# BlockBox_v2.net
KiCad netlist of a schematic drawn in EAGLE
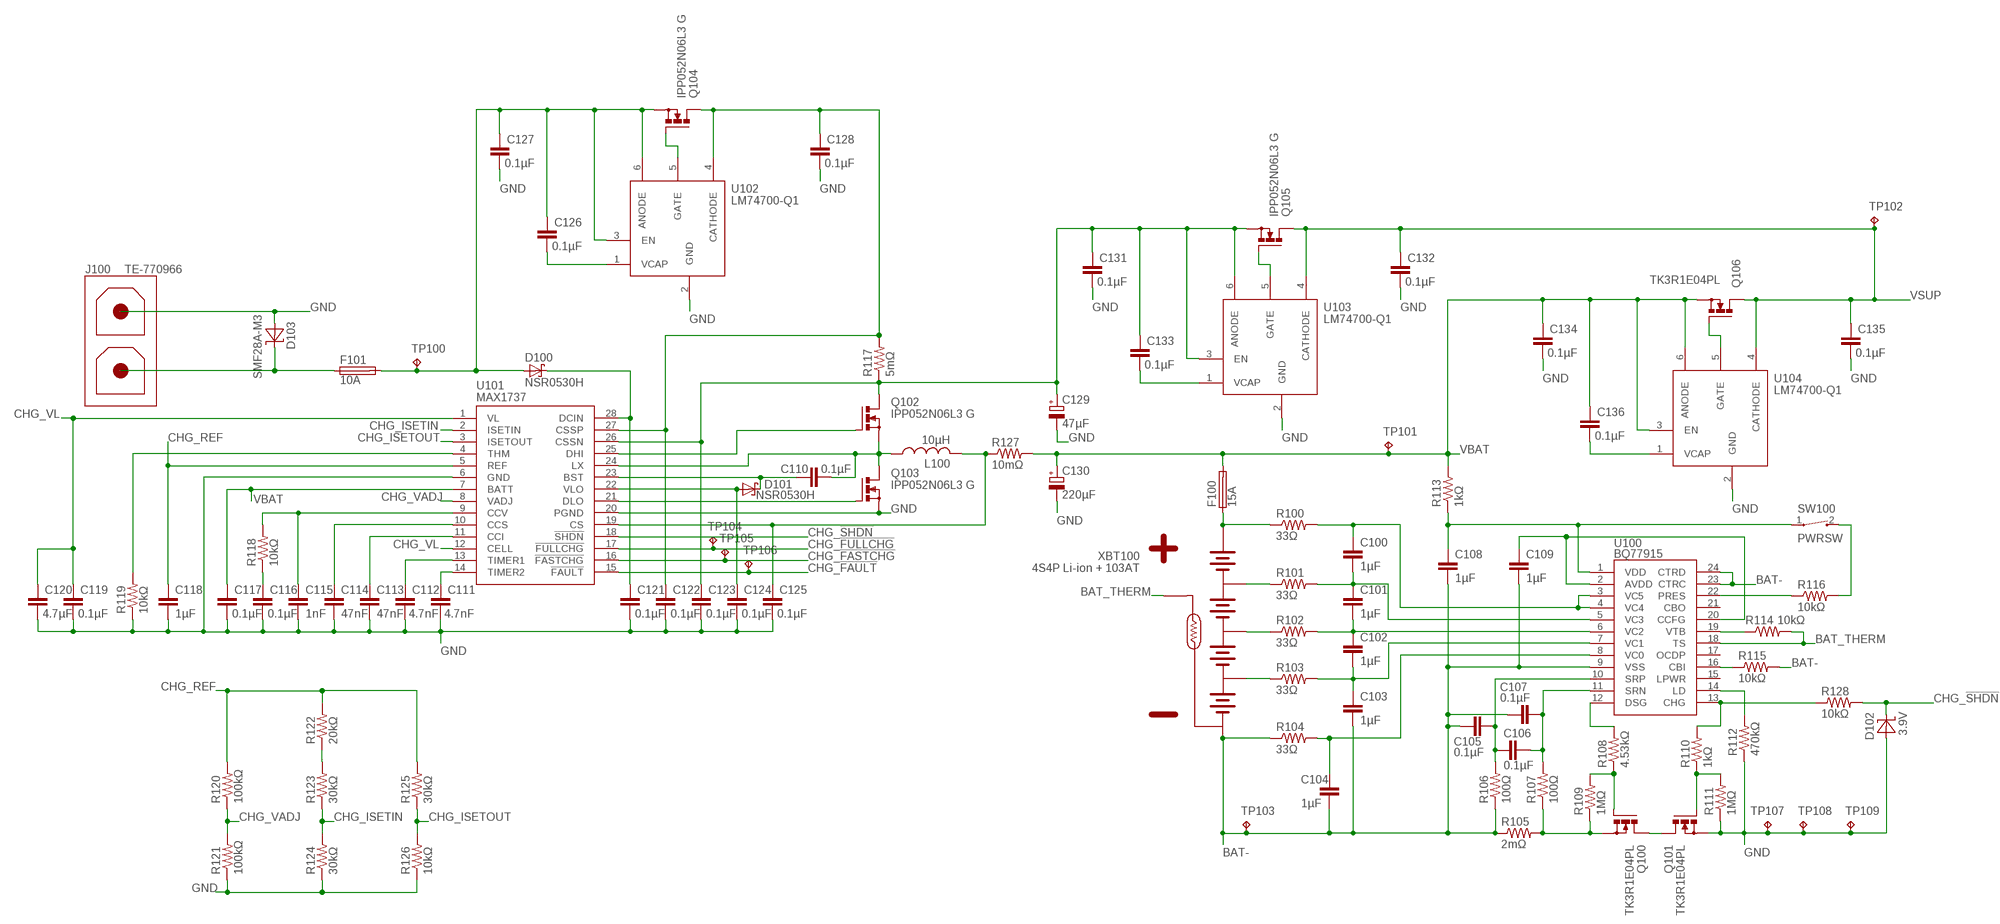
[diagram p0: schematic, sheet 1]
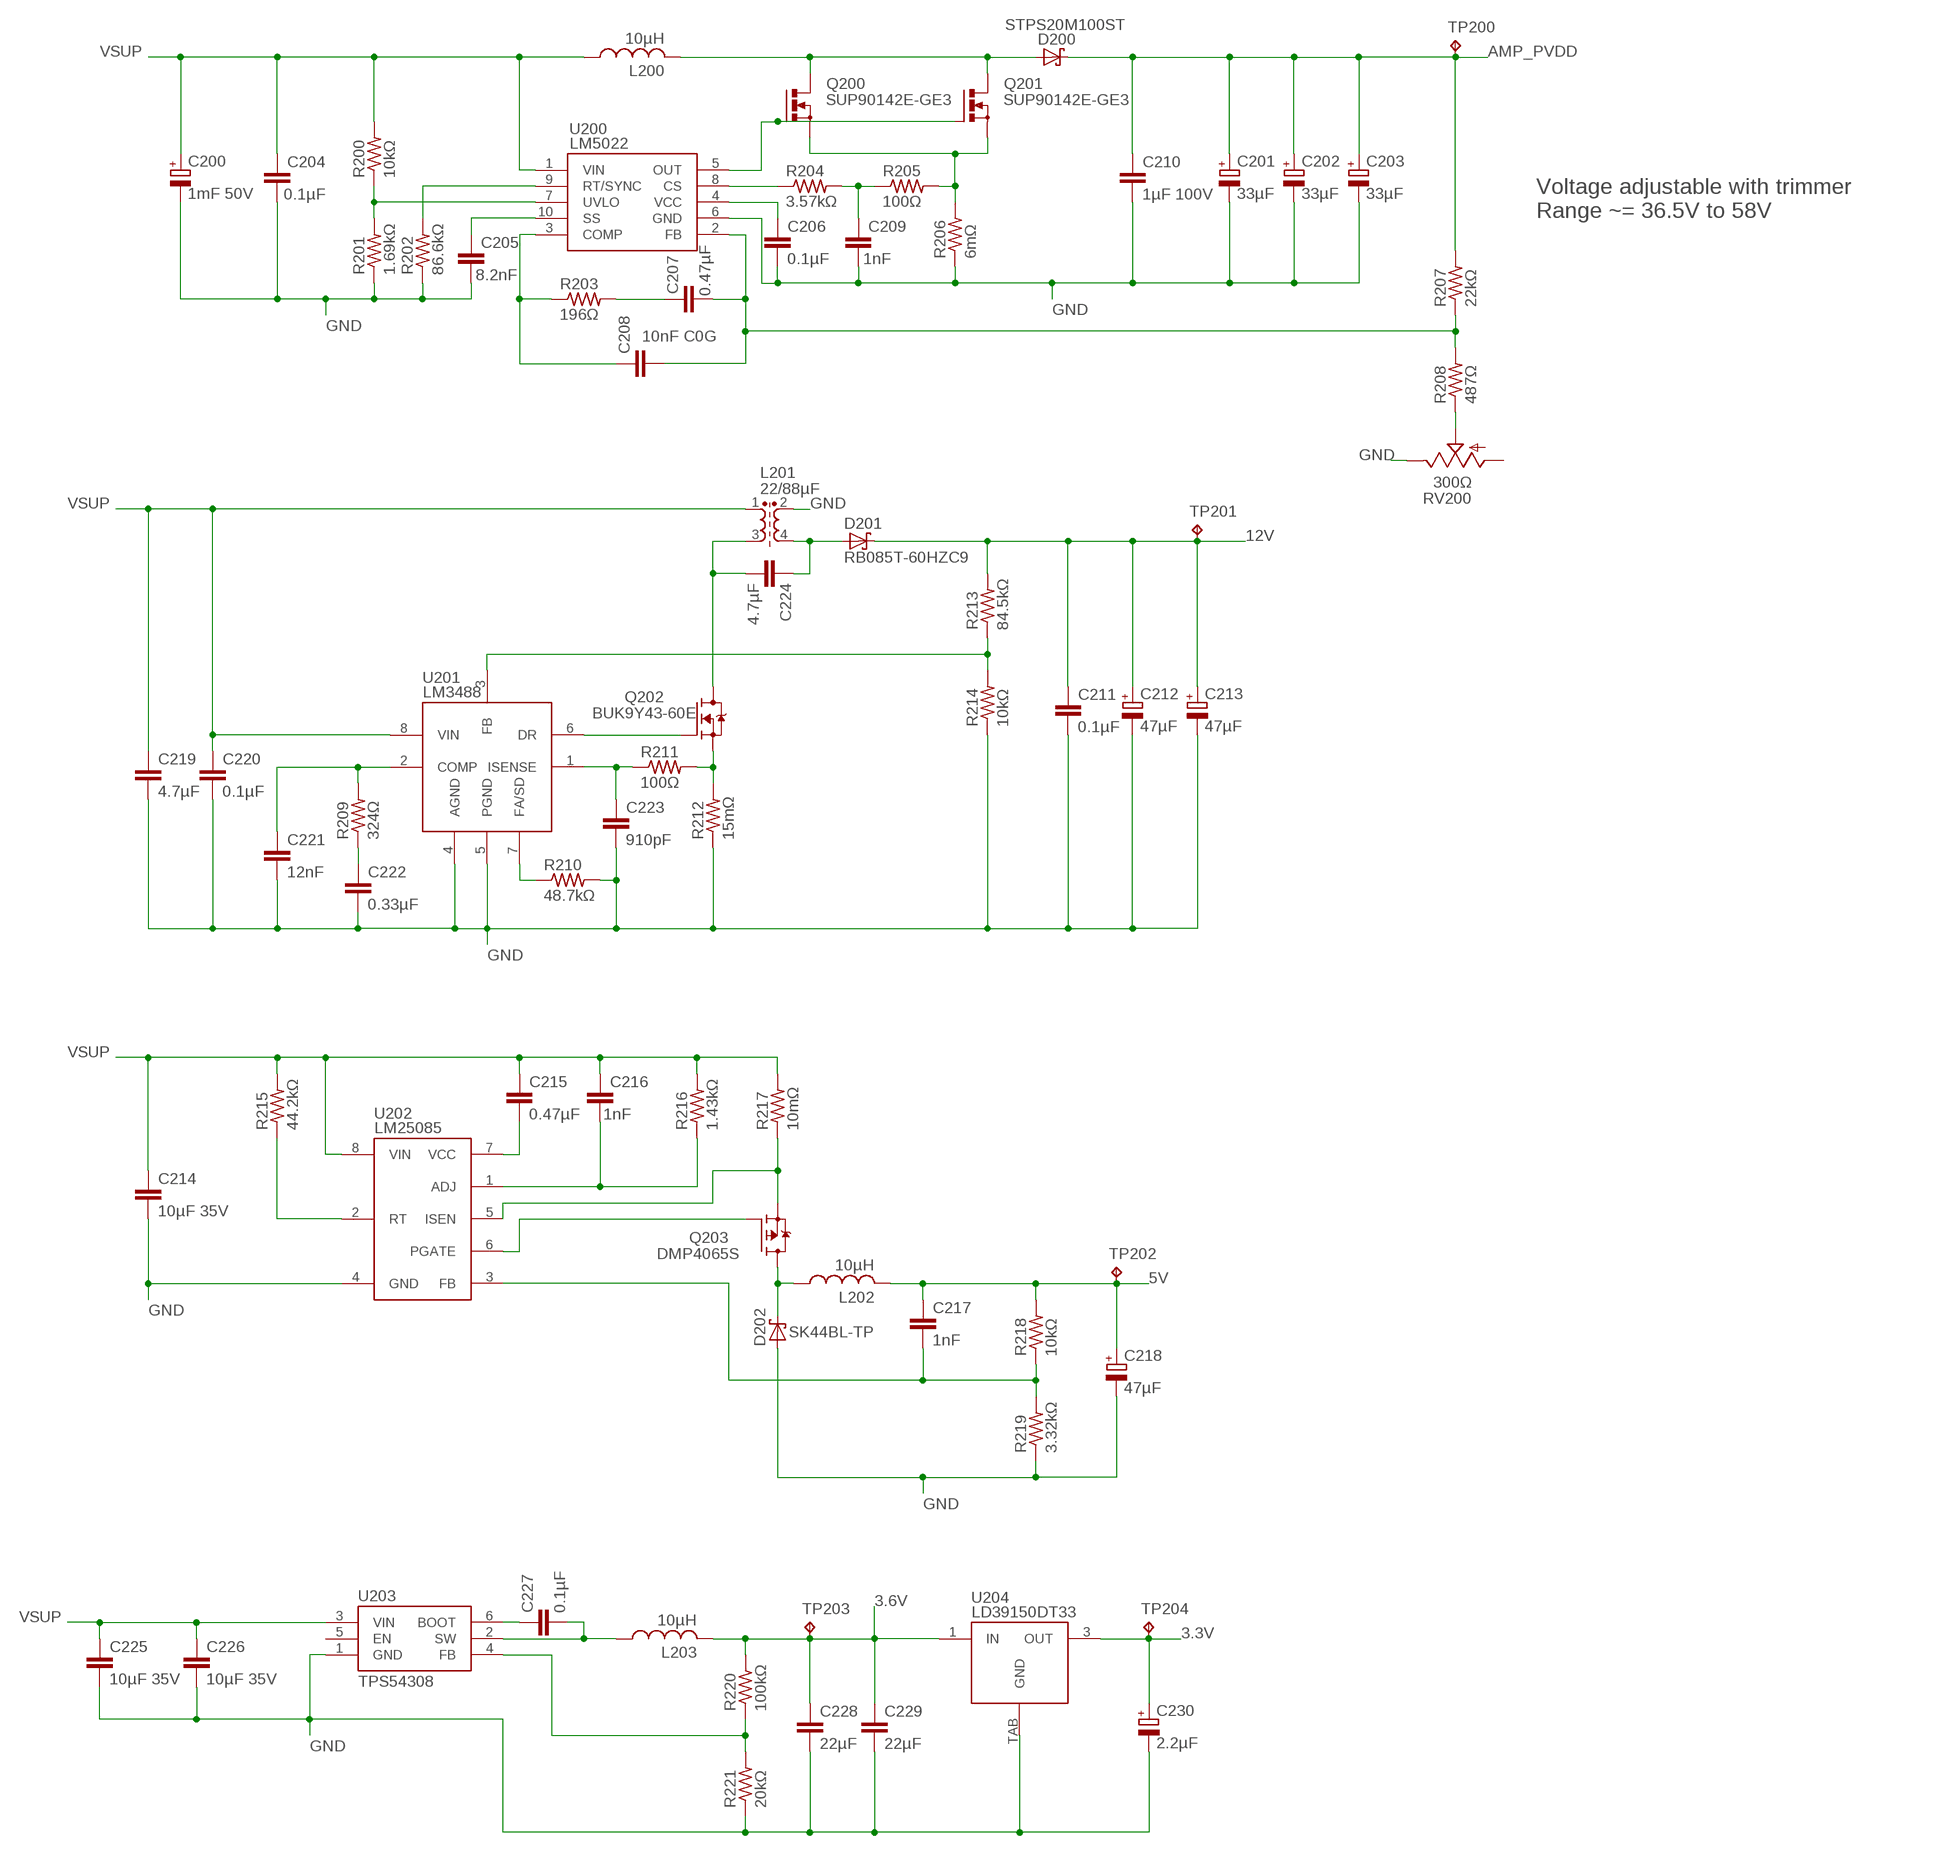
[diagram p1: schematic, sheet 2]
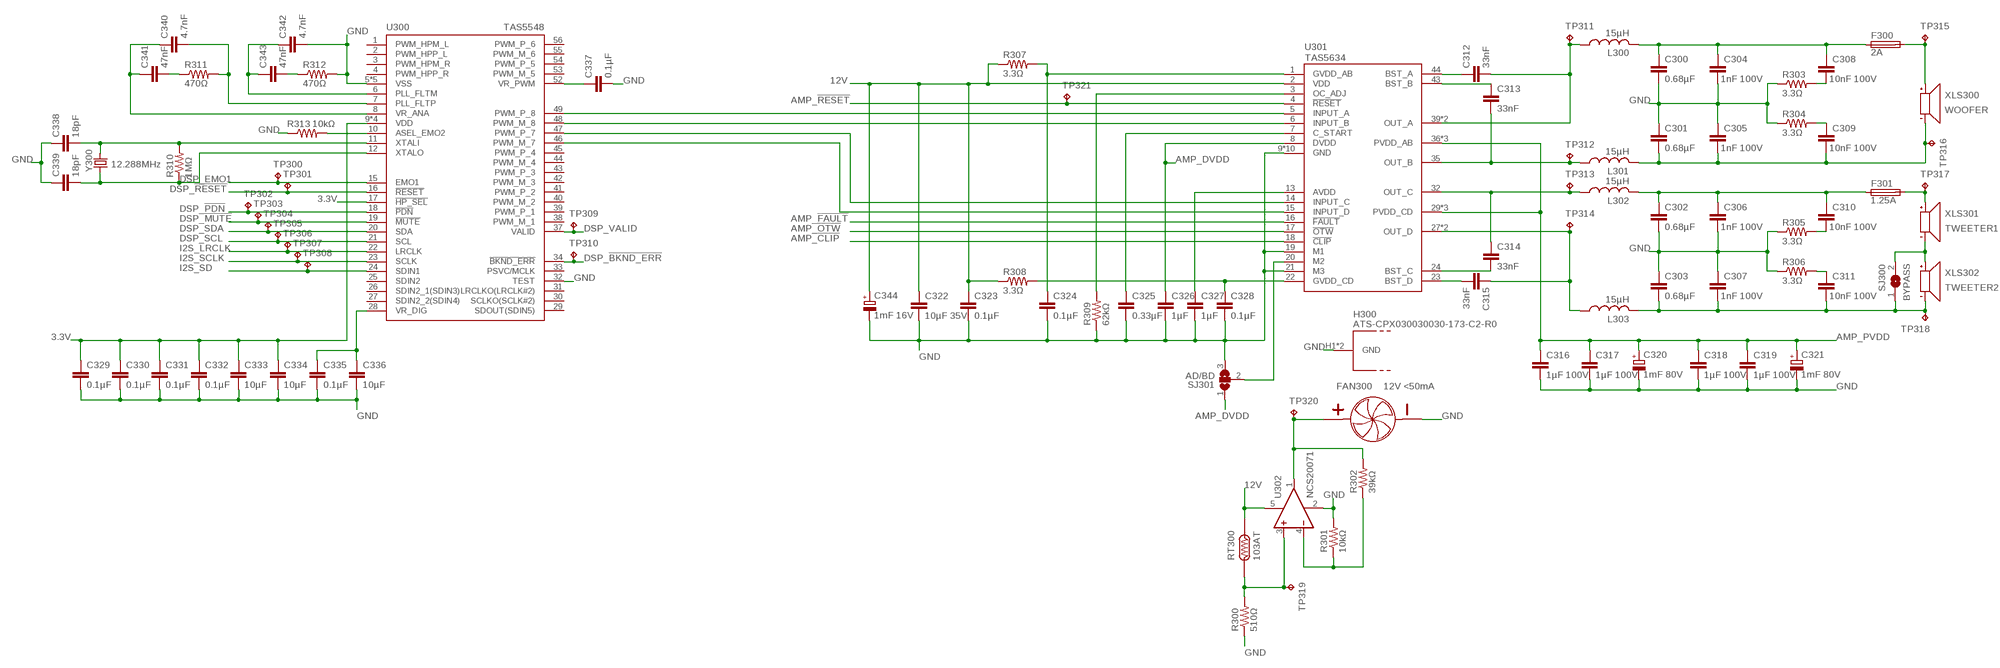
[diagram p2: schematic, sheet 3]
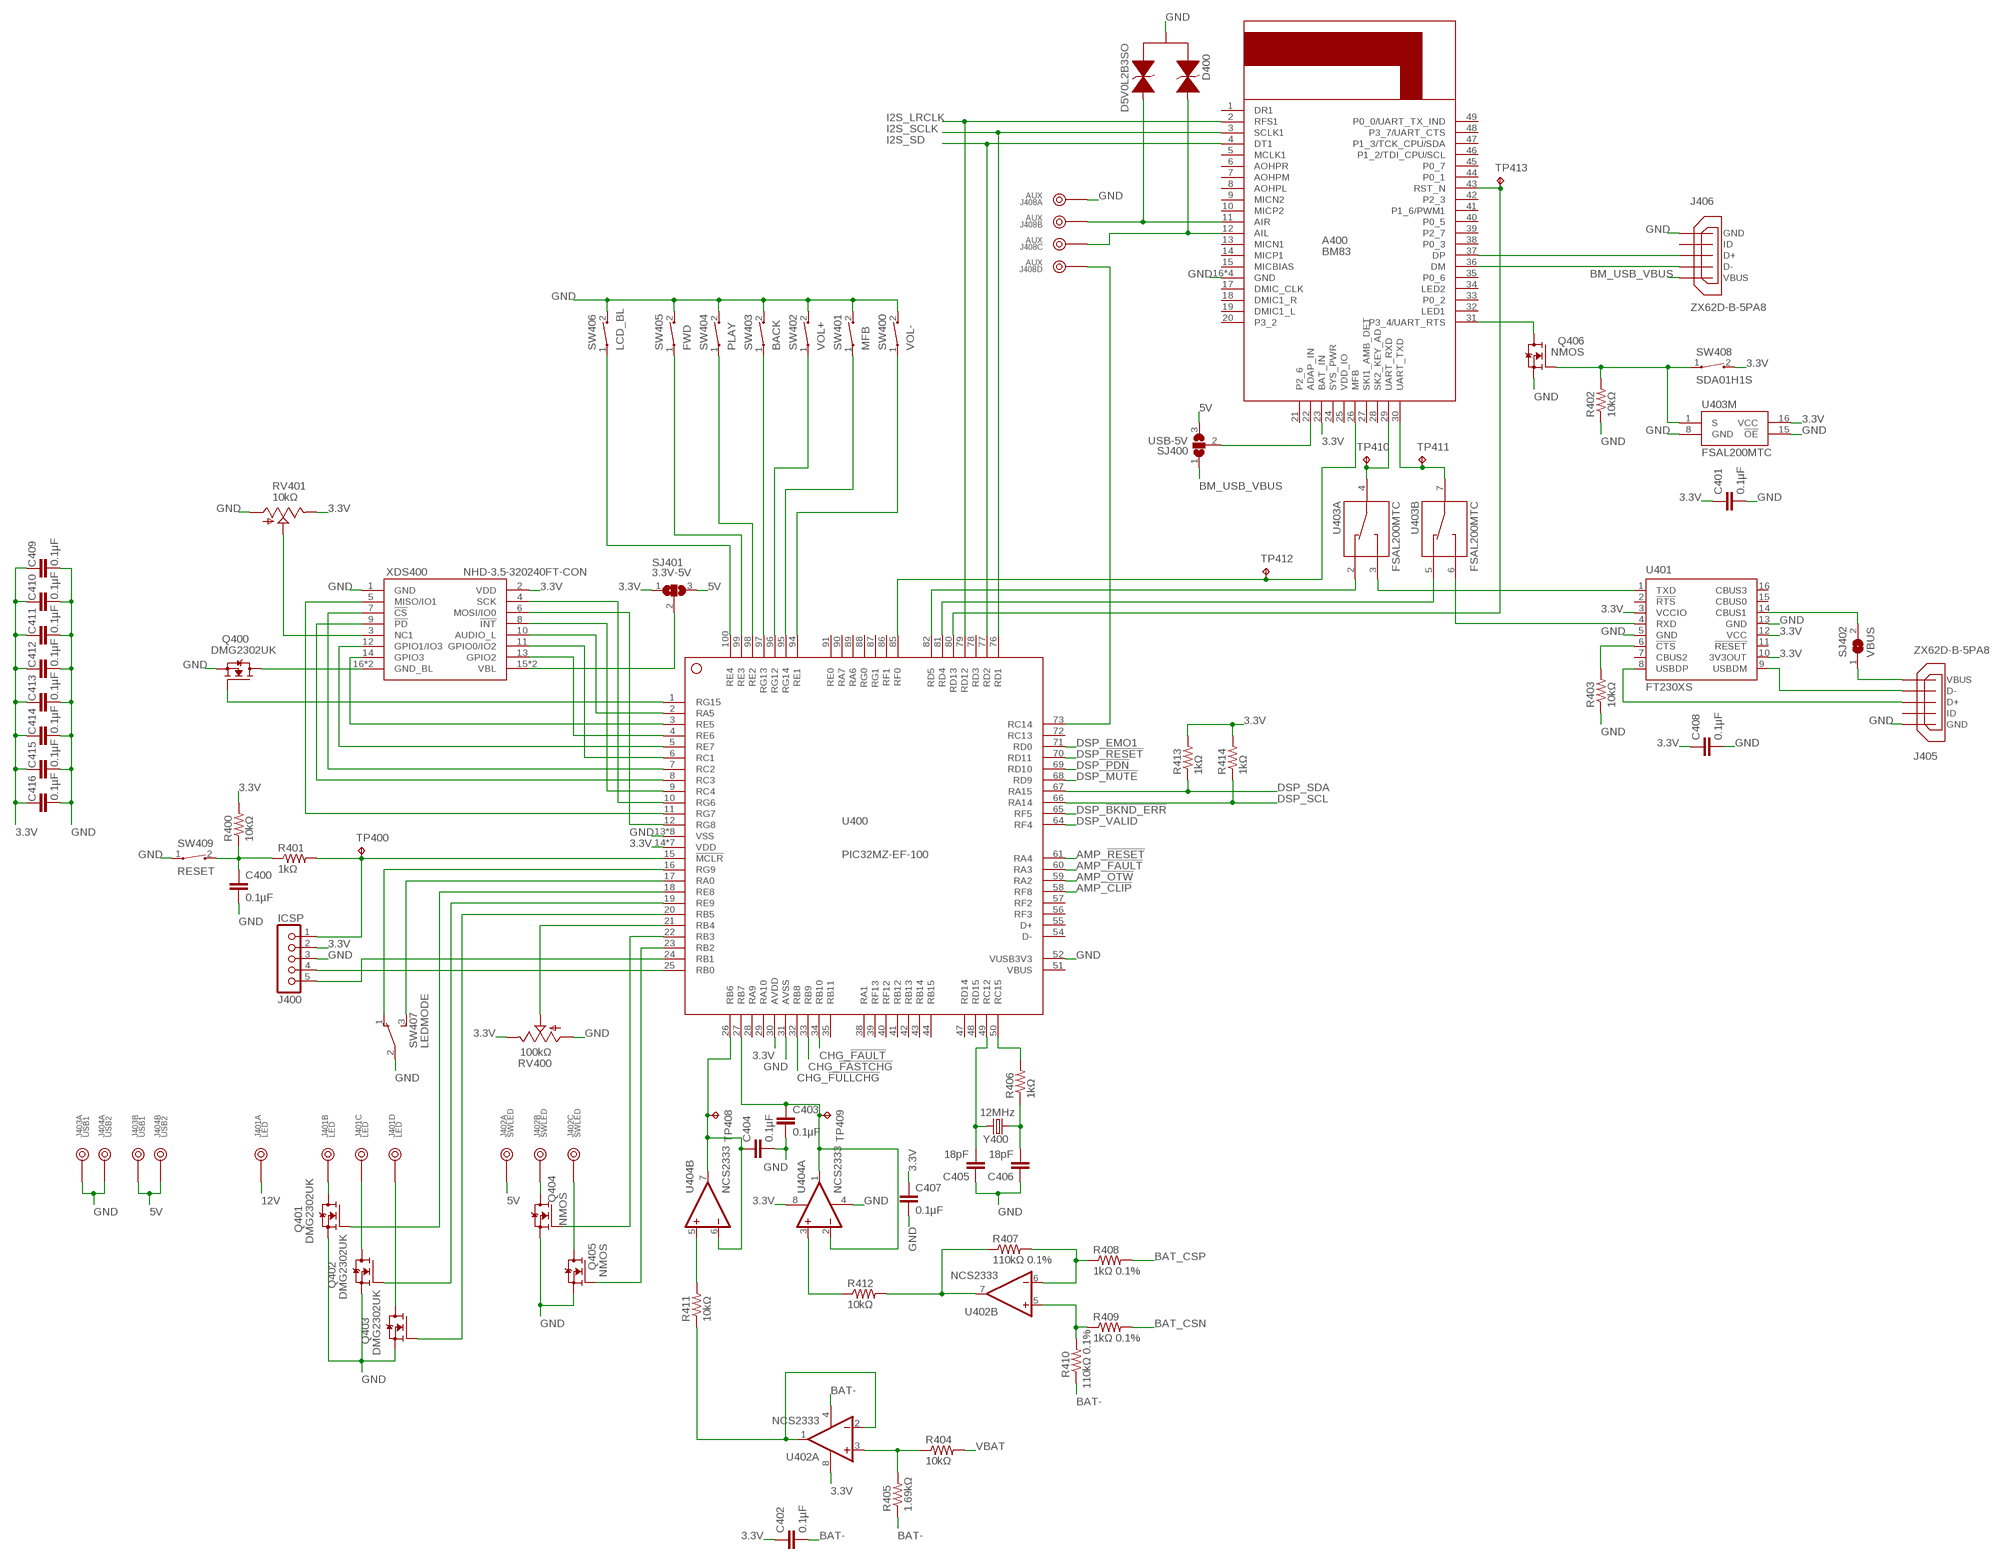
[diagram p3: schematic, sheet 4]

(export (version "E")
  (design (tool "Eeschema 10.0.6"))
  (components
    (comp (ref "C200")
      (value "1mF 50V")
      (footprint "eagle-import:E7,5-16")
      (libsource (lib "eagle-import") (part "CPOL-EUE7.5-16"))
    )
    (comp (ref "C201")
      (value "33µF")
      (footprint "eagle-import:E3,5-8")
      (libsource (lib "eagle-import") (part "CPOL-EUE3.5-8"))
    )
    (comp (ref "C202")
      (value "33µF")
      (footprint "eagle-import:E3,5-8")
      (libsource (lib "eagle-import") (part "CPOL-EUE3.5-8"))
    )
    (comp (ref "C203")
      (value "33µF")
      (footprint "eagle-import:E3,5-8")
      (libsource (lib "eagle-import") (part "CPOL-EUE3.5-8"))
    )
    (comp (ref "C204")
      (value "0.1µF")
      (footprint "eagle-import:C0603")
      (libsource (lib "eagle-import") (part "C-EUC0603"))
    )
    (comp (ref "C205")
      (value "8.2nF")
      (footprint "eagle-import:C0603")
      (libsource (lib "eagle-import") (part "C-EUC0603"))
    )
    (comp (ref "C206")
      (value "0.1µF")
      (footprint "eagle-import:C0603")
      (libsource (lib "eagle-import") (part "C-EUC0603"))
    )
    (comp (ref "C207")
      (value "0.47µF")
      (footprint "eagle-import:C050-035X075")
      (libsource (lib "eagle-import") (part "C-EU050-035X075"))
    )
    (comp (ref "C208")
      (value "10nF C0G")
      (footprint "eagle-import:C0603")
      (libsource (lib "eagle-import") (part "C-EUC0603"))
    )
    (comp (ref "C209")
      (value "1nF")
      (footprint "eagle-import:C0603")
      (libsource (lib "eagle-import") (part "C-EUC0603"))
    )
    (comp (ref "C210")
      (value "1µF 100V")
      (footprint "eagle-import:C1206")
      (libsource (lib "eagle-import") (part "C-EUC1206"))
    )
    (comp (ref "C211")
      (value "0.1µF")
      (footprint "eagle-import:C0603")
      (libsource (lib "eagle-import") (part "C-EUC0603"))
    )
    (comp (ref "C212")
      (value "47µF")
      (footprint "eagle-import:E2,5-6")
      (libsource (lib "eagle-import") (part "CPOL-EUE2.5-6"))
    )
    (comp (ref "C213")
      (value "47µF")
      (footprint "eagle-import:E2,5-6")
      (libsource (lib "eagle-import") (part "CPOL-EUE2.5-6"))
    )
    (comp (ref "C214")
      (value "10µF 35V")
      (footprint "eagle-import:C1206")
      (libsource (lib "eagle-import") (part "C-EUC1206"))
    )
    (comp (ref "C215")
      (value "0.47µF")
      (footprint "eagle-import:C0603")
      (libsource (lib "eagle-import") (part "C-EUC0603"))
    )
    (comp (ref "C216")
      (value "1nF")
      (footprint "eagle-import:C0603")
      (libsource (lib "eagle-import") (part "C-EUC0603"))
    )
    (comp (ref "C217")
      (value "1nF")
      (footprint "eagle-import:C0603")
      (libsource (lib "eagle-import") (part "C-EUC0603"))
    )
    (comp (ref "C218")
      (value "47µF")
      (footprint "eagle-import:E2,5-6")
      (libsource (lib "eagle-import") (part "CPOL-EUE2.5-6"))
    )
    (comp (ref "C219")
      (value "4.7µF")
      (footprint "eagle-import:C0805")
      (libsource (lib "eagle-import") (part "C-EUC0805"))
    )
    (comp (ref "C220")
      (value "0.1µF")
      (footprint "eagle-import:C0603")
      (libsource (lib "eagle-import") (part "C-EUC0603"))
    )
    (comp (ref "C221")
      (value "12nF")
      (footprint "eagle-import:C0603")
      (libsource (lib "eagle-import") (part "C-EUC0603"))
    )
    (comp (ref "C222")
      (value "0.33µF")
      (footprint "eagle-import:C050-035X075")
      (libsource (lib "eagle-import") (part "C-EU050-035X075"))
    )
    (comp (ref "C223")
      (value "910pF")
      (footprint "eagle-import:C0603")
      (libsource (lib "eagle-import") (part "C-EUC0603"))
    )
    (comp (ref "C224")
      (value "4.7µF")
      (footprint "eagle-import:C0805")
      (libsource (lib "eagle-import") (part "C-EUC0805"))
    )
    (comp (ref "C225")
      (value "10µF 35V")
      (footprint "eagle-import:C1206")
      (libsource (lib "eagle-import") (part "C-EUC1206"))
    )
    (comp (ref "C226")
      (value "10µF 35V")
      (footprint "eagle-import:C1206")
      (libsource (lib "eagle-import") (part "C-EUC1206"))
    )
    (comp (ref "C227")
      (value "0.1µF")
      (footprint "eagle-import:C0603")
      (libsource (lib "eagle-import") (part "C-EUC0603"))
    )
    (comp (ref "C228")
      (value "22µF")
      (footprint "eagle-import:C0805")
      (libsource (lib "eagle-import") (part "C-EUC0805"))
    )
    (comp (ref "C229")
      (value "22µF")
      (footprint "eagle-import:C0805")
      (libsource (lib "eagle-import") (part "C-EUC0805"))
    )
    (comp (ref "C230")
      (value "2.2µF")
      (footprint "eagle-import:PANASONIC_B")
      (libsource (lib "eagle-import") (part "CPOL-EUB"))
    )
    (comp (ref "D200")
      (value "STPS20M100ST")
      (footprint "eagle-import:TO220ABS-HS1")
      (libsource (lib "eagle-import") (part "TO220AB-HS1-SCHOTTKY"))
    )
    (comp (ref "D201")
      (value "RB085T-60HZC9")
      (footprint "eagle-import:TO220ABS-HS1")
      (libsource (lib "eagle-import") (part "TO220AB-HS1-SCHOTTKY"))
    )
    (comp (ref "D202")
      (value "SK44BL-TP")
      (footprint "eagle-import:DO-214AA")
      (libsource (lib "eagle-import") (part "DO-214AA-SCHOTTKY"))
    )
    (comp (ref "L200")
      (value "10µH")
      (footprint "eagle-import:PQ2614B")
      (libsource (lib "eagle-import") (part "PQ2614B"))
    )
    (comp (ref "L201")
      (value "22/88µF")
      (footprint "eagle-import:SRF1280A")
      (libsource (lib "eagle-import") (part "SRF1280A"))
    )
    (comp (ref "L202")
      (value "10µH")
      (footprint "eagle-import:SRN1060")
      (libsource (lib "eagle-import") (part "SRN1060"))
    )
    (comp (ref "L203")
      (value "10µH")
      (footprint "eagle-import:RLB0912")
      (libsource (lib "eagle-import") (part "RLB0912"))
    )
    (comp (ref "Q200")
      (value "SUP90142E-GE3")
      (footprint "eagle-import:TO220BV-HS1")
      (libsource (lib "eagle-import") (part "TO220BV-HS1-N-MOSFET"))
    )
    (comp (ref "Q201")
      (value "SUP90142E-GE3")
      (footprint "eagle-import:TO220BV-HS1")
      (libsource (lib "eagle-import") (part "TO220BV-HS1-N-MOSFET"))
    )
    (comp (ref "Q202")
      (value "BUK9Y43-60E")
      (footprint "eagle-import:SOT669")
      (libsource (lib "eagle-import") (part "SOT669-N-MOSFET"))
    )
    (comp (ref "Q203")
      (value "DMP4065S")
      (footprint "eagle-import:SOT23")
      (libsource (lib "eagle-import") (part "SOT23-P-MOSFET"))
    )
    (comp (ref "R200")
      (value "10kΩ")
      (footprint "eagle-import:R0603")
      (libsource (lib "eagle-import") (part "R-US_R0603"))
    )
    (comp (ref "R201")
      (value "1.69kΩ")
      (footprint "eagle-import:R0603")
      (libsource (lib "eagle-import") (part "R-US_R0603"))
    )
    (comp (ref "R202")
      (value "86.6kΩ")
      (footprint "eagle-import:R0603")
      (libsource (lib "eagle-import") (part "R-US_R0603"))
    )
    (comp (ref "R203")
      (value "196Ω")
      (footprint "eagle-import:R0603")
      (libsource (lib "eagle-import") (part "R-US_R0603"))
    )
    (comp (ref "R204")
      (value "3.57kΩ")
      (footprint "eagle-import:R0603")
      (libsource (lib "eagle-import") (part "R-US_R0603"))
    )
    (comp (ref "R205")
      (value "100Ω")
      (footprint "eagle-import:R0603")
      (libsource (lib "eagle-import") (part "R-US_R0603"))
    )
    (comp (ref "R206")
      (value "6mΩ")
      (footprint "eagle-import:R2512")
      (libsource (lib "eagle-import") (part "R-US_R2512"))
    )
    (comp (ref "R207")
      (value "22kΩ")
      (footprint "eagle-import:R0603")
      (libsource (lib "eagle-import") (part "R-US_R0603"))
    )
    (comp (ref "R208")
      (value "487Ω")
      (footprint "eagle-import:R0603")
      (libsource (lib "eagle-import") (part "R-US_R0603"))
    )
    (comp (ref "R209")
      (value "324Ω")
      (footprint "eagle-import:R0603")
      (libsource (lib "eagle-import") (part "R-US_R0603"))
    )
    (comp (ref "R210")
      (value "48.7kΩ")
      (footprint "eagle-import:R0603")
      (libsource (lib "eagle-import") (part "R-US_R0603"))
    )
    (comp (ref "R211")
      (value "100Ω")
      (footprint "eagle-import:R0603")
      (libsource (lib "eagle-import") (part "R-US_R0603"))
    )
    (comp (ref "R212")
      (value "15mΩ")
      (footprint "eagle-import:R0612")
      (libsource (lib "eagle-import") (part "R-US_R0612"))
    )
    (comp (ref "R213")
      (value "84.5kΩ")
      (footprint "eagle-import:R0603")
      (libsource (lib "eagle-import") (part "R-US_R0603"))
    )
    (comp (ref "R214")
      (value "10kΩ")
      (footprint "eagle-import:R0603")
      (libsource (lib "eagle-import") (part "R-US_R0603"))
    )
    (comp (ref "R215")
      (value "44.2kΩ")
      (footprint "eagle-import:R0603")
      (libsource (lib "eagle-import") (part "R-US_R0603"))
    )
    (comp (ref "R216")
      (value "1.43kΩ")
      (footprint "eagle-import:R0603")
      (libsource (lib "eagle-import") (part "R-US_R0603"))
    )
    (comp (ref "R217")
      (value "10mΩ")
      (footprint "eagle-import:R1206")
      (libsource (lib "eagle-import") (part "R-US_R1206"))
    )
    (comp (ref "R218")
      (value "10kΩ")
      (footprint "eagle-import:R0603")
      (libsource (lib "eagle-import") (part "R-US_R0603"))
    )
    (comp (ref "R219")
      (value "3.32kΩ")
      (footprint "eagle-import:R0603")
      (libsource (lib "eagle-import") (part "R-US_R0603"))
    )
    (comp (ref "R220")
      (value "100kΩ")
      (footprint "eagle-import:R0603")
      (libsource (lib "eagle-import") (part "R-US_R0603"))
    )
    (comp (ref "R221")
      (value "20kΩ")
      (footprint "eagle-import:R0603")
      (libsource (lib "eagle-import") (part "R-US_R0603"))
    )
    (comp (ref "RV200")
      (value "300Ω")
      (footprint "eagle-import:TC33X-2")
      (libsource (lib "eagle-import") (part "TC33X-2"))
    )
    (comp (ref "TP200")
      (value "TPTP15R")
      (footprint "eagle-import:TP15R")
      (fields (field (name "TP_SIGNAL_NAME") "PVDD"))
      (libsource (lib "eagle-import") (part "TPTP15R"))
    )
    (comp (ref "TP201")
      (value "TPTP15R")
      (footprint "eagle-import:TP15R")
      (fields (field (name "TP_SIGNAL_NAME") "12V"))
      (libsource (lib "eagle-import") (part "TPTP15R"))
    )
    (comp (ref "TP202")
      (value "TPTP15R")
      (footprint "eagle-import:TP15R")
      (fields (field (name "TP_SIGNAL_NAME") "5V"))
      (libsource (lib "eagle-import") (part "TPTP15R"))
    )
    (comp (ref "TP203")
      (value "TPTP15R")
      (footprint "eagle-import:TP15R")
      (fields (field (name "TP_SIGNAL_NAME") "3.6V"))
      (libsource (lib "eagle-import") (part "TPTP15R"))
    )
    (comp (ref "TP204")
      (value "TPTP15R")
      (footprint "eagle-import:TP15R")
      (fields (field (name "TP_SIGNAL_NAME") "3.3V"))
      (libsource (lib "eagle-import") (part "TPTP15R"))
    )
    (comp (ref "U200")
      (value "LM5022")
      (footprint "eagle-import:VSSOP10")
      (libsource (lib "eagle-import") (part "LM5022"))
    )
    (comp (ref "U201")
      (value "LM3488")
      (footprint "eagle-import:VSSOP8")
      (libsource (lib "eagle-import") (part "LM3488"))
    )
    (comp (ref "U202")
      (value "LM25085")
      (footprint "eagle-import:VSSOP8")
      (libsource (lib "eagle-import") (part "LM25085"))
    )
    (comp (ref "U203")
      (value "TPS54308")
      (footprint "eagle-import:SOT23-6L")
      (libsource (lib "eagle-import") (part "TPS54308"))
    )
    (comp (ref "U204")
      (value "LD39150DT33")
      (footprint "eagle-import:DPAK")
      (libsource (lib "eagle-import") (part "DPAK-LDO"))
    )
    (comp (ref "C300")
      (value "0.68µF")
      (footprint "eagle-import:C150-064X183")
      (libsource (lib "eagle-import") (part "C-EU150-064X183"))
    )
    (comp (ref "C301")
      (value "0.68µF")
      (footprint "eagle-import:C150-064X183")
      (libsource (lib "eagle-import") (part "C-EU150-064X183"))
    )
    (comp (ref "C302")
      (value "0.68µF")
      (footprint "eagle-import:C150-064X183")
      (libsource (lib "eagle-import") (part "C-EU150-064X183"))
    )
    (comp (ref "C303")
      (value "0.68µF")
      (footprint "eagle-import:C150-064X183")
      (libsource (lib "eagle-import") (part "C-EU150-064X183"))
    )
    (comp (ref "C304")
      (value "1nF 100V")
      (footprint "eagle-import:C0603")
      (libsource (lib "eagle-import") (part "C-EUC0603"))
    )
    (comp (ref "C305")
      (value "1nF 100V")
      (footprint "eagle-import:C0603")
      (libsource (lib "eagle-import") (part "C-EUC0603"))
    )
    (comp (ref "C306")
      (value "1nF 100V")
      (footprint "eagle-import:C0603")
      (libsource (lib "eagle-import") (part "C-EUC0603"))
    )
    (comp (ref "C307")
      (value "1nF 100V")
      (footprint "eagle-import:C0603")
      (libsource (lib "eagle-import") (part "C-EUC0603"))
    )
    (comp (ref "C308")
      (value "10nF 100V")
      (footprint "eagle-import:C0603")
      (libsource (lib "eagle-import") (part "C-EUC0603"))
    )
    (comp (ref "C309")
      (value "10nF 100V")
      (footprint "eagle-import:C0603")
      (libsource (lib "eagle-import") (part "C-EUC0603"))
    )
    (comp (ref "C310")
      (value "10nF 100V")
      (footprint "eagle-import:C0603")
      (libsource (lib "eagle-import") (part "C-EUC0603"))
    )
    (comp (ref "C311")
      (value "10nF 100V")
      (footprint "eagle-import:C0603")
      (libsource (lib "eagle-import") (part "C-EUC0603"))
    )
    (comp (ref "C312")
      (value "33nF")
      (footprint "eagle-import:C0805")
      (libsource (lib "eagle-import") (part "C-EUC0805"))
    )
    (comp (ref "C313")
      (value "33nF")
      (footprint "eagle-import:C0805")
      (libsource (lib "eagle-import") (part "C-EUC0805"))
    )
    (comp (ref "C314")
      (value "33nF")
      (footprint "eagle-import:C0805")
      (libsource (lib "eagle-import") (part "C-EUC0805"))
    )
    (comp (ref "C315")
      (value "33nF")
      (footprint "eagle-import:C0805")
      (libsource (lib "eagle-import") (part "C-EUC0805"))
    )
    (comp (ref "C316")
      (value "1µF 100V")
      (footprint "eagle-import:C1206")
      (libsource (lib "eagle-import") (part "C-EUC1206"))
    )
    (comp (ref "C317")
      (value "1µF 100V")
      (footprint "eagle-import:C1206")
      (libsource (lib "eagle-import") (part "C-EUC1206"))
    )
    (comp (ref "C318")
      (value "1µF 100V")
      (footprint "eagle-import:C1206")
      (libsource (lib "eagle-import") (part "C-EUC1206"))
    )
    (comp (ref "C319")
      (value "1µF 100V")
      (footprint "eagle-import:C1206")
      (libsource (lib "eagle-import") (part "C-EUC1206"))
    )
    (comp (ref "C320")
      (value "1mF 80V")
      (footprint "eagle-import:E7,5-16")
      (libsource (lib "eagle-import") (part "CPOL-EUE7.5-16"))
    )
    (comp (ref "C321")
      (value "1mF 80V")
      (footprint "eagle-import:E7,5-16")
      (libsource (lib "eagle-import") (part "CPOL-EUE7.5-16"))
    )
    (comp (ref "C322")
      (value "10µF 35V")
      (footprint "eagle-import:C1206")
      (libsource (lib "eagle-import") (part "C-EUC1206"))
    )
    (comp (ref "C323")
      (value "0.1µF")
      (footprint "eagle-import:C0603")
      (libsource (lib "eagle-import") (part "C-EUC0603"))
    )
    (comp (ref "C324")
      (value "0.1µF")
      (footprint "eagle-import:C0603")
      (libsource (lib "eagle-import") (part "C-EUC0603"))
    )
    (comp (ref "C325")
      (value "0.33µF")
      (footprint "eagle-import:C0603")
      (libsource (lib "eagle-import") (part "C-EUC0603"))
    )
    (comp (ref "C326")
      (value "1µF")
      (footprint "eagle-import:C0603")
      (libsource (lib "eagle-import") (part "C-EUC0603"))
    )
    (comp (ref "C327")
      (value "1µF")
      (footprint "eagle-import:C0603")
      (libsource (lib "eagle-import") (part "C-EUC0603"))
    )
    (comp (ref "C328")
      (value "0.1µF")
      (footprint "eagle-import:C0603")
      (libsource (lib "eagle-import") (part "C-EUC0603"))
    )
    (comp (ref "C329")
      (value "0.1µF")
      (footprint "eagle-import:C0603")
      (libsource (lib "eagle-import") (part "C-EUC0603"))
    )
    (comp (ref "C330")
      (value "0.1µF")
      (footprint "eagle-import:C0603")
      (libsource (lib "eagle-import") (part "C-EUC0603"))
    )
    (comp (ref "C331")
      (value "0.1µF")
      (footprint "eagle-import:C0603")
      (libsource (lib "eagle-import") (part "C-EUC0603"))
    )
    (comp (ref "C332")
      (value "0.1µF")
      (footprint "eagle-import:C0603")
      (libsource (lib "eagle-import") (part "C-EUC0603"))
    )
    (comp (ref "C333")
      (value "10µF")
      (footprint "eagle-import:C0805")
      (libsource (lib "eagle-import") (part "C-EUC0805"))
    )
    (comp (ref "C334")
      (value "10µF")
      (footprint "eagle-import:C0805")
      (libsource (lib "eagle-import") (part "C-EUC0805"))
    )
    (comp (ref "C335")
      (value "0.1µF")
      (footprint "eagle-import:C0603")
      (libsource (lib "eagle-import") (part "C-EUC0603"))
    )
    (comp (ref "C336")
      (value "10µF")
      (footprint "eagle-import:C0805")
      (libsource (lib "eagle-import") (part "C-EUC0805"))
    )
    (comp (ref "C337")
      (value "0.1µF")
      (footprint "eagle-import:C0603")
      (libsource (lib "eagle-import") (part "C-EUC0603"))
    )
    (comp (ref "C338")
      (value "18pF")
      (footprint "eagle-import:C0603")
      (libsource (lib "eagle-import") (part "C-EUC0603"))
    )
    (comp (ref "C339")
      (value "18pF")
      (footprint "eagle-import:C0603")
      (libsource (lib "eagle-import") (part "C-EUC0603"))
    )
    (comp (ref "C340")
      (value "4.7nF")
      (footprint "eagle-import:C0603")
      (libsource (lib "eagle-import") (part "C-EUC0603"))
    )
    (comp (ref "C341")
      (value "47nF")
      (footprint "eagle-import:C0603")
      (libsource (lib "eagle-import") (part "C-EUC0603"))
    )
    (comp (ref "C342")
      (value "4.7nF")
      (footprint "eagle-import:C0603")
      (libsource (lib "eagle-import") (part "C-EUC0603"))
    )
    (comp (ref "C343")
      (value "47nF")
      (footprint "eagle-import:C0603")
      (libsource (lib "eagle-import") (part "C-EUC0603"))
    )
    (comp (ref "C344")
      (value "1mF 16V")
      (footprint "eagle-import:E5-10,5")
      (libsource (lib "eagle-import") (part "CPOL-EUE5-10.5"))
    )
    (comp (ref "F300")
      (value "2A")
      (footprint "eagle-import:MRF_FUSE")
      (libsource (lib "eagle-import") (part "MRF_FUSE"))
    )
    (comp (ref "F301")
      (value "1.25A")
      (footprint "eagle-import:MRF_FUSE")
      (libsource (lib "eagle-import") (part "MRF_FUSE"))
    )
    (comp (ref "FAN300")
      (value "12V <50mA")
      (footprint "eagle-import:WIRE-2P-SIMPLE")
      (libsource (lib "eagle-import") (part "WIRED-FAN"))
    )
    (comp (ref "H300")
      (value "ATS-CPX030030030-173-C2-R0")
      (footprint "eagle-import:ATS-CPX030030030-173-C2-R0")
      (libsource (lib "eagle-import") (part "ATS-CPX030030030-173-C2-R0"))
    )
    (comp (ref "L300")
      (value "15µH")
      (footprint "eagle-import:1D14A")
      (libsource (lib "eagle-import") (part "1D14A"))
    )
    (comp (ref "L301")
      (value "15µH")
      (footprint "eagle-import:1D14A")
      (libsource (lib "eagle-import") (part "1D14A"))
    )
    (comp (ref "L302")
      (value "15µH")
      (footprint "eagle-import:1D14A")
      (libsource (lib "eagle-import") (part "1D14A"))
    )
    (comp (ref "L303")
      (value "15µH")
      (footprint "eagle-import:1D14A")
      (libsource (lib "eagle-import") (part "1D14A"))
    )
    (comp (ref "R300")
      (value "510Ω")
      (footprint "eagle-import:R0603")
      (libsource (lib "eagle-import") (part "R-US_R0603"))
    )
    (comp (ref "R301")
      (value "10kΩ")
      (footprint "eagle-import:R0603")
      (libsource (lib "eagle-import") (part "R-US_R0603"))
    )
    (comp (ref "R302")
      (value "39kΩ")
      (footprint "eagle-import:R0603")
      (libsource (lib "eagle-import") (part "R-US_R0603"))
    )
    (comp (ref "R303")
      (value "3.3Ω")
      (footprint "eagle-import:R0805")
      (libsource (lib "eagle-import") (part "R-US_R0805"))
    )
    (comp (ref "R304")
      (value "3.3Ω")
      (footprint "eagle-import:R0805")
      (libsource (lib "eagle-import") (part "R-US_R0805"))
    )
    (comp (ref "R305")
      (value "3.3Ω")
      (footprint "eagle-import:R0805")
      (libsource (lib "eagle-import") (part "R-US_R0805"))
    )
    (comp (ref "R306")
      (value "3.3Ω")
      (footprint "eagle-import:R0805")
      (libsource (lib "eagle-import") (part "R-US_R0805"))
    )
    (comp (ref "R307")
      (value "3.3Ω")
      (footprint "eagle-import:R0805")
      (libsource (lib "eagle-import") (part "R-US_R0805"))
    )
    (comp (ref "R308")
      (value "3.3Ω")
      (footprint "eagle-import:R0805")
      (libsource (lib "eagle-import") (part "R-US_R0805"))
    )
    (comp (ref "R309")
      (value "62kΩ")
      (footprint "eagle-import:R0603")
      (libsource (lib "eagle-import") (part "R-US_R0603"))
    )
    (comp (ref "R310")
      (value "1MΩ")
      (footprint "eagle-import:R0603")
      (libsource (lib "eagle-import") (part "R-US_R0603"))
    )
    (comp (ref "R311")
      (value "470Ω")
      (footprint "eagle-import:R0603")
      (libsource (lib "eagle-import") (part "R-US_R0603"))
    )
    (comp (ref "R312")
      (value "470Ω")
      (footprint "eagle-import:R0603")
      (libsource (lib "eagle-import") (part "R-US_R0603"))
    )
    (comp (ref "R313")
      (value "10kΩ")
      (footprint "eagle-import:R0603")
      (libsource (lib "eagle-import") (part "R-US_R0603"))
    )
    (comp (ref "RT300")
      (value "103AT")
      (footprint "eagle-import:WIRE-2P-SIMPLE")
      (libsource (lib "eagle-import") (part "WIRED-THERMISTOR"))
    )
    (comp (ref "SJ300")
      (value "BYPASS")
      (footprint "eagle-import:SJ")
      (libsource (lib "eagle-import") (part "SJ"))
    )
    (comp (ref "SJ301")
      (value "AD/BD")
      (footprint "eagle-import:SJ_2")
      (libsource (lib "eagle-import") (part "SJ2W"))
    )
    (comp (ref "TP300")
      (value "TPTP15R")
      (footprint "eagle-import:TP15R")
      (fields (field (name "TP_SIGNAL_NAME") "EMO1"))
      (libsource (lib "eagle-import") (part "TPTP15R"))
    )
    (comp (ref "TP301")
      (value "TPTP15R")
      (footprint "eagle-import:TP15R")
      (fields (field (name "TP_SIGNAL_NAME") "DSP_!RESET"))
      (libsource (lib "eagle-import") (part "TPTP15R"))
    )
    (comp (ref "TP302")
      (value "TPTP15R")
      (footprint "eagle-import:TP15R")
      (fields (field (name "TP_SIGNAL_NAME") "DSP_!PDN"))
      (libsource (lib "eagle-import") (part "TPTP15R"))
    )
    (comp (ref "TP303")
      (value "TPTP15R")
      (footprint "eagle-import:TP15R")
      (fields (field (name "TP_SIGNAL_NAME") "!MUTE"))
      (libsource (lib "eagle-import") (part "TPTP15R"))
    )
    (comp (ref "TP304")
      (value "TPTP15R")
      (footprint "eagle-import:TP15R")
      (fields (field (name "TP_SIGNAL_NAME") "SDA"))
      (libsource (lib "eagle-import") (part "TPTP15R"))
    )
    (comp (ref "TP305")
      (value "TPTP15R")
      (footprint "eagle-import:TP15R")
      (fields (field (name "TP_SIGNAL_NAME") "SCL"))
      (libsource (lib "eagle-import") (part "TPTP15R"))
    )
    (comp (ref "TP306")
      (value "TPTP15R")
      (footprint "eagle-import:TP15R")
      (fields (field (name "TP_SIGNAL_NAME") "LRCLK"))
      (libsource (lib "eagle-import") (part "TPTP15R"))
    )
    (comp (ref "TP307")
      (value "TPTP15R")
      (footprint "eagle-import:TP15R")
      (fields (field (name "TP_SIGNAL_NAME") "SCLK"))
      (libsource (lib "eagle-import") (part "TPTP15R"))
    )
    (comp (ref "TP308")
      (value "TPTP15R")
      (footprint "eagle-import:TP15R")
      (fields (field (name "TP_SIGNAL_NAME") "SD"))
      (libsource (lib "eagle-import") (part "TPTP15R"))
    )
    (comp (ref "TP309")
      (value "TPTP15R")
      (footprint "eagle-import:TP15R")
      (fields (field (name "TP_SIGNAL_NAME") "VALID"))
      (libsource (lib "eagle-import") (part "TPTP15R"))
    )
    (comp (ref "TP310")
      (value "TPTP15R")
      (footprint "eagle-import:TP15R")
      (fields (field (name "TP_SIGNAL_NAME") "!BKND_ERR"))
      (libsource (lib "eagle-import") (part "TPTP15R"))
    )
    (comp (ref "TP311")
      (value "TPTP15R")
      (footprint "eagle-import:TP15R")
      (fields (field (name "TP_SIGNAL_NAME") "OUT_A"))
      (libsource (lib "eagle-import") (part "TPTP15R"))
    )
    (comp (ref "TP312")
      (value "TPTP15R")
      (footprint "eagle-import:TP15R")
      (fields (field (name "TP_SIGNAL_NAME") "OUT_B"))
      (libsource (lib "eagle-import") (part "TPTP15R"))
    )
    (comp (ref "TP313")
      (value "TPTP15R")
      (footprint "eagle-import:TP15R")
      (fields (field (name "TP_SIGNAL_NAME") "OUT_C"))
      (libsource (lib "eagle-import") (part "TPTP15R"))
    )
    (comp (ref "TP314")
      (value "TPTP15R")
      (footprint "eagle-import:TP15R")
      (fields (field (name "TP_SIGNAL_NAME") "OUT_D"))
      (libsource (lib "eagle-import") (part "TPTP15R"))
    )
    (comp (ref "TP315")
      (value "TPTP15R")
      (footprint "eagle-import:TP15R")
      (fields (field (name "TP_SIGNAL_NAME") "SPK_A"))
      (libsource (lib "eagle-import") (part "TPTP15R"))
    )
    (comp (ref "TP316")
      (value "TPTP15R")
      (footprint "eagle-import:TP15R")
      (fields (field (name "TP_SIGNAL_NAME") "SPK_B"))
      (libsource (lib "eagle-import") (part "TPTP15R"))
    )
    (comp (ref "TP317")
      (value "TPTP15R")
      (footprint "eagle-import:TP15R")
      (fields (field (name "TP_SIGNAL_NAME") "SPK_C"))
      (libsource (lib "eagle-import") (part "TPTP15R"))
    )
    (comp (ref "TP318")
      (value "TPTP15R")
      (footprint "eagle-import:TP15R")
      (fields (field (name "TP_SIGNAL_NAME") "SPK_D"))
      (libsource (lib "eagle-import") (part "TPTP15R"))
    )
    (comp (ref "TP319")
      (value "TPTP15R")
      (footprint "eagle-import:TP15R")
      (fields (field (name "TP_SIGNAL_NAME") "THERM"))
      (libsource (lib "eagle-import") (part "TPTP15R"))
    )
    (comp (ref "TP320")
      (value "TPTP15R")
      (footprint "eagle-import:TP15R")
      (fields (field (name "TP_SIGNAL_NAME") "FAN"))
      (libsource (lib "eagle-import") (part "TPTP15R"))
    )
    (comp (ref "TP321")
      (value "TPTP15R")
      (footprint "eagle-import:TP15R")
      (fields (field (name "TP_SIGNAL_NAME") "AMP_!RESET"))
      (libsource (lib "eagle-import") (part "TPTP15R"))
    )
    (comp (ref "U300")
      (value "TAS5548")
      (footprint "eagle-import:HTSSOP56DCA")
      (libsource (lib "eagle-import") (part "TAS5548"))
    )
    (comp (ref "U301")
      (value "TAS5634")
      (footprint "eagle-import:TSSOP44")
      (libsource (lib "eagle-import") (part "TAS5634"))
    )
    (comp (ref "U302")
      (value "NCS20071")
      (footprint "eagle-import:TSOP-5")
      (libsource (lib "eagle-import") (part "NCS20071"))
    )
    (comp (ref "XLS300")
      (value "WOOFER")
      (footprint "eagle-import:TE-770966")
      (libsource (lib "eagle-import") (part "SPEAKER-CONN"))
    )
    (comp (ref "XLS301")
      (value "TWEETER1")
      (footprint "eagle-import:TE-770966")
      (libsource (lib "eagle-import") (part "SPEAKER-CONN"))
    )
    (comp (ref "XLS302")
      (value "TWEETER2")
      (footprint "eagle-import:TE-770966")
      (libsource (lib "eagle-import") (part "SPEAKER-CONN"))
    )
    (comp (ref "Y300")
      (value "12.288MHz")
      (footprint "eagle-import:HC49US")
      (libsource (lib "eagle-import") (part "HC49US-CRYSTAL"))
    )
    (comp (ref "C100")
      (value "1µF")
      (footprint "eagle-import:C0603")
      (libsource (lib "eagle-import") (part "C-EUC0603"))
    )
    (comp (ref "C101")
      (value "1µF")
      (footprint "eagle-import:C0603")
      (libsource (lib "eagle-import") (part "C-EUC0603"))
    )
    (comp (ref "C102")
      (value "1µF")
      (footprint "eagle-import:C0603")
      (libsource (lib "eagle-import") (part "C-EUC0603"))
    )
    (comp (ref "C103")
      (value "1µF")
      (footprint "eagle-import:C0603")
      (libsource (lib "eagle-import") (part "C-EUC0603"))
    )
    (comp (ref "C104")
      (value "1µF")
      (footprint "eagle-import:C0603")
      (libsource (lib "eagle-import") (part "C-EUC0603"))
    )
    (comp (ref "C105")
      (value "0.1µF")
      (footprint "eagle-import:C0603")
      (libsource (lib "eagle-import") (part "C-EUC0603"))
    )
    (comp (ref "C106")
      (value "0.1µF")
      (footprint "eagle-import:C0603")
      (libsource (lib "eagle-import") (part "C-EUC0603"))
    )
    (comp (ref "C107")
      (value "0.1µF")
      (footprint "eagle-import:C0603")
      (libsource (lib "eagle-import") (part "C-EUC0603"))
    )
    (comp (ref "C108")
      (value "1µF")
      (footprint "eagle-import:C0603")
      (libsource (lib "eagle-import") (part "C-EUC0603"))
    )
    (comp (ref "C109")
      (value "1µF")
      (footprint "eagle-import:C0603")
      (libsource (lib "eagle-import") (part "C-EUC0603"))
    )
    (comp (ref "C110")
      (value "0.1µF")
      (footprint "eagle-import:C0603")
      (libsource (lib "eagle-import") (part "C-EUC0603"))
    )
    (comp (ref "C111")
      (value "4.7nF")
      (footprint "eagle-import:C0603")
      (libsource (lib "eagle-import") (part "C-EUC0603"))
    )
    (comp (ref "C112")
      (value "4.7nF")
      (footprint "eagle-import:C0603")
      (libsource (lib "eagle-import") (part "C-EUC0603"))
    )
    (comp (ref "C113")
      (value "47nF")
      (footprint "eagle-import:C0603")
      (libsource (lib "eagle-import") (part "C-EUC0603"))
    )
    (comp (ref "C114")
      (value "47nF")
      (footprint "eagle-import:C0603")
      (libsource (lib "eagle-import") (part "C-EUC0603"))
    )
    (comp (ref "C115")
      (value "1nF")
      (footprint "eagle-import:C0603")
      (libsource (lib "eagle-import") (part "C-EUC0603"))
    )
    (comp (ref "C116")
      (value "0.1µF")
      (footprint "eagle-import:C0603")
      (libsource (lib "eagle-import") (part "C-EUC0603"))
    )
    (comp (ref "C117")
      (value "0.1µF")
      (footprint "eagle-import:C0603")
      (libsource (lib "eagle-import") (part "C-EUC0603"))
    )
    (comp (ref "C118")
      (value "1µF")
      (footprint "eagle-import:C0603")
      (libsource (lib "eagle-import") (part "C-EUC0603"))
    )
    (comp (ref "C119")
      (value "0.1µF")
      (footprint "eagle-import:C0603")
      (libsource (lib "eagle-import") (part "C-EUC0603"))
    )
    (comp (ref "C120")
      (value "4.7µF")
      (footprint "eagle-import:C0805")
      (libsource (lib "eagle-import") (part "C-EUC0805"))
    )
    (comp (ref "C121")
      (value "0.1µF")
      (footprint "eagle-import:C0603")
      (libsource (lib "eagle-import") (part "C-EUC0603"))
    )
    (comp (ref "C122")
      (value "0.1µF")
      (footprint "eagle-import:C0603")
      (libsource (lib "eagle-import") (part "C-EUC0603"))
    )
    (comp (ref "C123")
      (value "0.1µF")
      (footprint "eagle-import:C0603")
      (libsource (lib "eagle-import") (part "C-EUC0603"))
    )
    (comp (ref "C124")
      (value "0.1µF")
      (footprint "eagle-import:C0603")
      (libsource (lib "eagle-import") (part "C-EUC0603"))
    )
    (comp (ref "C125")
      (value "0.1µF")
      (footprint "eagle-import:C0603")
      (libsource (lib "eagle-import") (part "C-EUC0603"))
    )
    (comp (ref "C126")
      (value "0.1µF")
      (footprint "eagle-import:C0603")
      (libsource (lib "eagle-import") (part "C-EUC0603"))
    )
    (comp (ref "C127")
      (value "0.1µF")
      (footprint "eagle-import:C0603")
      (libsource (lib "eagle-import") (part "C-EUC0603"))
    )
    (comp (ref "C128")
      (value "0.1µF")
      (footprint "eagle-import:C0603")
      (libsource (lib "eagle-import") (part "C-EUC0603"))
    )
    (comp (ref "C129")
      (value "47µF")
      (footprint "eagle-import:E2,5-6")
      (libsource (lib "eagle-import") (part "CPOL-EUE2.5-6"))
    )
    (comp (ref "C130")
      (value "220µF")
      (footprint "eagle-import:E3,5-8")
      (libsource (lib "eagle-import") (part "CPOL-EUE3.5-8"))
    )
    (comp (ref "C131")
      (value "0.1µF")
      (footprint "eagle-import:C0603")
      (libsource (lib "eagle-import") (part "C-EUC0603"))
    )
    (comp (ref "C132")
      (value "0.1µF")
      (footprint "eagle-import:C0603")
      (libsource (lib "eagle-import") (part "C-EUC0603"))
    )
    (comp (ref "C133")
      (value "0.1µF")
      (footprint "eagle-import:C0603")
      (libsource (lib "eagle-import") (part "C-EUC0603"))
    )
    (comp (ref "C134")
      (value "0.1µF")
      (footprint "eagle-import:C0603")
      (libsource (lib "eagle-import") (part "C-EUC0603"))
    )
    (comp (ref "C135")
      (value "0.1µF")
      (footprint "eagle-import:C0603")
      (libsource (lib "eagle-import") (part "C-EUC0603"))
    )
    (comp (ref "C136")
      (value "0.1µF")
      (footprint "eagle-import:C0603")
      (libsource (lib "eagle-import") (part "C-EUC0603"))
    )
    (comp (ref "D100")
      (value "NSR0530H")
      (footprint "eagle-import:SOD323")
      (libsource (lib "eagle-import") (part "SOD323-SCHOTTKY"))
    )
    (comp (ref "D101")
      (value "NSR0530H")
      (footprint "eagle-import:SOD323")
      (libsource (lib "eagle-import") (part "SOD323-SCHOTTKY"))
    )
    (comp (ref "D102")
      (value "3.9V")
      (footprint "eagle-import:SOD323")
      (libsource (lib "eagle-import") (part "SOD323-ZENER"))
    )
    (comp (ref "D103")
      (value "SMF28A-M3")
      (footprint "eagle-import:DO-219AB")
      (libsource (lib "eagle-import") (part "DO-219AB-ZENER"))
    )
    (comp (ref "F100")
      (value "15A")
      (footprint "eagle-import:F2410")
      (libsource (lib "eagle-import") (part "2410-FUSE"))
    )
    (comp (ref "F101")
      (value "10A")
      (footprint "eagle-import:F2410")
      (libsource (lib "eagle-import") (part "2410-FUSE"))
    )
    (comp (ref "J100")
      (value "TE-770966")
      (footprint "eagle-import:TE-770966")
      (libsource (lib "eagle-import") (part "TE-770966"))
    )
    (comp (ref "L100")
      (value "10µH")
      (footprint "eagle-import:PM5022")
      (libsource (lib "eagle-import") (part "PM5022"))
    )
    (comp (ref "Q100")
      (value "TK3R1E04PL")
      (footprint "eagle-import:TO220BV-HS1")
      (libsource (lib "eagle-import") (part "TO220BV-HS1-N-MOSFET"))
    )
    (comp (ref "Q101")
      (value "TK3R1E04PL")
      (footprint "eagle-import:TO220BV-HS1")
      (libsource (lib "eagle-import") (part "TO220BV-HS1-N-MOSFET"))
    )
    (comp (ref "Q102")
      (value "IPP052N06L3 G")
      (footprint "eagle-import:TO220BV-HS1")
      (libsource (lib "eagle-import") (part "TO220BV-HS1-N-MOSFET"))
    )
    (comp (ref "Q103")
      (value "IPP052N06L3 G")
      (footprint "eagle-import:TO220BV-HS1")
      (libsource (lib "eagle-import") (part "TO220BV-HS1-N-MOSFET"))
    )
    (comp (ref "Q104")
      (value "IPP052N06L3 G")
      (footprint "eagle-import:TO220BV-HS1")
      (libsource (lib "eagle-import") (part "TO220BV-HS1-N-MOSFET"))
    )
    (comp (ref "Q105")
      (value "IPP052N06L3 G")
      (footprint "eagle-import:TO220BV-HS1")
      (libsource (lib "eagle-import") (part "TO220BV-HS1-N-MOSFET"))
    )
    (comp (ref "Q106")
      (value "TK3R1E04PL")
      (footprint "eagle-import:TO220BV-HS1")
      (libsource (lib "eagle-import") (part "TO220BV-HS1-N-MOSFET"))
    )
    (comp (ref "R100")
      (value "33Ω")
      (footprint "eagle-import:R0603")
      (libsource (lib "eagle-import") (part "R-US_R0603"))
    )
    (comp (ref "R101")
      (value "33Ω")
      (footprint "eagle-import:R0603")
      (libsource (lib "eagle-import") (part "R-US_R0603"))
    )
    (comp (ref "R102")
      (value "33Ω")
      (footprint "eagle-import:R0603")
      (libsource (lib "eagle-import") (part "R-US_R0603"))
    )
    (comp (ref "R103")
      (value "33Ω")
      (footprint "eagle-import:R0603")
      (libsource (lib "eagle-import") (part "R-US_R0603"))
    )
    (comp (ref "R104")
      (value "33Ω")
      (footprint "eagle-import:R0603")
      (libsource (lib "eagle-import") (part "R-US_R0603"))
    )
    (comp (ref "R105")
      (value "2mΩ")
      (footprint "eagle-import:R2512")
      (libsource (lib "eagle-import") (part "R-US_R2512"))
    )
    (comp (ref "R106")
      (value "100Ω")
      (footprint "eagle-import:R0603")
      (libsource (lib "eagle-import") (part "R-US_R0603"))
    )
    (comp (ref "R107")
      (value "100Ω")
      (footprint "eagle-import:R0603")
      (libsource (lib "eagle-import") (part "R-US_R0603"))
    )
    (comp (ref "R108")
      (value "4.53kΩ")
      (footprint "eagle-import:R0603")
      (libsource (lib "eagle-import") (part "R-US_R0603"))
    )
    (comp (ref "R109")
      (value "1MΩ")
      (footprint "eagle-import:R0603")
      (libsource (lib "eagle-import") (part "R-US_R0603"))
    )
    (comp (ref "R110")
      (value "1kΩ")
      (footprint "eagle-import:R0603")
      (libsource (lib "eagle-import") (part "R-US_R0603"))
    )
    (comp (ref "R111")
      (value "1MΩ")
      (footprint "eagle-import:R0603")
      (libsource (lib "eagle-import") (part "R-US_R0603"))
    )
    (comp (ref "R112")
      (value "470kΩ")
      (footprint "eagle-import:R0603")
      (libsource (lib "eagle-import") (part "R-US_R0603"))
    )
    (comp (ref "R113")
      (value "1kΩ")
      (footprint "eagle-import:R0603")
      (libsource (lib "eagle-import") (part "R-US_R0603"))
    )
    (comp (ref "R114")
      (value "10kΩ")
      (footprint "eagle-import:R0603")
      (libsource (lib "eagle-import") (part "R-US_R0603"))
    )
    (comp (ref "R115")
      (value "10kΩ")
      (footprint "eagle-import:R0603")
      (libsource (lib "eagle-import") (part "R-US_R0603"))
    )
    (comp (ref "R116")
      (value "10kΩ")
      (footprint "eagle-import:R0603")
      (libsource (lib "eagle-import") (part "R-US_R0603"))
    )
    (comp (ref "R117")
      (value "5mΩ")
      (footprint "eagle-import:R1206")
      (libsource (lib "eagle-import") (part "R-US_R1206"))
    )
    (comp (ref "R118")
      (value "10kΩ")
      (footprint "eagle-import:R0603")
      (libsource (lib "eagle-import") (part "R-US_R0603"))
    )
    (comp (ref "R119")
      (value "10kΩ")
      (footprint "eagle-import:R0603")
      (libsource (lib "eagle-import") (part "R-US_R0603"))
    )
    (comp (ref "R120")
      (value "100kΩ")
      (footprint "eagle-import:R0603")
      (libsource (lib "eagle-import") (part "R-US_R0603"))
    )
    (comp (ref "R121")
      (value "100kΩ")
      (footprint "eagle-import:R0603")
      (libsource (lib "eagle-import") (part "R-US_R0603"))
    )
    (comp (ref "R122")
      (value "20kΩ")
      (footprint "eagle-import:R0603")
      (libsource (lib "eagle-import") (part "R-US_R0603"))
    )
    (comp (ref "R123")
      (value "30kΩ")
      (footprint "eagle-import:R0603")
      (libsource (lib "eagle-import") (part "R-US_R0603"))
    )
    (comp (ref "R124")
      (value "30kΩ")
      (footprint "eagle-import:R0603")
      (libsource (lib "eagle-import") (part "R-US_R0603"))
    )
    (comp (ref "R125")
      (value "30kΩ")
      (footprint "eagle-import:R0603")
      (libsource (lib "eagle-import") (part "R-US_R0603"))
    )
    (comp (ref "R126")
      (value "10kΩ")
      (footprint "eagle-import:R0603")
      (libsource (lib "eagle-import") (part "R-US_R0603"))
    )
    (comp (ref "R127")
      (value "10mΩ")
      (footprint "eagle-import:R1206")
      (libsource (lib "eagle-import") (part "R-US_R1206"))
    )
    (comp (ref "R128")
      (value "10kΩ")
      (footprint "eagle-import:R0603")
      (libsource (lib "eagle-import") (part "R-US_R0603"))
    )
    (comp (ref "SW100")
      (value "PWRSW")
      (footprint "eagle-import:WIRE-2P-SIMPLE")
      (libsource (lib "eagle-import") (part "WIRED-SWITCH-NO"))
    )
    (comp (ref "TP100")
      (value "TPTP15R")
      (footprint "eagle-import:TP15R")
      (fields (field (name "TP_SIGNAL_NAME") "VIN"))
      (libsource (lib "eagle-import") (part "TPTP15R"))
    )
    (comp (ref "TP101")
      (value "TPTP15R")
      (footprint "eagle-import:TP15R")
      (fields (field (name "TP_SIGNAL_NAME") "VBAT"))
      (libsource (lib "eagle-import") (part "TPTP15R"))
    )
    (comp (ref "TP102")
      (value "TPTP15R")
      (footprint "eagle-import:TP15R")
      (fields (field (name "TP_SIGNAL_NAME") "VSUP"))
      (libsource (lib "eagle-import") (part "TPTP15R"))
    )
    (comp (ref "TP103")
      (value "TPTP15R")
      (footprint "eagle-import:TP15R")
      (fields (field (name "TP_SIGNAL_NAME") "BAT-"))
      (libsource (lib "eagle-import") (part "TPTP15R"))
    )
    (comp (ref "TP104")
      (value "TPTP15R")
      (footprint "eagle-import:TP15R")
      (fields (field (name "TP_SIGNAL_NAME") "!FULLCHG"))
      (libsource (lib "eagle-import") (part "TPTP15R"))
    )
    (comp (ref "TP105")
      (value "TPTP15R")
      (footprint "eagle-import:TP15R")
      (fields (field (name "TP_SIGNAL_NAME") "!FASTCHG"))
      (libsource (lib "eagle-import") (part "TPTP15R"))
    )
    (comp (ref "TP106")
      (value "TPTP15R")
      (footprint "eagle-import:TP15R")
      (fields (field (name "TP_SIGNAL_NAME") "CHG_!FAULT"))
      (libsource (lib "eagle-import") (part "TPTP15R"))
    )
    (comp (ref "TP107")
      (value "TPTP15R")
      (footprint "eagle-import:TP15R")
      (fields (field (name "TP_SIGNAL_NAME") "BAT-"))
      (libsource (lib "eagle-import") (part "TPTP15R"))
    )
    (comp (ref "TP108")
      (value "TPTP15R")
      (footprint "eagle-import:TP15R")
      (fields (field (name "TP_SIGNAL_NAME") "BAT-"))
      (libsource (lib "eagle-import") (part "TPTP15R"))
    )
    (comp (ref "TP109")
      (value "TPTP15R")
      (footprint "eagle-import:TP15R")
      (fields (field (name "TP_SIGNAL_NAME") "BAT-"))
      (libsource (lib "eagle-import") (part "TPTP15R"))
    )
    (comp (ref "U100")
      (value "BQ77915")
      (footprint "eagle-import:TSSOP24")
      (libsource (lib "eagle-import") (part "BQ77915"))
    )
    (comp (ref "U101")
      (value "MAX1737")
      (footprint "eagle-import:QSOP28")
      (libsource (lib "eagle-import") (part "MAX1737"))
    )
    (comp (ref "U102")
      (value "LM74700-Q1")
      (footprint "eagle-import:SOT23-6L")
      (libsource (lib "eagle-import") (part "LM74700-Q1"))
    )
    (comp (ref "U103")
      (value "LM74700-Q1")
      (footprint "eagle-import:SOT23-6L")
      (libsource (lib "eagle-import") (part "LM74700-Q1"))
    )
    (comp (ref "U104")
      (value "LM74700-Q1")
      (footprint "eagle-import:SOT23-6L")
      (libsource (lib "eagle-import") (part "LM74700-Q1"))
    )
    (comp (ref "XBT100")
      (value "4S4P Li-ion + 103AT")
      (footprint "eagle-import:TE-770970")
      (libsource (lib "eagle-import") (part "LI-ION-PACK-CONN"))
    )
    (comp (ref "A400")
      (value "BM83")
      (footprint "eagle-import:BM83")
      (libsource (lib "eagle-import") (part "BM83"))
    )
    (comp (ref "C400")
      (value "0.1µF")
      (footprint "eagle-import:C0603")
      (libsource (lib "eagle-import") (part "C-EUC0603"))
    )
    (comp (ref "C401")
      (value "0.1µF")
      (footprint "eagle-import:C0603")
      (libsource (lib "eagle-import") (part "C-EUC0603"))
    )
    (comp (ref "C402")
      (value "0.1µF")
      (footprint "eagle-import:C0603")
      (libsource (lib "eagle-import") (part "C-EUC0603"))
    )
    (comp (ref "C403")
      (value "0.1µF")
      (footprint "eagle-import:C0603")
      (libsource (lib "eagle-import") (part "C-EUC0603"))
    )
    (comp (ref "C404")
      (value "0.1µF")
      (footprint "eagle-import:C0603")
      (libsource (lib "eagle-import") (part "C-EUC0603"))
    )
    (comp (ref "C405")
      (value "18pF")
      (footprint "eagle-import:C0603")
      (libsource (lib "eagle-import") (part "C-EUC0603"))
    )
    (comp (ref "C406")
      (value "18pF")
      (footprint "eagle-import:C0603")
      (libsource (lib "eagle-import") (part "C-EUC0603"))
    )
    (comp (ref "C407")
      (value "0.1µF")
      (footprint "eagle-import:C0603")
      (libsource (lib "eagle-import") (part "C-EUC0603"))
    )
    (comp (ref "C408")
      (value "0.1µF")
      (footprint "eagle-import:C0603")
      (libsource (lib "eagle-import") (part "C-EUC0603"))
    )
    (comp (ref "C409")
      (value "0.1µF")
      (footprint "eagle-import:C0603")
      (libsource (lib "eagle-import") (part "C-EUC0603"))
    )
    (comp (ref "C410")
      (value "0.1µF")
      (footprint "eagle-import:C0603")
      (libsource (lib "eagle-import") (part "C-EUC0603"))
    )
    (comp (ref "C411")
      (value "0.1µF")
      (footprint "eagle-import:C0603")
      (libsource (lib "eagle-import") (part "C-EUC0603"))
    )
    (comp (ref "C412")
      (value "0.1µF")
      (footprint "eagle-import:C0603")
      (libsource (lib "eagle-import") (part "C-EUC0603"))
    )
    (comp (ref "C413")
      (value "0.1µF")
      (footprint "eagle-import:C0603")
      (libsource (lib "eagle-import") (part "C-EUC0603"))
    )
    (comp (ref "C414")
      (value "0.1µF")
      (footprint "eagle-import:C0603")
      (libsource (lib "eagle-import") (part "C-EUC0603"))
    )
    (comp (ref "C415")
      (value "0.1µF")
      (footprint "eagle-import:C0603")
      (libsource (lib "eagle-import") (part "C-EUC0603"))
    )
    (comp (ref "C416")
      (value "0.1µF")
      (footprint "eagle-import:C0603")
      (libsource (lib "eagle-import") (part "C-EUC0603"))
    )
    (comp (ref "D400")
      (value "D5V0L2B3SO")
      (footprint "eagle-import:SOT23")
      (libsource (lib "eagle-import") (part "SOT23-TVS"))
    )
    (comp (ref "J400")
      (value "ICSP")
      (footprint "eagle-import:5P-1.27-POGO")
      (libsource (lib "eagle-import") (part "5P-1.27-POGO"))
    )
    (comp (ref "J401")
      (value "LED")
      (footprint "eagle-import:4PIN")
      (libsource (lib "eagle-import") (part "GEN-4PIN"))
    )
    (comp (ref "J402")
      (value "SWLED")
      (footprint "eagle-import:3PIN")
      (libsource (lib "eagle-import") (part "GEN-3PIN"))
    )
    (comp (ref "J403")
      (value "USB1")
      (footprint "eagle-import:2PIN")
      (libsource (lib "eagle-import") (part "GEN-2PIN"))
    )
    (comp (ref "J404")
      (value "USB2")
      (footprint "eagle-import:2PIN")
      (libsource (lib "eagle-import") (part "GEN-2PIN"))
    )
    (comp (ref "J405")
      (value "ZX62D-B-5PA8")
      (footprint "eagle-import:ZX62D-B-5PA8")
      (libsource (lib "eagle-import") (part "ZX62D-B-5PA8"))
    )
    (comp (ref "J406")
      (value "ZX62D-B-5PA8")
      (footprint "eagle-import:ZX62D-B-5PA8")
      (libsource (lib "eagle-import") (part "ZX62D-B-5PA8"))
    )
    (comp (ref "J408")
      (value "AUX")
      (footprint "eagle-import:4PIN")
      (libsource (lib "eagle-import") (part "GEN-4PIN"))
    )
    (comp (ref "Q400")
      (value "DMG2302UK")
      (footprint "eagle-import:SOT23")
      (libsource (lib "eagle-import") (part "SOT23-N-MOSFET"))
    )
    (comp (ref "Q401")
      (value "DMG2302UK")
      (footprint "eagle-import:SOT23")
      (libsource (lib "eagle-import") (part "SOT23-N-MOSFET"))
    )
    (comp (ref "Q402")
      (value "DMG2302UK")
      (footprint "eagle-import:SOT23")
      (libsource (lib "eagle-import") (part "SOT23-N-MOSFET"))
    )
    (comp (ref "Q403")
      (value "DMG2302UK")
      (footprint "eagle-import:SOT23")
      (libsource (lib "eagle-import") (part "SOT23-N-MOSFET"))
    )
    (comp (ref "Q404")
      (value "NMOS")
      (footprint "eagle-import:SOT23")
      (libsource (lib "eagle-import") (part "SOT23-N-MOSFET"))
    )
    (comp (ref "Q405")
      (value "NMOS")
      (footprint "eagle-import:SOT23")
      (libsource (lib "eagle-import") (part "SOT23-N-MOSFET"))
    )
    (comp (ref "Q406")
      (value "NMOS")
      (footprint "eagle-import:SOT23")
      (libsource (lib "eagle-import") (part "SOT23-N-MOSFET"))
    )
    (comp (ref "R400")
      (value "10kΩ")
      (footprint "eagle-import:R0603")
      (libsource (lib "eagle-import") (part "R-US_R0603"))
    )
    (comp (ref "R401")
      (value "1kΩ")
      (footprint "eagle-import:R0603")
      (libsource (lib "eagle-import") (part "R-US_R0603"))
    )
    (comp (ref "R402")
      (value "10kΩ")
      (footprint "eagle-import:R0603")
      (libsource (lib "eagle-import") (part "R-US_R0603"))
    )
    (comp (ref "R403")
      (value "10kΩ")
      (footprint "eagle-import:R0603")
      (libsource (lib "eagle-import") (part "R-US_R0603"))
    )
    (comp (ref "R404")
      (value "10kΩ")
      (footprint "eagle-import:R0603")
      (libsource (lib "eagle-import") (part "R-US_R0603"))
    )
    (comp (ref "R405")
      (value "1.69kΩ")
      (footprint "eagle-import:R0603")
      (libsource (lib "eagle-import") (part "R-US_R0603"))
    )
    (comp (ref "R406")
      (value "1kΩ")
      (footprint "eagle-import:R0603")
      (libsource (lib "eagle-import") (part "R-US_R0603"))
    )
    (comp (ref "R407")
      (value "110kΩ 0.1%")
      (footprint "eagle-import:R0603")
      (libsource (lib "eagle-import") (part "R-US_R0603"))
    )
    (comp (ref "R408")
      (value "1kΩ 0.1%")
      (footprint "eagle-import:R0603")
      (libsource (lib "eagle-import") (part "R-US_R0603"))
    )
    (comp (ref "R409")
      (value "1kΩ 0.1%")
      (footprint "eagle-import:R0603")
      (libsource (lib "eagle-import") (part "R-US_R0603"))
    )
    (comp (ref "R410")
      (value "110kΩ 0.1%")
      (footprint "eagle-import:R0603")
      (libsource (lib "eagle-import") (part "R-US_R0603"))
    )
    (comp (ref "R411")
      (value "10kΩ")
      (footprint "eagle-import:R0603")
      (libsource (lib "eagle-import") (part "R-US_R0603"))
    )
    (comp (ref "R412")
      (value "10kΩ")
      (footprint "eagle-import:R0603")
      (libsource (lib "eagle-import") (part "R-US_R0603"))
    )
    (comp (ref "R413")
      (value "1kΩ")
      (footprint "eagle-import:R0603")
      (libsource (lib "eagle-import") (part "R-US_R0603"))
    )
    (comp (ref "R414")
      (value "1kΩ")
      (footprint "eagle-import:R0603")
      (libsource (lib "eagle-import") (part "R-US_R0603"))
    )
    (comp (ref "RV400")
      (value "100kΩ")
      (footprint "eagle-import:WIRE-3P-SIMPLE")
      (libsource (lib "eagle-import") (part "WIRED-POTENTIOMETER"))
    )
    (comp (ref "RV401")
      (value "10kΩ")
      (footprint "eagle-import:TC33X-2")
      (libsource (lib "eagle-import") (part "TC33X-2"))
    )
    (comp (ref "SJ400")
      (value "USB-5V")
      (footprint "eagle-import:SJ_2")
      (libsource (lib "eagle-import") (part "SJ2W"))
    )
    (comp (ref "SJ401")
      (value "3.3V-5V")
      (footprint "eagle-import:SJ_2")
      (libsource (lib "eagle-import") (part "SJ2W"))
    )
    (comp (ref "SJ402")
      (value "VBUS")
      (footprint "eagle-import:SJ")
      (libsource (lib "eagle-import") (part "SJ"))
    )
    (comp (ref "SW400")
      (value "VOL-")
      (footprint "eagle-import:WIRE-2P-SIMPLE")
      (libsource (lib "eagle-import") (part "WIRED-SWITCH-NO"))
    )
    (comp (ref "SW401")
      (value "MFB")
      (footprint "eagle-import:WIRE-2P-SIMPLE")
      (libsource (lib "eagle-import") (part "WIRED-SWITCH-NO"))
    )
    (comp (ref "SW402")
      (value "VOL+")
      (footprint "eagle-import:WIRE-2P-SIMPLE")
      (libsource (lib "eagle-import") (part "WIRED-SWITCH-NO"))
    )
    (comp (ref "SW403")
      (value "BACK")
      (footprint "eagle-import:WIRE-2P-SIMPLE")
      (libsource (lib "eagle-import") (part "WIRED-SWITCH-NO"))
    )
    (comp (ref "SW404")
      (value "PLAY")
      (footprint "eagle-import:WIRE-2P-SIMPLE")
      (libsource (lib "eagle-import") (part "WIRED-SWITCH-NO"))
    )
    (comp (ref "SW405")
      (value "FWD")
      (footprint "eagle-import:WIRE-2P-SIMPLE")
      (libsource (lib "eagle-import") (part "WIRED-SWITCH-NO"))
    )
    (comp (ref "SW406")
      (value "LCD_BL")
      (footprint "eagle-import:WIRE-2P-SIMPLE")
      (libsource (lib "eagle-import") (part "WIRED-SWITCH-NO"))
    )
    (comp (ref "SW407")
      (value "LEDMODE")
      (footprint "eagle-import:WIRE-3P-SIMPLE")
      (libsource (lib "eagle-import") (part "WIRED-SWITCH-U"))
    )
    (comp (ref "SW408")
      (value "SDA01H1S")
      (footprint "eagle-import:SDA01H1S")
      (libsource (lib "eagle-import") (part "SDA01H1S"))
    )
    (comp (ref "SW409")
      (value "RESET")
      (footprint "eagle-import:WIRE-2P-SIMPLE")
      (libsource (lib "eagle-import") (part "WIRED-SWITCH-NO"))
    )
    (comp (ref "TP400")
      (value "TPTP15R")
      (footprint "eagle-import:TP15R")
      (fields (field (name "TP_SIGNAL_NAME") "!MCLR"))
      (libsource (lib "eagle-import") (part "TPTP15R"))
    )
    (comp (ref "TP408")
      (value "TPTP15R")
      (footprint "eagle-import:TP15R")
      (fields (field (name "TP_SIGNAL_NAME") "BATT_SENSE"))
      (libsource (lib "eagle-import") (part "TPTP15R"))
    )
    (comp (ref "TP409")
      (value "TPTP15R")
      (footprint "eagle-import:TP15R")
      (fields (field (name "TP_SIGNAL_NAME") "CURR_SENSE"))
      (libsource (lib "eagle-import") (part "TPTP15R"))
    )
    (comp (ref "TP410")
      (value "TPTP15R")
      (footprint "eagle-import:TP15R")
      (fields (field (name "TP_SIGNAL_NAME") "BM_RX"))
      (libsource (lib "eagle-import") (part "TPTP15R"))
    )
    (comp (ref "TP411")
      (value "TPTP15R")
      (footprint "eagle-import:TP15R")
      (fields (field (name "TP_SIGNAL_NAME") "BM_TX"))
      (libsource (lib "eagle-import") (part "TPTP15R"))
    )
    (comp (ref "TP412")
      (value "TPTP15R")
      (footprint "eagle-import:TP15R")
      (fields (field (name "TP_SIGNAL_NAME") "MFB"))
      (libsource (lib "eagle-import") (part "TPTP15R"))
    )
    (comp (ref "TP413")
      (value "TPTP15R")
      (footprint "eagle-import:TP15R")
      (fields (field (name "TP_SIGNAL_NAME") "BM_!RST"))
      (libsource (lib "eagle-import") (part "TPTP15R"))
    )
    (comp (ref "U400")
      (value "PIC32MZ-EF-100")
      (footprint "eagle-import:TQFP100-14X14X1MM")
      (libsource (lib "eagle-import") (part "PIC32MZ-EF-100-I/PF"))
    )
    (comp (ref "U401")
      (value "FT230XS")
      (footprint "eagle-import:SSOP16")
      (libsource (lib "eagle-import") (part "FT230XS"))
    )
    (comp (ref "U402")
      (value "NCS2333")
      (footprint "eagle-import:MSOP8")
      (libsource (lib "eagle-import") (part "NCS2333"))
    )
    (comp (ref "U403")
      (value "FSAL200MTC")
      (footprint "eagle-import:TSSOP16L")
      (libsource (lib "eagle-import") (part "FSAL200MTC"))
    )
    (comp (ref "U404")
      (value "NCS2333")
      (footprint "eagle-import:MSOP8")
      (libsource (lib "eagle-import") (part "NCS2333"))
    )
    (comp (ref "XDS400")
      (value "NHD-3.5-320240FT-CON")
      (footprint "eagle-import:2X9PIN")
      (libsource (lib "eagle-import") (part "NHD-3.5-320240FT-CON"))
    )
    (comp (ref "Y400")
      (value "12MHz")
      (footprint "eagle-import:HC49US")
      (libsource (lib "eagle-import") (part "HC49US-CRYSTAL"))
    )
  )
  (nets
    (net (code "1") (name "3.3V") (class "Default")
      (node (ref "A400") (pin "23") (pinfunction "BAT_IN_23") (pintype "bidirectional"))
      (node (ref "C230") (pin "+") (pinfunction "+_+") (pintype "passive"))
      (node (ref "C329") (pin "1") (pinfunction "1_1") (pintype "passive"))
      (node (ref "C330") (pin "1") (pinfunction "1_1") (pintype "passive"))
      (node (ref "C331") (pin "1") (pinfunction "1_1") (pintype "passive"))
      (node (ref "C332") (pin "1") (pinfunction "1_1") (pintype "passive"))
      (node (ref "C333") (pin "1") (pinfunction "1_1") (pintype "passive"))
      (node (ref "C334") (pin "1") (pinfunction "1_1") (pintype "passive"))
      (node (ref "C401") (pin "1") (pinfunction "1_1") (pintype "passive"))
      (node (ref "C402") (pin "1") (pinfunction "1_1") (pintype "passive"))
      (node (ref "C407") (pin "1") (pinfunction "1_1") (pintype "passive"))
      (node (ref "C408") (pin "1") (pinfunction "1_1") (pintype "passive"))
      (node (ref "C409") (pin "1") (pinfunction "1_1") (pintype "passive"))
      (node (ref "C410") (pin "1") (pinfunction "1_1") (pintype "passive"))
      (node (ref "C411") (pin "1") (pinfunction "1_1") (pintype "passive"))
      (node (ref "C412") (pin "1") (pinfunction "1_1") (pintype "passive"))
      (node (ref "C413") (pin "1") (pinfunction "1_1") (pintype "passive"))
      (node (ref "C414") (pin "1") (pinfunction "1_1") (pintype "passive"))
      (node (ref "C415") (pin "1") (pinfunction "1_1") (pintype "passive"))
      (node (ref "C416") (pin "1") (pinfunction "1_1") (pintype "passive"))
      (node (ref "J400") (pin "2") (pinfunction "2_2") (pintype "passive"))
      (node (ref "R400") (pin "2") (pinfunction "2_2") (pintype "passive"))
      (node (ref "R413") (pin "2") (pinfunction "2_2") (pintype "passive"))
      (node (ref "R414") (pin "2") (pinfunction "2_2") (pintype "passive"))
      (node (ref "RV400") (pin "3") (pinfunction "E_3") (pintype "passive"))
      (node (ref "RV401") (pin "3") (pinfunction "E_3") (pintype "passive"))
      (node (ref "SJ401") (pin "1") (pinfunction "1_1") (pintype "passive"))
      (node (ref "SW408") (pin "2") (pinfunction "2_2") (pintype "passive"))
      (node (ref "TP204") (pin "TP") (pinfunction "TP_TP") (pintype "input"))
      (node (ref "U204") (pin "3") (pinfunction "OUT_3") (pintype "bidirectional"))
      (node (ref "U300") (pin "14") (pinfunction "VDD_14") (pintype "bidirectional"))
      (node (ref "U300") (pin "17") (pinfunction "~{HP_SEL}_17") (pintype "bidirectional"))
      (node (ref "U300") (pin "35") (pinfunction "VDD_35") (pintype "bidirectional"))
      (node (ref "U300") (pin "50") (pinfunction "VDD_50") (pintype "bidirectional"))
      (node (ref "U300") (pin "9") (pinfunction "VDD_9") (pintype "bidirectional"))
      (node (ref "U400") (pin "14") (pinfunction "VDD_14") (pintype "bidirectional"))
      (node (ref "U400") (pin "30") (pinfunction "AVDD_30") (pintype "bidirectional"))
      (node (ref "U400") (pin "37") (pinfunction "VDD_37") (pintype "bidirectional"))
      (node (ref "U400") (pin "46") (pinfunction "VDD_46") (pintype "bidirectional"))
      (node (ref "U400") (pin "62") (pinfunction "VDD_62") (pintype "bidirectional"))
      (node (ref "U400") (pin "74") (pinfunction "VDD_74") (pintype "bidirectional"))
      (node (ref "U400") (pin "83") (pinfunction "VDD_83") (pintype "bidirectional"))
      (node (ref "U400") (pin "93") (pinfunction "VDD_93") (pintype "bidirectional"))
      (node (ref "U401") (pin "10") (pinfunction "3V3OUT_10") (pintype "output"))
      (node (ref "U401") (pin "12") (pinfunction "VCC_12") (pintype "power_in"))
      (node (ref "U401") (pin "3") (pinfunction "VCCIO_3") (pintype "power_in"))
      (node (ref "U402") (pin "8") (pinfunction "V+_8") (pintype "power_in"))
      (node (ref "U403") (pin "16") (pinfunction "VCC_16") (pintype "bidirectional"))
      (node (ref "U404") (pin "8") (pinfunction "V+_8") (pintype "power_in"))
      (node (ref "XDS400") (pin "2") (pinfunction "VDD_2") (pintype "power_in"))
    )
    (net (code "2") (name "3.6V") (class "Default")
      (node (ref "C228") (pin "1") (pinfunction "1_1") (pintype "passive"))
      (node (ref "C229") (pin "1") (pinfunction "1_1") (pintype "passive"))
      (node (ref "L203") (pin "2") (pinfunction "2_2") (pintype "passive"))
      (node (ref "R220") (pin "2") (pinfunction "2_2") (pintype "passive"))
      (node (ref "TP203") (pin "TP") (pinfunction "TP_TP") (pintype "input"))
      (node (ref "U204") (pin "1") (pinfunction "IN_1") (pintype "bidirectional"))
    )
    (net (code "3") (name "5V") (class "Default")
      (node (ref "C217") (pin "1") (pinfunction "1_1") (pintype "passive"))
      (node (ref "C218") (pin "+") (pinfunction "+_+") (pintype "passive"))
      (node (ref "J402") (pin "1") (pinfunction "P$1_1") (pintype "bidirectional"))
      (node (ref "J403") (pin "2") (pinfunction "P$1_2") (pintype "bidirectional"))
      (node (ref "J404") (pin "2") (pinfunction "P$1_2") (pintype "bidirectional"))
      (node (ref "L202") (pin "2") (pinfunction "2_2") (pintype "passive"))
      (node (ref "R218") (pin "2") (pinfunction "2_2") (pintype "passive"))
      (node (ref "SJ400") (pin "3") (pinfunction "3_3") (pintype "passive"))
      (node (ref "SJ401") (pin "3") (pinfunction "3_3") (pintype "passive"))
      (node (ref "TP202") (pin "TP") (pinfunction "TP_TP") (pintype "input"))
    )
    (net (code "4") (name "12V") (class "Default")
      (node (ref "C211") (pin "1") (pinfunction "1_1") (pintype "passive"))
      (node (ref "C212") (pin "+") (pinfunction "+_+") (pintype "passive"))
      (node (ref "C213") (pin "+") (pinfunction "+_+") (pintype "passive"))
      (node (ref "C322") (pin "1") (pinfunction "1_1") (pintype "passive"))
      (node (ref "C323") (pin "1") (pinfunction "1_1") (pintype "passive"))
      (node (ref "C344") (pin "+") (pinfunction "+_+") (pintype "passive"))
      (node (ref "D201") (pin "C") (pinfunction "C_C") (pintype "passive"))
      (node (ref "J401") (pin "1") (pinfunction "P$1_1") (pintype "bidirectional"))
      (node (ref "R213") (pin "2") (pinfunction "2_2") (pintype "passive"))
      (node (ref "R307") (pin "1") (pinfunction "1_1") (pintype "passive"))
      (node (ref "R308") (pin "1") (pinfunction "1_1") (pintype "passive"))
      (node (ref "RT300") (pin "1") (pinfunction "1_1") (pintype "bidirectional"))
      (node (ref "TP201") (pin "TP") (pinfunction "TP_TP") (pintype "input"))
      (node (ref "U301") (pin "2") (pinfunction "VDD_2") (pintype "bidirectional"))
      (node (ref "U302") (pin "5") (pinfunction "V+_5") (pintype "power_in"))
    )
    (net (code "5") (name "AMP_DVDD") (class "Default")
      (node (ref "C326") (pin "1") (pinfunction "1_1") (pintype "passive"))
      (node (ref "SJ301") (pin "1") (pinfunction "1_1") (pintype "passive"))
      (node (ref "U301") (pin "8") (pinfunction "DVDD_8") (pintype "bidirectional"))
    )
    (net (code "6") (name "AMP_PVDD") (class "Default")
      (node (ref "C201") (pin "+") (pinfunction "+_+") (pintype "passive"))
      (node (ref "C202") (pin "+") (pinfunction "+_+") (pintype "passive"))
      (node (ref "C203") (pin "+") (pinfunction "+_+") (pintype "passive"))
      (node (ref "C210") (pin "1") (pinfunction "1_1") (pintype "passive"))
      (node (ref "C316") (pin "1") (pinfunction "1_1") (pintype "passive"))
      (node (ref "C317") (pin "1") (pinfunction "1_1") (pintype "passive"))
      (node (ref "C318") (pin "1") (pinfunction "1_1") (pintype "passive"))
      (node (ref "C319") (pin "1") (pinfunction "1_1") (pintype "passive"))
      (node (ref "C320") (pin "+") (pinfunction "+_+") (pintype "passive"))
      (node (ref "C321") (pin "+") (pinfunction "+_+") (pintype "passive"))
      (node (ref "D200") (pin "C") (pinfunction "C_C") (pintype "passive"))
      (node (ref "R207") (pin "2") (pinfunction "2_2") (pintype "passive"))
      (node (ref "TP200") (pin "TP") (pinfunction "TP_TP") (pintype "input"))
      (node (ref "U301") (pin "29") (pinfunction "PVDD_CD_29") (pintype "bidirectional"))
      (node (ref "U301") (pin "30") (pinfunction "PVDD_CD_30") (pintype "bidirectional"))
      (node (ref "U301") (pin "31") (pinfunction "PVDD_CD_31") (pintype "bidirectional"))
      (node (ref "U301") (pin "36") (pinfunction "PVDD_AB_36") (pintype "bidirectional"))
      (node (ref "U301") (pin "37") (pinfunction "PVDD_AB_37") (pintype "bidirectional"))
      (node (ref "U301") (pin "38") (pinfunction "PVDD_AB_38") (pintype "bidirectional"))
    )
    (net (code "7") (name "AMP_~{CLIP}") (class "Default")
      (node (ref "U301") (pin "18") (pinfunction "~{CLIP}_18") (pintype "bidirectional"))
      (node (ref "U400") (pin "58") (pinfunction "RF8_58") (pintype "bidirectional"))
    )
    (net (code "8") (name "AMP_~{FAULT}") (class "Default")
      (node (ref "U301") (pin "16") (pinfunction "~{FAULT}_16") (pintype "bidirectional"))
      (node (ref "U400") (pin "60") (pinfunction "RA3_60") (pintype "bidirectional"))
    )
    (net (code "9") (name "AMP_~{OTW}") (class "Default")
      (node (ref "U301") (pin "17") (pinfunction "~{OTW}_17") (pintype "bidirectional"))
      (node (ref "U400") (pin "59") (pinfunction "RA2_59") (pintype "bidirectional"))
    )
    (net (code "10") (name "AMP_~{RESET}") (class "Default")
      (node (ref "TP321") (pin "TP") (pinfunction "TP_TP") (pintype "input"))
      (node (ref "U301") (pin "4") (pinfunction "~{RESET}_4") (pintype "bidirectional"))
      (node (ref "U400") (pin "61") (pinfunction "RA4_61") (pintype "bidirectional"))
    )
    (net (code "11") (name "BAT-") (class "Default")
      (node (ref "C103") (pin "2") (pinfunction "2_2") (pintype "passive"))
      (node (ref "C104") (pin "2") (pinfunction "2_2") (pintype "passive"))
      (node (ref "C105") (pin "1") (pinfunction "1_1") (pintype "passive"))
      (node (ref "C107") (pin "1") (pinfunction "1_1") (pintype "passive"))
      (node (ref "C108") (pin "2") (pinfunction "2_2") (pintype "passive"))
      (node (ref "C109") (pin "2") (pinfunction "2_2") (pintype "passive"))
      (node (ref "C402") (pin "2") (pinfunction "2_2") (pintype "passive"))
      (node (ref "R104") (pin "1") (pinfunction "1_1") (pintype "passive"))
      (node (ref "R105") (pin "1") (pinfunction "1_1") (pintype "passive"))
      (node (ref "R106") (pin "1") (pinfunction "1_1") (pintype "passive"))
      (node (ref "R115") (pin "2") (pinfunction "2_2") (pintype "passive"))
      (node (ref "R405") (pin "1") (pinfunction "1_1") (pintype "passive"))
      (node (ref "R410") (pin "1") (pinfunction "1_1") (pintype "passive"))
      (node (ref "TP103") (pin "TP") (pinfunction "TP_TP") (pintype "input"))
      (node (ref "U100") (pin "23") (pinfunction "CTRC_23") (pintype "bidirectional"))
      (node (ref "U100") (pin "24") (pinfunction "CTRD_24") (pintype "bidirectional"))
      (node (ref "U100") (pin "9") (pinfunction "VSS_9") (pintype "bidirectional"))
      (node (ref "U402") (pin "4") (pinfunction "V-_4") (pintype "power_in"))
      (node (ref "XBT100") (pin "5") (pinfunction "-_5") (pintype "bidirectional"))
      (node (ref "XBT100") (pin "6") (pinfunction "-_6") (pintype "bidirectional"))
    )
    (net (code "12") (name "BAT_CSN") (class "Default")
      (node (ref "C106") (pin "2") (pinfunction "2_2") (pintype "passive"))
      (node (ref "C107") (pin "2") (pinfunction "2_2") (pintype "passive"))
      (node (ref "R107") (pin "2") (pinfunction "2_2") (pintype "passive"))
      (node (ref "R409") (pin "2") (pinfunction "2_2") (pintype "passive"))
      (node (ref "U100") (pin "11") (pinfunction "SRN_11") (pintype "bidirectional"))
    )
    (net (code "13") (name "BAT_CSP") (class "Default")
      (node (ref "C105") (pin "2") (pinfunction "2_2") (pintype "passive"))
      (node (ref "C106") (pin "1") (pinfunction "1_1") (pintype "passive"))
      (node (ref "R106") (pin "2") (pinfunction "2_2") (pintype "passive"))
      (node (ref "R408") (pin "2") (pinfunction "2_2") (pintype "passive"))
      (node (ref "U100") (pin "10") (pinfunction "SRP_10") (pintype "bidirectional"))
    )
    (net (code "14") (name "BAT_THERM") (class "Default")
      (node (ref "R114") (pin "2") (pinfunction "2_2") (pintype "passive"))
      (node (ref "U100") (pin "18") (pinfunction "TS_18") (pintype "bidirectional"))
      (node (ref "XBT100") (pin "8") (pinfunction "THERM1_8") (pintype "bidirectional"))
    )
    (net (code "15") (name "BM_USB_VBUS") (class "Default")
      (node (ref "J406") (pin "1") (pinfunction "VBUS_1") (pintype "passive"))
      (node (ref "SJ400") (pin "1") (pinfunction "1_1") (pintype "passive"))
    )
    (net (code "16") (name "CHG_ISETIN") (class "Default")
      (node (ref "R123") (pin "1") (pinfunction "1_1") (pintype "passive"))
      (node (ref "R124") (pin "2") (pinfunction "2_2") (pintype "passive"))
      (node (ref "U101") (pin "2") (pinfunction "ISETIN_2") (pintype "bidirectional"))
    )
    (net (code "17") (name "CHG_ISETOUT") (class "Default")
      (node (ref "R125") (pin "1") (pinfunction "1_1") (pintype "passive"))
      (node (ref "R126") (pin "2") (pinfunction "2_2") (pintype "passive"))
      (node (ref "U101") (pin "3") (pinfunction "ISETOUT_3") (pintype "bidirectional"))
    )
    (net (code "18") (name "CHG_REF") (class "Default")
      (node (ref "C118") (pin "1") (pinfunction "1_1") (pintype "passive"))
      (node (ref "R120") (pin "2") (pinfunction "2_2") (pintype "passive"))
      (node (ref "R122") (pin "2") (pinfunction "2_2") (pintype "passive"))
      (node (ref "R125") (pin "2") (pinfunction "2_2") (pintype "passive"))
      (node (ref "U101") (pin "5") (pinfunction "REF_5") (pintype "bidirectional"))
    )
    (net (code "19") (name "CHG_VADJ") (class "Default")
      (node (ref "R120") (pin "1") (pinfunction "1_1") (pintype "passive"))
      (node (ref "R121") (pin "2") (pinfunction "2_2") (pintype "passive"))
      (node (ref "U101") (pin "8") (pinfunction "VADJ_8") (pintype "bidirectional"))
    )
    (net (code "20") (name "CHG_VL") (class "Default")
      (node (ref "C119") (pin "1") (pinfunction "1_1") (pintype "passive"))
      (node (ref "C120") (pin "1") (pinfunction "1_1") (pintype "passive"))
      (node (ref "U101") (pin "1") (pinfunction "VL_1") (pintype "bidirectional"))
      (node (ref "U101") (pin "12") (pinfunction "CELL_12") (pintype "bidirectional"))
    )
    (net (code "21") (name "CHG_~{FASTCHG}") (class "Default")
      (node (ref "TP105") (pin "TP") (pinfunction "TP_TP") (pintype "input"))
      (node (ref "U101") (pin "16") (pinfunction "~{FASTCHG}_16") (pintype "bidirectional"))
      (node (ref "U400") (pin "33") (pinfunction "RB9_33") (pintype "bidirectional"))
    )
    (net (code "22") (name "CHG_~{FAULT}") (class "Default")
      (node (ref "TP106") (pin "TP") (pinfunction "TP_TP") (pintype "input"))
      (node (ref "U101") (pin "15") (pinfunction "~{FAULT}_15") (pintype "bidirectional"))
      (node (ref "U400") (pin "34") (pinfunction "RB10_34") (pintype "bidirectional"))
    )
    (net (code "23") (name "CHG_~{FULLCHG}") (class "Default")
      (node (ref "TP104") (pin "TP") (pinfunction "TP_TP") (pintype "input"))
      (node (ref "U101") (pin "17") (pinfunction "~{FULLCHG}_17") (pintype "bidirectional"))
      (node (ref "U400") (pin "32") (pinfunction "RB8_32") (pintype "bidirectional"))
    )
    (net (code "24") (name "CHG_~{SHDN}") (class "Default")
      (node (ref "D102") (pin "1") (pinfunction "C_1") (pintype "passive"))
      (node (ref "R128") (pin "2") (pinfunction "2_2") (pintype "passive"))
      (node (ref "U101") (pin "18") (pinfunction "~{SHDN}_18") (pintype "bidirectional"))
    )
    (net (code "25") (name "DSP_EMO1") (class "Default")
      (node (ref "TP300") (pin "TP") (pinfunction "TP_TP") (pintype "input"))
      (node (ref "U300") (pin "15") (pinfunction "EMO1_15") (pintype "bidirectional"))
      (node (ref "U400") (pin "71") (pinfunction "RD0_71") (pintype "bidirectional"))
    )
    (net (code "26") (name "DSP_SCL") (class "Default")
      (node (ref "R414") (pin "1") (pinfunction "1_1") (pintype "passive"))
      (node (ref "TP305") (pin "TP") (pinfunction "TP_TP") (pintype "input"))
      (node (ref "U300") (pin "21") (pinfunction "SCL_21") (pintype "bidirectional"))
      (node (ref "U400") (pin "66") (pinfunction "RA14_66") (pintype "bidirectional"))
    )
    (net (code "27") (name "DSP_SDA") (class "Default")
      (node (ref "R413") (pin "1") (pinfunction "1_1") (pintype "passive"))
      (node (ref "TP304") (pin "TP") (pinfunction "TP_TP") (pintype "input"))
      (node (ref "U300") (pin "20") (pinfunction "SDA_20") (pintype "bidirectional"))
      (node (ref "U400") (pin "67") (pinfunction "RA15_67") (pintype "bidirectional"))
    )
    (net (code "28") (name "DSP_VALID") (class "Default")
      (node (ref "TP309") (pin "TP") (pinfunction "TP_TP") (pintype "input"))
      (node (ref "U300") (pin "37") (pinfunction "VALID_37") (pintype "bidirectional"))
      (node (ref "U400") (pin "64") (pinfunction "RF4_64") (pintype "bidirectional"))
    )
    (net (code "29") (name "DSP_~{BKND_ERR}") (class "Default")
      (node (ref "TP310") (pin "TP") (pinfunction "TP_TP") (pintype "input"))
      (node (ref "U300") (pin "34") (pinfunction "~{BKND_ERR}_34") (pintype "bidirectional"))
      (node (ref "U400") (pin "65") (pinfunction "RF5_65") (pintype "bidirectional"))
    )
    (net (code "30") (name "DSP_~{MUTE}") (class "Default")
      (node (ref "TP303") (pin "TP") (pinfunction "TP_TP") (pintype "input"))
      (node (ref "U300") (pin "19") (pinfunction "~{MUTE}_19") (pintype "bidirectional"))
      (node (ref "U400") (pin "68") (pinfunction "RD9_68") (pintype "bidirectional"))
    )
    (net (code "31") (name "DSP_~{PDN}") (class "Default")
      (node (ref "TP302") (pin "TP") (pinfunction "TP_TP") (pintype "input"))
      (node (ref "U300") (pin "18") (pinfunction "~{PDN}_18") (pintype "bidirectional"))
      (node (ref "U400") (pin "69") (pinfunction "RD10_69") (pintype "bidirectional"))
    )
    (net (code "32") (name "DSP_~{RESET}") (class "Default")
      (node (ref "TP301") (pin "TP") (pinfunction "TP_TP") (pintype "input"))
      (node (ref "U300") (pin "16") (pinfunction "~{RESET}_16") (pintype "bidirectional"))
      (node (ref "U400") (pin "70") (pinfunction "RD11_70") (pintype "bidirectional"))
    )
    (net (code "33") (name "GND") (class "Default")
      (node (ref "A400") (pin "16") (pinfunction "GND_16") (pintype "bidirectional"))
      (node (ref "A400") (pin "50") (pinfunction "GND_50") (pintype "bidirectional"))
      (node (ref "A400") (pin "G1") (pinfunction "GND_G1") (pintype "bidirectional"))
      (node (ref "A400") (pin "G2") (pinfunction "GND_G2") (pintype "bidirectional"))
      (node (ref "C111") (pin "2") (pinfunction "2_2") (pintype "passive"))
      (node (ref "C112") (pin "2") (pinfunction "2_2") (pintype "passive"))
      (node (ref "C113") (pin "2") (pinfunction "2_2") (pintype "passive"))
      (node (ref "C114") (pin "2") (pinfunction "2_2") (pintype "passive"))
      (node (ref "C115") (pin "2") (pinfunction "2_2") (pintype "passive"))
      (node (ref "C116") (pin "2") (pinfunction "2_2") (pintype "passive"))
      (node (ref "C117") (pin "2") (pinfunction "2_2") (pintype "passive"))
      (node (ref "C118") (pin "2") (pinfunction "2_2") (pintype "passive"))
      (node (ref "C119") (pin "2") (pinfunction "2_2") (pintype "passive"))
      (node (ref "C120") (pin "2") (pinfunction "2_2") (pintype "passive"))
      (node (ref "C121") (pin "2") (pinfunction "2_2") (pintype "passive"))
      (node (ref "C122") (pin "2") (pinfunction "2_2") (pintype "passive"))
      (node (ref "C123") (pin "2") (pinfunction "2_2") (pintype "passive"))
      (node (ref "C124") (pin "2") (pinfunction "2_2") (pintype "passive"))
      (node (ref "C125") (pin "2") (pinfunction "2_2") (pintype "passive"))
      (node (ref "C127") (pin "2") (pinfunction "2_2") (pintype "passive"))
      (node (ref "C128") (pin "2") (pinfunction "2_2") (pintype "passive"))
      (node (ref "C129") (pin "-") (pinfunction "-_-") (pintype "passive"))
      (node (ref "C130") (pin "-") (pinfunction "-_-") (pintype "passive"))
      (node (ref "C131") (pin "2") (pinfunction "2_2") (pintype "passive"))
      (node (ref "C132") (pin "2") (pinfunction "2_2") (pintype "passive"))
      (node (ref "C134") (pin "2") (pinfunction "2_2") (pintype "passive"))
      (node (ref "C135") (pin "2") (pinfunction "2_2") (pintype "passive"))
      (node (ref "C200") (pin "-") (pinfunction "-_-") (pintype "passive"))
      (node (ref "C201") (pin "-") (pinfunction "-_-") (pintype "passive"))
      (node (ref "C202") (pin "-") (pinfunction "-_-") (pintype "passive"))
      (node (ref "C203") (pin "-") (pinfunction "-_-") (pintype "passive"))
      (node (ref "C204") (pin "2") (pinfunction "2_2") (pintype "passive"))
      (node (ref "C205") (pin "2") (pinfunction "2_2") (pintype "passive"))
      (node (ref "C206") (pin "2") (pinfunction "2_2") (pintype "passive"))
      (node (ref "C209") (pin "2") (pinfunction "2_2") (pintype "passive"))
      (node (ref "C210") (pin "2") (pinfunction "2_2") (pintype "passive"))
      (node (ref "C211") (pin "2") (pinfunction "2_2") (pintype "passive"))
      (node (ref "C212") (pin "-") (pinfunction "-_-") (pintype "passive"))
      (node (ref "C213") (pin "-") (pinfunction "-_-") (pintype "passive"))
      (node (ref "C214") (pin "2") (pinfunction "2_2") (pintype "passive"))
      (node (ref "C218") (pin "-") (pinfunction "-_-") (pintype "passive"))
      (node (ref "C219") (pin "2") (pinfunction "2_2") (pintype "passive"))
      (node (ref "C220") (pin "2") (pinfunction "2_2") (pintype "passive"))
      (node (ref "C221") (pin "2") (pinfunction "2_2") (pintype "passive"))
      (node (ref "C222") (pin "2") (pinfunction "2_2") (pintype "passive"))
      (node (ref "C223") (pin "2") (pinfunction "2_2") (pintype "passive"))
      (node (ref "C225") (pin "2") (pinfunction "2_2") (pintype "passive"))
      (node (ref "C226") (pin "2") (pinfunction "2_2") (pintype "passive"))
      (node (ref "C228") (pin "2") (pinfunction "2_2") (pintype "passive"))
      (node (ref "C229") (pin "2") (pinfunction "2_2") (pintype "passive"))
      (node (ref "C230") (pin "-") (pinfunction "-_-") (pintype "passive"))
      (node (ref "C300") (pin "2") (pinfunction "2_2") (pintype "passive"))
      (node (ref "C301") (pin "2") (pinfunction "2_2") (pintype "passive"))
      (node (ref "C302") (pin "2") (pinfunction "2_2") (pintype "passive"))
      (node (ref "C303") (pin "2") (pinfunction "2_2") (pintype "passive"))
      (node (ref "C304") (pin "2") (pinfunction "2_2") (pintype "passive"))
      (node (ref "C305") (pin "1") (pinfunction "1_1") (pintype "passive"))
      (node (ref "C306") (pin "2") (pinfunction "2_2") (pintype "passive"))
      (node (ref "C307") (pin "1") (pinfunction "1_1") (pintype "passive"))
      (node (ref "C316") (pin "2") (pinfunction "2_2") (pintype "passive"))
      (node (ref "C317") (pin "2") (pinfunction "2_2") (pintype "passive"))
      (node (ref "C318") (pin "2") (pinfunction "2_2") (pintype "passive"))
      (node (ref "C319") (pin "2") (pinfunction "2_2") (pintype "passive"))
      (node (ref "C320") (pin "-") (pinfunction "-_-") (pintype "passive"))
      (node (ref "C321") (pin "-") (pinfunction "-_-") (pintype "passive"))
      (node (ref "C322") (pin "2") (pinfunction "2_2") (pintype "passive"))
      (node (ref "C323") (pin "2") (pinfunction "2_2") (pintype "passive"))
      (node (ref "C324") (pin "2") (pinfunction "2_2") (pintype "passive"))
      (node (ref "C325") (pin "2") (pinfunction "2_2") (pintype "passive"))
      (node (ref "C326") (pin "2") (pinfunction "2_2") (pintype "passive"))
      (node (ref "C327") (pin "2") (pinfunction "2_2") (pintype "passive"))
      (node (ref "C328") (pin "2") (pinfunction "2_2") (pintype "passive"))
      (node (ref "C329") (pin "2") (pinfunction "2_2") (pintype "passive"))
      (node (ref "C330") (pin "2") (pinfunction "2_2") (pintype "passive"))
      (node (ref "C331") (pin "2") (pinfunction "2_2") (pintype "passive"))
      (node (ref "C332") (pin "2") (pinfunction "2_2") (pintype "passive"))
      (node (ref "C333") (pin "2") (pinfunction "2_2") (pintype "passive"))
      (node (ref "C334") (pin "2") (pinfunction "2_2") (pintype "passive"))
      (node (ref "C335") (pin "2") (pinfunction "2_2") (pintype "passive"))
      (node (ref "C336") (pin "2") (pinfunction "2_2") (pintype "passive"))
      (node (ref "C337") (pin "2") (pinfunction "2_2") (pintype "passive"))
      (node (ref "C338") (pin "1") (pinfunction "1_1") (pintype "passive"))
      (node (ref "C339") (pin "1") (pinfunction "1_1") (pintype "passive"))
      (node (ref "C342") (pin "2") (pinfunction "2_2") (pintype "passive"))
      (node (ref "C344") (pin "-") (pinfunction "-_-") (pintype "passive"))
      (node (ref "C400") (pin "2") (pinfunction "2_2") (pintype "passive"))
      (node (ref "C401") (pin "2") (pinfunction "2_2") (pintype "passive"))
      (node (ref "C403") (pin "2") (pinfunction "2_2") (pintype "passive"))
      (node (ref "C404") (pin "2") (pinfunction "2_2") (pintype "passive"))
      (node (ref "C405") (pin "1") (pinfunction "1_1") (pintype "passive"))
      (node (ref "C406") (pin "1") (pinfunction "1_1") (pintype "passive"))
      (node (ref "C407") (pin "2") (pinfunction "2_2") (pintype "passive"))
      (node (ref "C408") (pin "2") (pinfunction "2_2") (pintype "passive"))
      (node (ref "C409") (pin "2") (pinfunction "2_2") (pintype "passive"))
      (node (ref "C410") (pin "2") (pinfunction "2_2") (pintype "passive"))
      (node (ref "C411") (pin "2") (pinfunction "2_2") (pintype "passive"))
      (node (ref "C412") (pin "2") (pinfunction "2_2") (pintype "passive"))
      (node (ref "C413") (pin "2") (pinfunction "2_2") (pintype "passive"))
      (node (ref "C414") (pin "2") (pinfunction "2_2") (pintype "passive"))
      (node (ref "C415") (pin "2") (pinfunction "2_2") (pintype "passive"))
      (node (ref "C416") (pin "2") (pinfunction "2_2") (pintype "passive"))
      (node (ref "D102") (pin "2") (pinfunction "A_2") (pintype "passive"))
      (node (ref "D103") (pin "A") (pinfunction "A_A") (pintype "passive"))
      (node (ref "D202") (pin "A") (pinfunction "A_A") (pintype "passive"))
      (node (ref "D400") (pin "3") (pinfunction "C_3") (pintype "passive"))
      (node (ref "FAN300") (pin "2") (pinfunction "-_2") (pintype "bidirectional"))
      (node (ref "H300") (pin "H1") (pinfunction "GND_H1") (pintype "bidirectional"))
      (node (ref "H300") (pin "H2") (pinfunction "GND_H2") (pintype "bidirectional"))
      (node (ref "J100") (pin "2") (pinfunction "2_2") (pintype "passive"))
      (node (ref "J400") (pin "3") (pinfunction "3_3") (pintype "passive"))
      (node (ref "J403") (pin "1") (pinfunction "P$1_1") (pintype "bidirectional"))
      (node (ref "J404") (pin "1") (pinfunction "P$1_1") (pintype "bidirectional"))
      (node (ref "J405") (pin "5") (pinfunction "GND_5") (pintype "passive"))
      (node (ref "J405") (pin "S1") (pinfunction "GND_S1") (pintype "passive"))
      (node (ref "J405") (pin "S2") (pinfunction "GND_S2") (pintype "passive"))
      (node (ref "J405") (pin "S3") (pinfunction "GND_S3") (pintype "passive"))
      (node (ref "J405") (pin "S4") (pinfunction "GND_S4") (pintype "passive"))
      (node (ref "J406") (pin "5") (pinfunction "GND_5") (pintype "passive"))
      (node (ref "J406") (pin "S1") (pinfunction "GND_S1") (pintype "passive"))
      (node (ref "J406") (pin "S2") (pinfunction "GND_S2") (pintype "passive"))
      (node (ref "J406") (pin "S3") (pinfunction "GND_S3") (pintype "passive"))
      (node (ref "J406") (pin "S4") (pinfunction "GND_S4") (pintype "passive"))
      (node (ref "J408") (pin "1") (pinfunction "P$1_1") (pintype "bidirectional"))
      (node (ref "L201") (pin "2") (pinfunction "S1_2") (pintype "passive"))
      (node (ref "Q101") (pin "S") (pinfunction "S_S") (pintype "passive"))
      (node (ref "Q103") (pin "S") (pinfunction "S_S") (pintype "passive"))
      (node (ref "Q400") (pin "2") (pinfunction "S_2") (pintype "passive"))
      (node (ref "Q401") (pin "2") (pinfunction "S_2") (pintype "passive"))
      (node (ref "Q402") (pin "2") (pinfunction "S_2") (pintype "passive"))
      (node (ref "Q403") (pin "2") (pinfunction "S_2") (pintype "passive"))
      (node (ref "Q404") (pin "2") (pinfunction "S_2") (pintype "passive"))
      (node (ref "Q405") (pin "2") (pinfunction "S_2") (pintype "passive"))
      (node (ref "Q406") (pin "2") (pinfunction "S_2") (pintype "passive"))
      (node (ref "R111") (pin "1") (pinfunction "1_1") (pintype "passive"))
      (node (ref "R112") (pin "1") (pinfunction "1_1") (pintype "passive"))
      (node (ref "R119") (pin "1") (pinfunction "1_1") (pintype "passive"))
      (node (ref "R121") (pin "1") (pinfunction "1_1") (pintype "passive"))
      (node (ref "R124") (pin "1") (pinfunction "1_1") (pintype "passive"))
      (node (ref "R126") (pin "1") (pinfunction "1_1") (pintype "passive"))
      (node (ref "R201") (pin "1") (pinfunction "1_1") (pintype "passive"))
      (node (ref "R202") (pin "1") (pinfunction "1_1") (pintype "passive"))
      (node (ref "R206") (pin "1") (pinfunction "1_1") (pintype "passive"))
      (node (ref "R210") (pin "2") (pinfunction "2_2") (pintype "passive"))
      (node (ref "R212") (pin "1") (pinfunction "1_1") (pintype "passive"))
      (node (ref "R214") (pin "1") (pinfunction "1_1") (pintype "passive"))
      (node (ref "R219") (pin "1") (pinfunction "1_1") (pintype "passive"))
      (node (ref "R221") (pin "1") (pinfunction "1_1") (pintype "passive"))
      (node (ref "R300") (pin "1") (pinfunction "1_1") (pintype "passive"))
      (node (ref "R301") (pin "2") (pinfunction "2_2") (pintype "passive"))
      (node (ref "R303") (pin "1") (pinfunction "1_1") (pintype "passive"))
      (node (ref "R304") (pin "1") (pinfunction "1_1") (pintype "passive"))
      (node (ref "R305") (pin "1") (pinfunction "1_1") (pintype "passive"))
      (node (ref "R306") (pin "1") (pinfunction "1_1") (pintype "passive"))
      (node (ref "R309") (pin "1") (pinfunction "1_1") (pintype "passive"))
      (node (ref "R312") (pin "2") (pinfunction "2_2") (pintype "passive"))
      (node (ref "R313") (pin "1") (pinfunction "1_1") (pintype "passive"))
      (node (ref "R402") (pin "1") (pinfunction "1_1") (pintype "passive"))
      (node (ref "R403") (pin "1") (pinfunction "1_1") (pintype "passive"))
      (node (ref "RV200") (pin "3") (pinfunction "E_3") (pintype "passive"))
      (node (ref "RV400") (pin "1") (pinfunction "A_1") (pintype "passive"))
      (node (ref "RV401") (pin "1") (pinfunction "A_1") (pintype "passive"))
      (node (ref "SJ301") (pin "3") (pinfunction "3_3") (pintype "passive"))
      (node (ref "SW400") (pin "2") (pinfunction "2_2") (pintype "passive"))
      (node (ref "SW401") (pin "2") (pinfunction "2_2") (pintype "passive"))
      (node (ref "SW402") (pin "2") (pinfunction "2_2") (pintype "passive"))
      (node (ref "SW403") (pin "2") (pinfunction "2_2") (pintype "passive"))
      (node (ref "SW404") (pin "2") (pinfunction "2_2") (pintype "passive"))
      (node (ref "SW405") (pin "2") (pinfunction "2_2") (pintype "passive"))
      (node (ref "SW406") (pin "2") (pinfunction "2_2") (pintype "passive"))
      (node (ref "SW407") (pin "2") (pinfunction "P_2") (pintype "passive"))
      (node (ref "SW409") (pin "1") (pinfunction "1_1") (pintype "passive"))
      (node (ref "TP107") (pin "TP") (pinfunction "TP_TP") (pintype "input"))
      (node (ref "TP108") (pin "TP") (pinfunction "TP_TP") (pintype "input"))
      (node (ref "TP109") (pin "TP") (pinfunction "TP_TP") (pintype "input"))
      (node (ref "U101") (pin "20") (pinfunction "PGND_20") (pintype "bidirectional"))
      (node (ref "U101") (pin "6") (pinfunction "GND_6") (pintype "bidirectional"))
      (node (ref "U102") (pin "2") (pinfunction "GND_2") (pintype "bidirectional"))
      (node (ref "U103") (pin "2") (pinfunction "GND_2") (pintype "bidirectional"))
      (node (ref "U104") (pin "2") (pinfunction "GND_2") (pintype "bidirectional"))
      (node (ref "U200") (pin "6") (pinfunction "GND_6") (pintype "bidirectional"))
      (node (ref "U201") (pin "4") (pinfunction "AGND_4") (pintype "bidirectional"))
      (node (ref "U201") (pin "5") (pinfunction "PGND_5") (pintype "bidirectional"))
      (node (ref "U202") (pin "4") (pinfunction "GND_4") (pintype "bidirectional"))
      (node (ref "U203") (pin "1") (pinfunction "GND_1") (pintype "bidirectional"))
      (node (ref "U204") (pin "TAB") (pinfunction "GND_TAB") (pintype "bidirectional"))
      (node (ref "U300") (pin "13") (pinfunction "VSS_13") (pintype "bidirectional"))
      (node (ref "U300") (pin "32") (pinfunction "TEST_32") (pintype "bidirectional"))
      (node (ref "U300") (pin "36") (pinfunction "VSS_36") (pintype "bidirectional"))
      (node (ref "U300") (pin "5") (pinfunction "VSS_5") (pintype "bidirectional"))
      (node (ref "U300") (pin "51") (pinfunction "VSS_51") (pintype "bidirectional"))
      (node (ref "U300") (pin "EXP") (pinfunction "VSS_EXP") (pintype "bidirectional"))
      (node (ref "U301") (pin "10") (pinfunction "GND_10") (pintype "bidirectional"))
      (node (ref "U301") (pin "11") (pinfunction "GND_11") (pintype "bidirectional"))
      (node (ref "U301") (pin "12") (pinfunction "GND_12") (pintype "bidirectional"))
      (node (ref "U301") (pin "19") (pinfunction "M1_19") (pintype "bidirectional"))
      (node (ref "U301") (pin "21") (pinfunction "M3_21") (pintype "bidirectional"))
      (node (ref "U301") (pin "25") (pinfunction "GND_25") (pintype "bidirectional"))
      (node (ref "U301") (pin "26") (pinfunction "GND_26") (pintype "bidirectional"))
      (node (ref "U301") (pin "33") (pinfunction "GND_33") (pintype "bidirectional"))
      (node (ref "U301") (pin "34") (pinfunction "GND_34") (pintype "bidirectional"))
      (node (ref "U301") (pin "41") (pinfunction "GND_41") (pintype "bidirectional"))
      (node (ref "U301") (pin "42") (pinfunction "GND_42") (pintype "bidirectional"))
      (node (ref "U301") (pin "9") (pinfunction "GND_9") (pintype "bidirectional"))
      (node (ref "U302") (pin "2") (pinfunction "V-_2") (pintype "power_in"))
      (node (ref "U400") (pin "13") (pinfunction "VSS_13") (pintype "bidirectional"))
      (node (ref "U400") (pin "31") (pinfunction "AVSS_31") (pintype "bidirectional"))
      (node (ref "U400") (pin "36") (pinfunction "VSS_36") (pintype "bidirectional"))
      (node (ref "U400") (pin "45") (pinfunction "VSS_45") (pintype "bidirectional"))
      (node (ref "U400") (pin "52") (pinfunction "VUSB3V3_52") (pintype "bidirectional"))
      (node (ref "U400") (pin "53") (pinfunction "VSS_53") (pintype "bidirectional"))
      (node (ref "U400") (pin "63") (pinfunction "VSS_63") (pintype "bidirectional"))
      (node (ref "U400") (pin "75") (pinfunction "VSS_75") (pintype "bidirectional"))
      (node (ref "U400") (pin "84") (pinfunction "VSS_84") (pintype "bidirectional"))
      (node (ref "U400") (pin "92") (pinfunction "VSS_92") (pintype "bidirectional"))
      (node (ref "U401") (pin "13") (pinfunction "GND_13") (pintype "power_in"))
      (node (ref "U401") (pin "5") (pinfunction "GND_5") (pintype "power_in"))
      (node (ref "U403") (pin "15") (pinfunction "~{OE}_15") (pintype "bidirectional"))
      (node (ref "U403") (pin "8") (pinfunction "GND_8") (pintype "bidirectional"))
      (node (ref "U404") (pin "4") (pinfunction "V-_4") (pintype "power_in"))
      (node (ref "XDS400") (pin "1") (pinfunction "GND_1") (pintype "power_in"))
    )
    (net (code "34") (name "I2S_LRCLK") (class "Default")
      (node (ref "A400") (pin "2") (pinfunction "RFS1_2") (pintype "bidirectional"))
      (node (ref "TP306") (pin "TP") (pinfunction "TP_TP") (pintype "input"))
      (node (ref "U300") (pin "22") (pinfunction "LRCLK_22") (pintype "bidirectional"))
      (node (ref "U400") (pin "79") (pinfunction "RD12_79") (pintype "bidirectional"))
    )
    (net (code "35") (name "I2S_SCLK") (class "Default")
      (node (ref "A400") (pin "3") (pinfunction "SCLK1_3") (pintype "bidirectional"))
      (node (ref "TP307") (pin "TP") (pinfunction "TP_TP") (pintype "input"))
      (node (ref "U300") (pin "23") (pinfunction "SCLK_23") (pintype "bidirectional"))
      (node (ref "U400") (pin "76") (pinfunction "RD1_76") (pintype "bidirectional"))
    )
    (net (code "36") (name "I2S_SD") (class "Default")
      (node (ref "A400") (pin "4") (pinfunction "DT1_4") (pintype "bidirectional"))
      (node (ref "TP308") (pin "TP") (pinfunction "TP_TP") (pintype "input"))
      (node (ref "U300") (pin "24") (pinfunction "SDIN1_24") (pintype "bidirectional"))
      (node (ref "U400") (pin "77") (pinfunction "RD2_77") (pintype "bidirectional"))
    )
    (net (code "37") (name "Net-(A400-ADAP_IN)") (class "Default")
      (node (ref "A400") (pin "22") (pinfunction "ADAP_IN_22") (pintype "bidirectional"))
      (node (ref "SJ400") (pin "2") (pinfunction "2_2") (pintype "passive"))
    )
    (net (code "38") (name "Net-(A400-AIL)") (class "Default")
      (node (ref "A400") (pin "12") (pinfunction "AIL_12") (pintype "bidirectional"))
      (node (ref "D400") (pin "1") (pinfunction "1_1") (pintype "passive"))
      (node (ref "J408") (pin "3") (pinfunction "P$1_3") (pintype "bidirectional"))
    )
    (net (code "39") (name "Net-(A400-AIR)") (class "Default")
      (node (ref "A400") (pin "11") (pinfunction "AIR_11") (pintype "bidirectional"))
      (node (ref "D400") (pin "2") (pinfunction "2_2") (pintype "passive"))
      (node (ref "J408") (pin "2") (pinfunction "P$1_2") (pintype "bidirectional"))
    )
    (net (code "40") (name "Net-(A400-DM)") (class "Default")
      (node (ref "A400") (pin "36") (pinfunction "DM_36") (pintype "bidirectional"))
      (node (ref "J406") (pin "2") (pinfunction "D-_2") (pintype "passive"))
    )
    (net (code "41") (name "Net-(A400-DP)") (class "Default")
      (node (ref "A400") (pin "37") (pinfunction "DP_37") (pintype "bidirectional"))
      (node (ref "J406") (pin "3") (pinfunction "D+_3") (pintype "passive"))
    )
    (net (code "42") (name "Net-(A400-MFB)") (class "Default")
      (node (ref "A400") (pin "26") (pinfunction "MFB_26") (pintype "bidirectional"))
      (node (ref "TP412") (pin "TP") (pinfunction "TP_TP") (pintype "input"))
      (node (ref "U400") (pin "85") (pinfunction "RF0_85") (pintype "bidirectional"))
    )
    (net (code "43") (name "Net-(A400-P3_4{slash}UART_RTS)") (class "Default")
      (node (ref "A400") (pin "31") (pinfunction "P3_4/UART_RTS_31") (pintype "bidirectional"))
      (node (ref "Q406") (pin "3") (pinfunction "D_3") (pintype "passive"))
    )
    (net (code "44") (name "Net-(A400-RST_N)") (class "Default")
      (node (ref "A400") (pin "43") (pinfunction "RST_N_43") (pintype "bidirectional"))
      (node (ref "TP413") (pin "TP") (pinfunction "TP_TP") (pintype "input"))
      (node (ref "U400") (pin "80") (pinfunction "RD13_80") (pintype "bidirectional"))
    )
    (net (code "45") (name "Net-(A400-UART_RXD)") (class "Default")
      (node (ref "A400") (pin "29") (pinfunction "UART_RXD_29") (pintype "bidirectional"))
      (node (ref "TP410") (pin "TP") (pinfunction "TP_TP") (pintype "input"))
      (node (ref "U403") (pin "4") (pinfunction "A_4") (pintype "bidirectional"))
    )
    (net (code "46") (name "Net-(A400-UART_TXD)") (class "Default")
      (node (ref "A400") (pin "30") (pinfunction "UART_TXD_30") (pintype "bidirectional"))
      (node (ref "TP411") (pin "TP") (pinfunction "TP_TP") (pintype "input"))
      (node (ref "U403") (pin "7") (pinfunction "A_7") (pintype "bidirectional"))
    )
    (net (code "47") (name "Net-(C116-Pad1)") (class "Default")
      (node (ref "C116") (pin "1") (pinfunction "1_1") (pintype "passive"))
      (node (ref "R118") (pin "1") (pinfunction "1_1") (pintype "passive"))
    )
    (net (code "48") (name "Net-(C207-Pad1)") (class "Default")
      (node (ref "C207") (pin "1") (pinfunction "1_1") (pintype "passive"))
      (node (ref "R203") (pin "2") (pinfunction "2_2") (pintype "passive"))
    )
    (net (code "49") (name "Net-(C209-Pad1)") (class "Default")
      (node (ref "C209") (pin "1") (pinfunction "1_1") (pintype "passive"))
      (node (ref "R204") (pin "2") (pinfunction "2_2") (pintype "passive"))
      (node (ref "R205") (pin "1") (pinfunction "1_1") (pintype "passive"))
    )
    (net (code "50") (name "Net-(C222-Pad1)") (class "Default")
      (node (ref "C222") (pin "1") (pinfunction "1_1") (pintype "passive"))
      (node (ref "R209") (pin "1") (pinfunction "1_1") (pintype "passive"))
    )
    (net (code "51") (name "Net-(C300-Pad1)") (class "Default")
      (node (ref "C300") (pin "1") (pinfunction "1_1") (pintype "passive"))
      (node (ref "C304") (pin "1") (pinfunction "1_1") (pintype "passive"))
      (node (ref "C308") (pin "1") (pinfunction "1_1") (pintype "passive"))
      (node (ref "F300") (pin "1") (pinfunction "1_1") (pintype "passive"))
      (node (ref "L300") (pin "2") (pinfunction "2_2") (pintype "passive"))
    )
    (net (code "52") (name "Net-(C302-Pad1)") (class "Default")
      (node (ref "C302") (pin "1") (pinfunction "1_1") (pintype "passive"))
      (node (ref "C306") (pin "1") (pinfunction "1_1") (pintype "passive"))
      (node (ref "C310") (pin "1") (pinfunction "1_1") (pintype "passive"))
      (node (ref "F301") (pin "1") (pinfunction "1_1") (pintype "passive"))
      (node (ref "L302") (pin "2") (pinfunction "2_2") (pintype "passive"))
    )
    (net (code "53") (name "Net-(C308-Pad2)") (class "Default")
      (node (ref "C308") (pin "2") (pinfunction "2_2") (pintype "passive"))
      (node (ref "R303") (pin "2") (pinfunction "2_2") (pintype "passive"))
    )
    (net (code "54") (name "Net-(C309-Pad1)") (class "Default")
      (node (ref "C309") (pin "1") (pinfunction "1_1") (pintype "passive"))
      (node (ref "R304") (pin "2") (pinfunction "2_2") (pintype "passive"))
    )
    (net (code "55") (name "Net-(C310-Pad2)") (class "Default")
      (node (ref "C310") (pin "2") (pinfunction "2_2") (pintype "passive"))
      (node (ref "R305") (pin "2") (pinfunction "2_2") (pintype "passive"))
    )
    (net (code "56") (name "Net-(C311-Pad1)") (class "Default")
      (node (ref "C311") (pin "1") (pinfunction "1_1") (pintype "passive"))
      (node (ref "R306") (pin "2") (pinfunction "2_2") (pintype "passive"))
    )
    (net (code "57") (name "Net-(C312-Pad2)") (class "Default")
      (node (ref "C312") (pin "2") (pinfunction "2_2") (pintype "passive"))
      (node (ref "L300") (pin "1") (pinfunction "1_1") (pintype "passive"))
      (node (ref "TP311") (pin "TP") (pinfunction "TP_TP") (pintype "input"))
      (node (ref "U301") (pin "39") (pinfunction "OUT_A_39") (pintype "bidirectional"))
      (node (ref "U301") (pin "40") (pinfunction "OUT_A_40") (pintype "bidirectional"))
    )
    (net (code "58") (name "Net-(C315-Pad1)") (class "Default")
      (node (ref "C315") (pin "1") (pinfunction "1_1") (pintype "passive"))
      (node (ref "L303") (pin "1") (pinfunction "1_1") (pintype "passive"))
      (node (ref "TP314") (pin "TP") (pinfunction "TP_TP") (pintype "input"))
      (node (ref "U301") (pin "27") (pinfunction "OUT_D_27") (pintype "bidirectional"))
      (node (ref "U301") (pin "28") (pinfunction "OUT_D_28") (pintype "bidirectional"))
    )
    (net (code "59") (name "Net-(C341-Pad2)") (class "Default")
      (node (ref "C341") (pin "2") (pinfunction "2_2") (pintype "passive"))
      (node (ref "R311") (pin "1") (pinfunction "1_1") (pintype "passive"))
    )
    (net (code "60") (name "Net-(C343-Pad2)") (class "Default")
      (node (ref "C343") (pin "2") (pinfunction "2_2") (pintype "passive"))
      (node (ref "R312") (pin "1") (pinfunction "1_1") (pintype "passive"))
    )
    (net (code "61") (name "Net-(C400-Pad1)") (class "Default")
      (node (ref "C400") (pin "1") (pinfunction "1_1") (pintype "passive"))
      (node (ref "R400") (pin "1") (pinfunction "1_1") (pintype "passive"))
      (node (ref "R401") (pin "1") (pinfunction "1_1") (pintype "passive"))
      (node (ref "SW409") (pin "2") (pinfunction "2_2") (pintype "passive"))
    )
    (net (code "62") (name "Net-(C406-Pad2)") (class "Default")
      (node (ref "C406") (pin "2") (pinfunction "2_2") (pintype "passive"))
      (node (ref "R406") (pin "1") (pinfunction "1_1") (pintype "passive"))
      (node (ref "Y400") (pin "1") (pinfunction "1_1") (pintype "passive"))
    )
    (net (code "63") (name "Net-(D100-A)") (class "Default")
      (node (ref "C126") (pin "1") (pinfunction "1_1") (pintype "passive"))
      (node (ref "C127") (pin "1") (pinfunction "1_1") (pintype "passive"))
      (node (ref "D100") (pin "2") (pinfunction "A_2") (pintype "passive"))
      (node (ref "F101") (pin "2") (pinfunction "2_2") (pintype "passive"))
      (node (ref "Q104") (pin "S") (pinfunction "S_S") (pintype "passive"))
      (node (ref "TP100") (pin "TP") (pinfunction "TP_TP") (pintype "input"))
      (node (ref "U102") (pin "3") (pinfunction "EN_3") (pintype "bidirectional"))
      (node (ref "U102") (pin "6") (pinfunction "ANODE_6") (pintype "bidirectional"))
    )
    (net (code "64") (name "Net-(D100-C)") (class "Default")
      (node (ref "C121") (pin "1") (pinfunction "1_1") (pintype "passive"))
      (node (ref "D100") (pin "1") (pinfunction "C_1") (pintype "passive"))
      (node (ref "U101") (pin "28") (pinfunction "DCIN_28") (pintype "bidirectional"))
    )
    (net (code "65") (name "Net-(D101-A)") (class "Default")
      (node (ref "C124") (pin "1") (pinfunction "1_1") (pintype "passive"))
      (node (ref "D101") (pin "2") (pinfunction "A_2") (pintype "passive"))
      (node (ref "U101") (pin "22") (pinfunction "VLO_22") (pintype "bidirectional"))
    )
    (net (code "66") (name "Net-(D101-C)") (class "Default")
      (node (ref "C110") (pin "1") (pinfunction "1_1") (pintype "passive"))
      (node (ref "D101") (pin "1") (pinfunction "C_1") (pintype "passive"))
      (node (ref "U101") (pin "23") (pinfunction "BST_23") (pintype "bidirectional"))
    )
    (net (code "67") (name "Net-(D103-C)") (class "Default")
      (node (ref "D103") (pin "K") (pinfunction "C_K") (pintype "passive"))
      (node (ref "F101") (pin "1") (pinfunction "1_1") (pintype "passive"))
      (node (ref "J100") (pin "1") (pinfunction "1_1") (pintype "passive"))
    )
    (net (code "68") (name "Net-(D200-A-PadA1)") (class "Default")
      (node (ref "D200") (pin "A1") (pinfunction "A_A1") (pintype "passive"))
      (node (ref "D200") (pin "A2") (pinfunction "A_A2") (pintype "passive"))
      (node (ref "L200") (pin "2") (pinfunction "2_2") (pintype "passive"))
      (node (ref "Q200") (pin "D") (pinfunction "D_D") (pintype "passive"))
      (node (ref "Q201") (pin "D") (pinfunction "D_D") (pintype "passive"))
    )
    (net (code "69") (name "Net-(D202-C)") (class "Default")
      (node (ref "D202") (pin "K") (pinfunction "C_K") (pintype "passive"))
      (node (ref "L202") (pin "1") (pinfunction "1_1") (pintype "passive"))
      (node (ref "Q203") (pin "3") (pinfunction "D_3") (pintype "passive"))
    )
    (net (code "70") (name "Net-(F100-Pad1)") (class "Default")
      (node (ref "F100") (pin "1") (pinfunction "1_1") (pintype "passive"))
      (node (ref "R100") (pin "1") (pinfunction "1_1") (pintype "passive"))
      (node (ref "XBT100") (pin "1") (pinfunction "+_1") (pintype "bidirectional"))
      (node (ref "XBT100") (pin "2") (pinfunction "+_2") (pintype "bidirectional"))
    )
    (net (code "71") (name "Net-(FAN300-+)") (class "Default")
      (node (ref "FAN300") (pin "1") (pinfunction "+_1") (pintype "bidirectional"))
      (node (ref "R302") (pin "2") (pinfunction "2_2") (pintype "passive"))
      (node (ref "TP320") (pin "TP") (pinfunction "TP_TP") (pintype "input"))
      (node (ref "U302") (pin "1") (pinfunction "OUT_1") (pintype "output"))
    )
    (net (code "72") (name "Net-(J401B-P$1)") (class "Default")
      (node (ref "J401") (pin "2") (pinfunction "P$1_2") (pintype "bidirectional"))
      (node (ref "Q401") (pin "3") (pinfunction "D_3") (pintype "passive"))
    )
    (net (code "73") (name "Net-(J401C-P$1)") (class "Default")
      (node (ref "J401") (pin "3") (pinfunction "P$1_3") (pintype "bidirectional"))
      (node (ref "Q402") (pin "3") (pinfunction "D_3") (pintype "passive"))
    )
    (net (code "74") (name "Net-(J401D-P$1)") (class "Default")
      (node (ref "J401") (pin "4") (pinfunction "P$1_4") (pintype "bidirectional"))
      (node (ref "Q403") (pin "3") (pinfunction "D_3") (pintype "passive"))
    )
    (net (code "75") (name "Net-(J402B-P$1)") (class "Default")
      (node (ref "J402") (pin "2") (pinfunction "P$1_2") (pintype "bidirectional"))
      (node (ref "Q404") (pin "3") (pinfunction "D_3") (pintype "passive"))
    )
    (net (code "76") (name "Net-(J402C-P$1)") (class "Default")
      (node (ref "J402") (pin "3") (pinfunction "P$1_3") (pintype "bidirectional"))
      (node (ref "Q405") (pin "3") (pinfunction "D_3") (pintype "passive"))
    )
    (net (code "77") (name "Net-(J405-D+)") (class "Default")
      (node (ref "J405") (pin "3") (pinfunction "D+_3") (pintype "passive"))
      (node (ref "U401") (pin "8") (pinfunction "USBDP_8") (pintype "input"))
    )
    (net (code "78") (name "Net-(J405-D-)") (class "Default")
      (node (ref "J405") (pin "2") (pinfunction "D-_2") (pintype "passive"))
      (node (ref "U401") (pin "9") (pinfunction "USBDM_9") (pintype "input"))
    )
    (net (code "79") (name "Net-(J405-VBUS)") (class "Default")
      (node (ref "J405") (pin "1") (pinfunction "VBUS_1") (pintype "passive"))
      (node (ref "SJ402") (pin "1") (pinfunction "1_1") (pintype "passive"))
    )
    (net (code "80") (name "Net-(J408D-P$1)") (class "Default")
      (node (ref "J408") (pin "4") (pinfunction "P$1_4") (pintype "bidirectional"))
      (node (ref "U400") (pin "73") (pinfunction "RC14_73") (pintype "bidirectional"))
    )
    (net (code "81") (name "Net-(L201-P2)") (class "Default")
      (node (ref "C224") (pin "2") (pinfunction "2_2") (pintype "passive"))
      (node (ref "L201") (pin "3") (pinfunction "P2_3") (pintype "passive"))
      (node (ref "Q202") (pin "MB") (pinfunction "D_MB") (pintype "passive"))
    )
    (net (code "82") (name "Net-(L201-S2)") (class "Default")
      (node (ref "C224") (pin "1") (pinfunction "1_1") (pintype "passive"))
      (node (ref "D201") (pin "A1") (pinfunction "A_A1") (pintype "passive"))
      (node (ref "D201") (pin "A2") (pinfunction "A_A2") (pintype "passive"))
      (node (ref "L201") (pin "4") (pinfunction "S2_4") (pintype "passive"))
    )
    (net (code "83") (name "Net-(Q100-PadD)") (class "Default")
      (node (ref "Q100") (pin "D") (pinfunction "D_D") (pintype "passive"))
      (node (ref "Q101") (pin "D") (pinfunction "D_D") (pintype "passive"))
    )
    (net (code "84") (name "Net-(Q100-PadG)") (class "Default")
      (node (ref "Q100") (pin "G") (pinfunction "G_G") (pintype "passive"))
      (node (ref "R108") (pin "1") (pinfunction "1_1") (pintype "passive"))
      (node (ref "R109") (pin "2") (pinfunction "2_2") (pintype "passive"))
    )
    (net (code "85") (name "Net-(Q100-PadS)") (class "Default")
      (node (ref "Q100") (pin "S") (pinfunction "S_S") (pintype "passive"))
      (node (ref "R105") (pin "2") (pinfunction "2_2") (pintype "passive"))
      (node (ref "R107") (pin "1") (pinfunction "1_1") (pintype "passive"))
      (node (ref "R109") (pin "1") (pinfunction "1_1") (pintype "passive"))
    )
    (net (code "86") (name "Net-(Q101-PadG)") (class "Default")
      (node (ref "Q101") (pin "G") (pinfunction "G_G") (pintype "passive"))
      (node (ref "R110") (pin "1") (pinfunction "1_1") (pintype "passive"))
      (node (ref "R111") (pin "2") (pinfunction "2_2") (pintype "passive"))
    )
    (net (code "87") (name "Net-(Q200-PadS)") (class "Default")
      (node (ref "Q200") (pin "S") (pinfunction "S_S") (pintype "passive"))
      (node (ref "Q201") (pin "S") (pinfunction "S_S") (pintype "passive"))
      (node (ref "R205") (pin "2") (pinfunction "2_2") (pintype "passive"))
      (node (ref "R206") (pin "2") (pinfunction "2_2") (pintype "passive"))
    )
    (net (code "88") (name "Net-(Q202-G)") (class "Default")
      (node (ref "Q202") (pin "4") (pinfunction "G_4") (pintype "passive"))
      (node (ref "U201") (pin "6") (pinfunction "DR_6") (pintype "bidirectional"))
    )
    (net (code "89") (name "Net-(Q202-S-Pad1)") (class "Default")
      (node (ref "Q202") (pin "1") (pinfunction "S_1") (pintype "passive"))
      (node (ref "Q202") (pin "2") (pinfunction "S_2") (pintype "passive"))
      (node (ref "Q202") (pin "3") (pinfunction "S_3") (pintype "passive"))
      (node (ref "R211") (pin "2") (pinfunction "2_2") (pintype "passive"))
      (node (ref "R212") (pin "2") (pinfunction "2_2") (pintype "passive"))
    )
    (net (code "90") (name "Net-(Q203-G)") (class "Default")
      (node (ref "Q203") (pin "1") (pinfunction "G_1") (pintype "passive"))
      (node (ref "U202") (pin "6") (pinfunction "PGATE_6") (pintype "bidirectional"))
    )
    (net (code "91") (name "Net-(Q203-S)") (class "Default")
      (node (ref "Q203") (pin "2") (pinfunction "S_2") (pintype "passive"))
      (node (ref "R217") (pin "1") (pinfunction "1_1") (pintype "passive"))
      (node (ref "U202") (pin "5") (pinfunction "ISEN_5") (pintype "bidirectional"))
    )
    (net (code "92") (name "Net-(Q400-D)") (class "Default")
      (node (ref "Q400") (pin "3") (pinfunction "D_3") (pintype "passive"))
      (node (ref "XDS400") (pin "16") (pinfunction "GND_BL_16") (pintype "bidirectional"))
      (node (ref "XDS400") (pin "18") (pinfunction "GND_BL_18") (pintype "bidirectional"))
    )
    (net (code "93") (name "Net-(Q400-G)") (class "Default")
      (node (ref "Q400") (pin "1") (pinfunction "G_1") (pintype "passive"))
      (node (ref "U400") (pin "1") (pinfunction "RG15_1") (pintype "bidirectional"))
    )
    (net (code "94") (name "Net-(Q401-G)") (class "Default")
      (node (ref "Q401") (pin "1") (pinfunction "G_1") (pintype "passive"))
      (node (ref "U400") (pin "18") (pinfunction "RE8_18") (pintype "bidirectional"))
    )
    (net (code "95") (name "Net-(Q402-G)") (class "Default")
      (node (ref "Q402") (pin "1") (pinfunction "G_1") (pintype "passive"))
      (node (ref "U400") (pin "19") (pinfunction "RE9_19") (pintype "bidirectional"))
    )
    (net (code "96") (name "Net-(Q403-G)") (class "Default")
      (node (ref "Q403") (pin "1") (pinfunction "G_1") (pintype "passive"))
      (node (ref "U400") (pin "20") (pinfunction "RB5_20") (pintype "bidirectional"))
    )
    (net (code "97") (name "Net-(Q404-G)") (class "Default")
      (node (ref "Q404") (pin "1") (pinfunction "G_1") (pintype "passive"))
      (node (ref "U400") (pin "22") (pinfunction "RB3_22") (pintype "bidirectional"))
    )
    (net (code "98") (name "Net-(Q405-G)") (class "Default")
      (node (ref "Q405") (pin "1") (pinfunction "G_1") (pintype "passive"))
      (node (ref "U400") (pin "23") (pinfunction "RB2_23") (pintype "bidirectional"))
    )
    (net (code "99") (name "Net-(Q406-G)") (class "Default")
      (node (ref "Q406") (pin "1") (pinfunction "G_1") (pintype "passive"))
      (node (ref "R402") (pin "2") (pinfunction "2_2") (pintype "passive"))
      (node (ref "SW408") (pin "1") (pinfunction "1_1") (pintype "passive"))
      (node (ref "U403") (pin "1") (pinfunction "S_1") (pintype "bidirectional"))
    )
    (net (code "100") (name "Net-(R116-Pad2)") (class "Default")
      (node (ref "R116") (pin "2") (pinfunction "2_2") (pintype "passive"))
      (node (ref "SW100") (pin "2") (pinfunction "2_2") (pintype "passive"))
    )
    (net (code "101") (name "Net-(R122-Pad1)") (class "Default")
      (node (ref "R122") (pin "1") (pinfunction "1_1") (pintype "passive"))
      (node (ref "R123") (pin "2") (pinfunction "2_2") (pintype "passive"))
    )
    (net (code "102") (name "Net-(RV200-S)") (class "Default")
      (node (ref "R208") (pin "1") (pinfunction "1_1") (pintype "passive"))
      (node (ref "RV200") (pin "2") (pinfunction "S_2") (pintype "passive"))
    )
    (net (code "103") (name "Net-(RV400-S)") (class "Default")
      (node (ref "RV400") (pin "2") (pinfunction "S_2") (pintype "passive"))
      (node (ref "U400") (pin "21") (pinfunction "RB4_21") (pintype "bidirectional"))
    )
    (net (code "104") (name "Net-(RV401-S)") (class "Default")
      (node (ref "RV401") (pin "2") (pinfunction "S_2") (pintype "passive"))
      (node (ref "XDS400") (pin "3") (pinfunction "NC1_3") (pintype "bidirectional"))
    )
    (net (code "105") (name "Net-(SJ401-Pad2)") (class "Default")
      (node (ref "SJ401") (pin "2") (pinfunction "2_2") (pintype "passive"))
      (node (ref "XDS400") (pin "15") (pinfunction "VBL_15") (pintype "power_in"))
      (node (ref "XDS400") (pin "17") (pinfunction "VBL_17") (pintype "power_in"))
    )
    (net (code "106") (name "Net-(SW407-O)") (class "Default")
      (node (ref "SW407") (pin "1") (pinfunction "O_1") (pintype "passive"))
      (node (ref "U400") (pin "16") (pinfunction "RG9_16") (pintype "bidirectional"))
    )
    (net (code "107") (name "Net-(SW407-S)") (class "Default")
      (node (ref "SW407") (pin "3") (pinfunction "S_3") (pintype "passive"))
      (node (ref "U400") (pin "17") (pinfunction "RA0_17") (pintype "bidirectional"))
    )
    (net (code "108") (name "Net-(U100-AVDD)") (class "Default")
      (node (ref "C109") (pin "1") (pinfunction "1_1") (pintype "passive"))
      (node (ref "U100") (pin "2") (pinfunction "AVDD_2") (pintype "bidirectional"))
      (node (ref "U100") (pin "20") (pinfunction "CCFG_20") (pintype "bidirectional"))
    )
    (net (code "109") (name "Net-(U100-CBI)") (class "Default")
      (node (ref "R115") (pin "1") (pinfunction "1_1") (pintype "passive"))
      (node (ref "U100") (pin "16") (pinfunction "CBI_16") (pintype "bidirectional"))
    )
    (net (code "110") (name "Net-(U100-CHG)") (class "Default")
      (node (ref "R110") (pin "2") (pinfunction "2_2") (pintype "passive"))
      (node (ref "R128") (pin "1") (pinfunction "1_1") (pintype "passive"))
      (node (ref "U100") (pin "13") (pinfunction "CHG_13") (pintype "bidirectional"))
    )
    (net (code "111") (name "Net-(U100-DSG)") (class "Default")
      (node (ref "R108") (pin "2") (pinfunction "2_2") (pintype "passive"))
      (node (ref "U100") (pin "12") (pinfunction "DSG_12") (pintype "bidirectional"))
    )
    (net (code "112") (name "Net-(U100-LD)") (class "Default")
      (node (ref "R112") (pin "2") (pinfunction "2_2") (pintype "passive"))
      (node (ref "U100") (pin "14") (pinfunction "LD_14") (pintype "bidirectional"))
    )
    (net (code "113") (name "Net-(U100-PRES)") (class "Default")
      (node (ref "R116") (pin "1") (pinfunction "1_1") (pintype "passive"))
      (node (ref "U100") (pin "22") (pinfunction "PRES_22") (pintype "bidirectional"))
    )
    (net (code "114") (name "Net-(U100-VC0)") (class "Default")
      (node (ref "C104") (pin "1") (pinfunction "1_1") (pintype "passive"))
      (node (ref "R104") (pin "2") (pinfunction "2_2") (pintype "passive"))
      (node (ref "U100") (pin "8") (pinfunction "VC0_8") (pintype "bidirectional"))
    )
    (net (code "115") (name "Net-(U100-VC1)") (class "Default")
      (node (ref "C102") (pin "2") (pinfunction "2_2") (pintype "passive"))
      (node (ref "C103") (pin "1") (pinfunction "1_1") (pintype "passive"))
      (node (ref "R103") (pin "2") (pinfunction "2_2") (pintype "passive"))
      (node (ref "U100") (pin "7") (pinfunction "VC1_7") (pintype "bidirectional"))
    )
    (net (code "116") (name "Net-(U100-VC2)") (class "Default")
      (node (ref "C101") (pin "2") (pinfunction "2_2") (pintype "passive"))
      (node (ref "C102") (pin "1") (pinfunction "1_1") (pintype "passive"))
      (node (ref "R102") (pin "2") (pinfunction "2_2") (pintype "passive"))
      (node (ref "U100") (pin "6") (pinfunction "VC2_6") (pintype "bidirectional"))
    )
    (net (code "117") (name "Net-(U100-VC3)") (class "Default")
      (node (ref "C100") (pin "2") (pinfunction "2_2") (pintype "passive"))
      (node (ref "C101") (pin "1") (pinfunction "1_1") (pintype "passive"))
      (node (ref "R101") (pin "2") (pinfunction "2_2") (pintype "passive"))
      (node (ref "U100") (pin "5") (pinfunction "VC3_5") (pintype "bidirectional"))
    )
    (net (code "118") (name "Net-(U100-VC4)") (class "Default")
      (node (ref "C100") (pin "1") (pinfunction "1_1") (pintype "passive"))
      (node (ref "R100") (pin "2") (pinfunction "2_2") (pintype "passive"))
      (node (ref "U100") (pin "3") (pinfunction "VC5_3") (pintype "bidirectional"))
      (node (ref "U100") (pin "4") (pinfunction "VC4_4") (pintype "bidirectional"))
    )
    (net (code "119") (name "Net-(U100-VDD)") (class "Default")
      (node (ref "C108") (pin "1") (pinfunction "1_1") (pintype "passive"))
      (node (ref "R113") (pin "1") (pinfunction "1_1") (pintype "passive"))
      (node (ref "SW100") (pin "1") (pinfunction "1_1") (pintype "passive"))
      (node (ref "U100") (pin "1") (pinfunction "VDD_1") (pintype "bidirectional"))
    )
    (net (code "120") (name "Net-(U100-VTB)") (class "Default")
      (node (ref "R114") (pin "1") (pinfunction "1_1") (pintype "passive"))
      (node (ref "U100") (pin "19") (pinfunction "VTB_19") (pintype "bidirectional"))
    )
    (net (code "121") (name "Net-(U101-CCI)") (class "Default")
      (node (ref "C113") (pin "1") (pinfunction "1_1") (pintype "passive"))
      (node (ref "U101") (pin "11") (pinfunction "CCI_11") (pintype "bidirectional"))
    )
    (net (code "122") (name "Net-(U101-CCS)") (class "Default")
      (node (ref "C114") (pin "1") (pinfunction "1_1") (pintype "passive"))
      (node (ref "U101") (pin "10") (pinfunction "CCS_10") (pintype "bidirectional"))
    )
    (net (code "123") (name "Net-(U101-CCV)") (class "Default")
      (node (ref "C115") (pin "1") (pinfunction "1_1") (pintype "passive"))
      (node (ref "R118") (pin "2") (pinfunction "2_2") (pintype "passive"))
      (node (ref "U101") (pin "9") (pinfunction "CCV_9") (pintype "bidirectional"))
    )
    (net (code "124") (name "Net-(U101-CS)") (class "Default")
      (node (ref "C125") (pin "1") (pinfunction "1_1") (pintype "passive"))
      (node (ref "L100") (pin "2") (pinfunction "2_2") (pintype "passive"))
      (node (ref "R127") (pin "1") (pinfunction "1_1") (pintype "passive"))
      (node (ref "U101") (pin "19") (pinfunction "CS_19") (pintype "bidirectional"))
    )
    (net (code "125") (name "Net-(U101-CSSN)") (class "Default")
      (node (ref "C123") (pin "1") (pinfunction "1_1") (pintype "passive"))
      (node (ref "C129") (pin "+") (pinfunction "+_+") (pintype "passive"))
      (node (ref "C131") (pin "1") (pinfunction "1_1") (pintype "passive"))
      (node (ref "C133") (pin "1") (pinfunction "1_1") (pintype "passive"))
      (node (ref "Q102") (pin "D") (pinfunction "D_D") (pintype "passive"))
      (node (ref "Q105") (pin "S") (pinfunction "S_S") (pintype "passive"))
      (node (ref "R117") (pin "1") (pinfunction "1_1") (pintype "passive"))
      (node (ref "U101") (pin "26") (pinfunction "CSSN_26") (pintype "bidirectional"))
      (node (ref "U103") (pin "3") (pinfunction "EN_3") (pintype "bidirectional"))
      (node (ref "U103") (pin "6") (pinfunction "ANODE_6") (pintype "bidirectional"))
    )
    (net (code "126") (name "Net-(U101-CSSP)") (class "Default")
      (node (ref "C122") (pin "1") (pinfunction "1_1") (pintype "passive"))
      (node (ref "C128") (pin "1") (pinfunction "1_1") (pintype "passive"))
      (node (ref "Q104") (pin "D") (pinfunction "D_D") (pintype "passive"))
      (node (ref "R117") (pin "2") (pinfunction "2_2") (pintype "passive"))
      (node (ref "U101") (pin "27") (pinfunction "CSSP_27") (pintype "bidirectional"))
      (node (ref "U102") (pin "4") (pinfunction "CATHODE_4") (pintype "bidirectional"))
    )
    (net (code "127") (name "Net-(U101-DHI)") (class "Default")
      (node (ref "Q102") (pin "G") (pinfunction "G_G") (pintype "passive"))
      (node (ref "U101") (pin "25") (pinfunction "DHI_25") (pintype "bidirectional"))
    )
    (net (code "128") (name "Net-(U101-DLO)") (class "Default")
      (node (ref "Q103") (pin "G") (pinfunction "G_G") (pintype "passive"))
      (node (ref "U101") (pin "21") (pinfunction "DLO_21") (pintype "bidirectional"))
    )
    (net (code "129") (name "Net-(U101-LX)") (class "Default")
      (node (ref "C110") (pin "2") (pinfunction "2_2") (pintype "passive"))
      (node (ref "L100") (pin "1") (pinfunction "1_1") (pintype "passive"))
      (node (ref "Q102") (pin "S") (pinfunction "S_S") (pintype "passive"))
      (node (ref "Q103") (pin "D") (pinfunction "D_D") (pintype "passive"))
      (node (ref "U101") (pin "24") (pinfunction "LX_24") (pintype "bidirectional"))
    )
    (net (code "130") (name "Net-(U101-THM)") (class "Default")
      (node (ref "R119") (pin "2") (pinfunction "2_2") (pintype "passive"))
      (node (ref "U101") (pin "4") (pinfunction "THM_4") (pintype "bidirectional"))
    )
    (net (code "131") (name "Net-(U101-TIMER1)") (class "Default")
      (node (ref "C112") (pin "1") (pinfunction "1_1") (pintype "passive"))
      (node (ref "U101") (pin "13") (pinfunction "TIMER1_13") (pintype "bidirectional"))
    )
    (net (code "132") (name "Net-(U101-TIMER2)") (class "Default")
      (node (ref "C111") (pin "1") (pinfunction "1_1") (pintype "passive"))
      (node (ref "U101") (pin "14") (pinfunction "TIMER2_14") (pintype "bidirectional"))
    )
    (net (code "133") (name "Net-(U102-GATE)") (class "Default")
      (node (ref "Q104") (pin "G") (pinfunction "G_G") (pintype "passive"))
      (node (ref "U102") (pin "5") (pinfunction "GATE_5") (pintype "bidirectional"))
    )
    (net (code "134") (name "Net-(U102-VCAP)") (class "Default")
      (node (ref "C126") (pin "2") (pinfunction "2_2") (pintype "passive"))
      (node (ref "U102") (pin "1") (pinfunction "VCAP_1") (pintype "bidirectional"))
    )
    (net (code "135") (name "Net-(U103-GATE)") (class "Default")
      (node (ref "Q105") (pin "G") (pinfunction "G_G") (pintype "passive"))
      (node (ref "U103") (pin "5") (pinfunction "GATE_5") (pintype "bidirectional"))
    )
    (net (code "136") (name "Net-(U103-VCAP)") (class "Default")
      (node (ref "C133") (pin "2") (pinfunction "2_2") (pintype "passive"))
      (node (ref "U103") (pin "1") (pinfunction "VCAP_1") (pintype "bidirectional"))
    )
    (net (code "137") (name "Net-(U104-GATE)") (class "Default")
      (node (ref "Q106") (pin "G") (pinfunction "G_G") (pintype "passive"))
      (node (ref "U104") (pin "5") (pinfunction "GATE_5") (pintype "bidirectional"))
    )
    (net (code "138") (name "Net-(U104-VCAP)") (class "Default")
      (node (ref "C136") (pin "2") (pinfunction "2_2") (pintype "passive"))
      (node (ref "U104") (pin "1") (pinfunction "VCAP_1") (pintype "bidirectional"))
    )
    (net (code "139") (name "Net-(U200-COMP)") (class "Default")
      (node (ref "C208") (pin "1") (pinfunction "1_1") (pintype "passive"))
      (node (ref "R203") (pin "1") (pinfunction "1_1") (pintype "passive"))
      (node (ref "U200") (pin "3") (pinfunction "COMP_3") (pintype "bidirectional"))
    )
    (net (code "140") (name "Net-(U200-CS)") (class "Default")
      (node (ref "R204") (pin "1") (pinfunction "1_1") (pintype "passive"))
      (node (ref "U200") (pin "8") (pinfunction "CS_8") (pintype "bidirectional"))
    )
    (net (code "141") (name "Net-(U200-FB)") (class "Default")
      (node (ref "C207") (pin "2") (pinfunction "2_2") (pintype "passive"))
      (node (ref "C208") (pin "2") (pinfunction "2_2") (pintype "passive"))
      (node (ref "R207") (pin "1") (pinfunction "1_1") (pintype "passive"))
      (node (ref "R208") (pin "2") (pinfunction "2_2") (pintype "passive"))
      (node (ref "U200") (pin "2") (pinfunction "FB_2") (pintype "bidirectional"))
    )
    (net (code "142") (name "Net-(U200-OUT)") (class "Default")
      (node (ref "Q200") (pin "G") (pinfunction "G_G") (pintype "passive"))
      (node (ref "Q201") (pin "G") (pinfunction "G_G") (pintype "passive"))
      (node (ref "U200") (pin "5") (pinfunction "OUT_5") (pintype "bidirectional"))
    )
    (net (code "143") (name "Net-(U200-RT{slash}SYNC)") (class "Default")
      (node (ref "R202") (pin "2") (pinfunction "2_2") (pintype "passive"))
      (node (ref "U200") (pin "9") (pinfunction "RT/SYNC_9") (pintype "bidirectional"))
    )
    (net (code "144") (name "Net-(U200-SS)") (class "Default")
      (node (ref "C205") (pin "1") (pinfunction "1_1") (pintype "passive"))
      (node (ref "U200") (pin "10") (pinfunction "SS_10") (pintype "bidirectional"))
    )
    (net (code "145") (name "Net-(U200-UVLO)") (class "Default")
      (node (ref "R200") (pin "1") (pinfunction "1_1") (pintype "passive"))
      (node (ref "R201") (pin "2") (pinfunction "2_2") (pintype "passive"))
      (node (ref "U200") (pin "7") (pinfunction "UVLO_7") (pintype "bidirectional"))
    )
    (net (code "146") (name "Net-(U200-VCC)") (class "Default")
      (node (ref "C206") (pin "1") (pinfunction "1_1") (pintype "passive"))
      (node (ref "U200") (pin "4") (pinfunction "VCC_4") (pintype "bidirectional"))
    )
    (net (code "147") (name "Net-(U201-COMP)") (class "Default")
      (node (ref "C221") (pin "1") (pinfunction "1_1") (pintype "passive"))
      (node (ref "R209") (pin "2") (pinfunction "2_2") (pintype "passive"))
      (node (ref "U201") (pin "2") (pinfunction "COMP_2") (pintype "bidirectional"))
    )
    (net (code "148") (name "Net-(U201-FA{slash}SD)") (class "Default")
      (node (ref "R210") (pin "1") (pinfunction "1_1") (pintype "passive"))
      (node (ref "U201") (pin "7") (pinfunction "FA/SD_7") (pintype "bidirectional"))
    )
    (net (code "149") (name "Net-(U201-FB)") (class "Default")
      (node (ref "R213") (pin "1") (pinfunction "1_1") (pintype "passive"))
      (node (ref "R214") (pin "2") (pinfunction "2_2") (pintype "passive"))
      (node (ref "U201") (pin "3") (pinfunction "FB_3") (pintype "bidirectional"))
    )
    (net (code "150") (name "Net-(U201-ISENSE)") (class "Default")
      (node (ref "C223") (pin "1") (pinfunction "1_1") (pintype "passive"))
      (node (ref "R211") (pin "1") (pinfunction "1_1") (pintype "passive"))
      (node (ref "U201") (pin "1") (pinfunction "ISENSE_1") (pintype "bidirectional"))
    )
    (net (code "151") (name "Net-(U202-ADJ)") (class "Default")
      (node (ref "C216") (pin "2") (pinfunction "2_2") (pintype "passive"))
      (node (ref "R216") (pin "1") (pinfunction "1_1") (pintype "passive"))
      (node (ref "U202") (pin "1") (pinfunction "ADJ_1") (pintype "bidirectional"))
    )
    (net (code "152") (name "Net-(U202-FB)") (class "Default")
      (node (ref "C217") (pin "2") (pinfunction "2_2") (pintype "passive"))
      (node (ref "R218") (pin "1") (pinfunction "1_1") (pintype "passive"))
      (node (ref "R219") (pin "2") (pinfunction "2_2") (pintype "passive"))
      (node (ref "U202") (pin "3") (pinfunction "FB_3") (pintype "bidirectional"))
    )
    (net (code "153") (name "Net-(U202-RT)") (class "Default")
      (node (ref "R215") (pin "1") (pinfunction "1_1") (pintype "passive"))
      (node (ref "U202") (pin "2") (pinfunction "RT_2") (pintype "bidirectional"))
    )
    (net (code "154") (name "Net-(U202-VCC)") (class "Default")
      (node (ref "C215") (pin "2") (pinfunction "2_2") (pintype "passive"))
      (node (ref "U202") (pin "7") (pinfunction "VCC_7") (pintype "bidirectional"))
    )
    (net (code "155") (name "Net-(U203-BOOT)") (class "Default")
      (node (ref "C227") (pin "1") (pinfunction "1_1") (pintype "passive"))
      (node (ref "U203") (pin "6") (pinfunction "BOOT_6") (pintype "bidirectional"))
    )
    (net (code "156") (name "Net-(U203-FB)") (class "Default")
      (node (ref "R220") (pin "1") (pinfunction "1_1") (pintype "passive"))
      (node (ref "R221") (pin "2") (pinfunction "2_2") (pintype "passive"))
      (node (ref "U203") (pin "4") (pinfunction "FB_4") (pintype "bidirectional"))
    )
    (net (code "157") (name "Net-(U203-SW)") (class "Default")
      (node (ref "C227") (pin "2") (pinfunction "2_2") (pintype "passive"))
      (node (ref "L203") (pin "1") (pinfunction "1_1") (pintype "passive"))
      (node (ref "U203") (pin "2") (pinfunction "SW_2") (pintype "bidirectional"))
    )
    (net (code "158") (name "Net-(U300-ASEL_EMO2)") (class "Default")
      (node (ref "R313") (pin "2") (pinfunction "2_2") (pintype "passive"))
      (node (ref "U300") (pin "10") (pinfunction "ASEL_EMO2_10") (pintype "bidirectional"))
    )
    (net (code "159") (name "Net-(U300-PLL_FLTM)") (class "Default")
      (node (ref "C342") (pin "1") (pinfunction "1_1") (pintype "passive"))
      (node (ref "C343") (pin "1") (pinfunction "1_1") (pintype "passive"))
      (node (ref "U300") (pin "6") (pinfunction "PLL_FLTM_6") (pintype "bidirectional"))
    )
    (net (code "160") (name "Net-(U300-PLL_FLTP)") (class "Default")
      (node (ref "C340") (pin "2") (pinfunction "2_2") (pintype "passive"))
      (node (ref "R311") (pin "2") (pinfunction "2_2") (pintype "passive"))
      (node (ref "U300") (pin "7") (pinfunction "PLL_FLTP_7") (pintype "bidirectional"))
    )
    (net (code "161") (name "Net-(U300-PWM_M_7)") (class "Default")
      (node (ref "U300") (pin "46") (pinfunction "PWM_M_7_46") (pintype "bidirectional"))
      (node (ref "U301") (pin "15") (pinfunction "INPUT_D_15") (pintype "bidirectional"))
    )
    (net (code "162") (name "Net-(U300-PWM_M_8)") (class "Default")
      (node (ref "U300") (pin "48") (pinfunction "PWM_M_8_48") (pintype "bidirectional"))
      (node (ref "U301") (pin "6") (pinfunction "INPUT_B_6") (pintype "bidirectional"))
    )
    (net (code "163") (name "Net-(U300-PWM_P_7)") (class "Default")
      (node (ref "U300") (pin "47") (pinfunction "PWM_P_7_47") (pintype "bidirectional"))
      (node (ref "U301") (pin "14") (pinfunction "INPUT_C_14") (pintype "bidirectional"))
    )
    (net (code "164") (name "Net-(U300-PWM_P_8)") (class "Default")
      (node (ref "U300") (pin "49") (pinfunction "PWM_P_8_49") (pintype "bidirectional"))
      (node (ref "U301") (pin "5") (pinfunction "INPUT_A_5") (pintype "bidirectional"))
    )
    (net (code "165") (name "Net-(U300-VR_ANA)") (class "Default")
      (node (ref "C340") (pin "1") (pinfunction "1_1") (pintype "passive"))
      (node (ref "C341") (pin "1") (pinfunction "1_1") (pintype "passive"))
      (node (ref "U300") (pin "8") (pinfunction "VR_ANA_8") (pintype "bidirectional"))
    )
    (net (code "166") (name "Net-(U300-VR_DIG)") (class "Default")
      (node (ref "C335") (pin "1") (pinfunction "1_1") (pintype "passive"))
      (node (ref "C336") (pin "1") (pinfunction "1_1") (pintype "passive"))
      (node (ref "U300") (pin "28") (pinfunction "VR_DIG_28") (pintype "bidirectional"))
    )
    (net (code "167") (name "Net-(U300-VR_PWM)") (class "Default")
      (node (ref "C337") (pin "1") (pinfunction "1_1") (pintype "passive"))
      (node (ref "U300") (pin "52") (pinfunction "VR_PWM_52") (pintype "bidirectional"))
    )
    (net (code "168") (name "Net-(U300-XTALI)") (class "Default")
      (node (ref "C338") (pin "2") (pinfunction "2_2") (pintype "passive"))
      (node (ref "R310") (pin "2") (pinfunction "2_2") (pintype "passive"))
      (node (ref "U300") (pin "11") (pinfunction "XTALI_11") (pintype "bidirectional"))
      (node (ref "Y300") (pin "2") (pinfunction "2_2") (pintype "passive"))
    )
    (net (code "169") (name "Net-(U300-XTALO)") (class "Default")
      (node (ref "C339") (pin "2") (pinfunction "2_2") (pintype "passive"))
      (node (ref "R310") (pin "1") (pinfunction "1_1") (pintype "passive"))
      (node (ref "U300") (pin "12") (pinfunction "XTALO_12") (pintype "bidirectional"))
      (node (ref "Y300") (pin "1") (pinfunction "1_1") (pintype "passive"))
    )
    (net (code "170") (name "Net-(U301-AVDD)") (class "Default")
      (node (ref "C327") (pin "1") (pinfunction "1_1") (pintype "passive"))
      (node (ref "U301") (pin "13") (pinfunction "AVDD_13") (pintype "bidirectional"))
    )
    (net (code "171") (name "Net-(U301-BST_A)") (class "Default")
      (node (ref "C312") (pin "1") (pinfunction "1_1") (pintype "passive"))
      (node (ref "U301") (pin "44") (pinfunction "BST_A_44") (pintype "bidirectional"))
    )
    (net (code "172") (name "Net-(U301-BST_B)") (class "Default")
      (node (ref "C313") (pin "1") (pinfunction "1_1") (pintype "passive"))
      (node (ref "U301") (pin "43") (pinfunction "BST_B_43") (pintype "bidirectional"))
    )
    (net (code "173") (name "Net-(U301-BST_C)") (class "Default")
      (node (ref "C314") (pin "2") (pinfunction "2_2") (pintype "passive"))
      (node (ref "U301") (pin "24") (pinfunction "BST_C_24") (pintype "bidirectional"))
    )
    (net (code "174") (name "Net-(U301-BST_D)") (class "Default")
      (node (ref "C315") (pin "2") (pinfunction "2_2") (pintype "passive"))
      (node (ref "U301") (pin "23") (pinfunction "BST_D_23") (pintype "bidirectional"))
    )
    (net (code "175") (name "Net-(U301-C_START)") (class "Default")
      (node (ref "C325") (pin "1") (pinfunction "1_1") (pintype "passive"))
      (node (ref "U301") (pin "7") (pinfunction "C_START_7") (pintype "bidirectional"))
    )
    (net (code "176") (name "Net-(U301-GVDD_AB)") (class "Default")
      (node (ref "C324") (pin "1") (pinfunction "1_1") (pintype "passive"))
      (node (ref "R307") (pin "2") (pinfunction "2_2") (pintype "passive"))
      (node (ref "U301") (pin "1") (pinfunction "GVDD_AB_1") (pintype "bidirectional"))
    )
    (net (code "177") (name "Net-(U301-GVDD_CD)") (class "Default")
      (node (ref "C328") (pin "1") (pinfunction "1_1") (pintype "passive"))
      (node (ref "R308") (pin "2") (pinfunction "2_2") (pintype "passive"))
      (node (ref "U301") (pin "22") (pinfunction "GVDD_CD_22") (pintype "bidirectional"))
    )
    (net (code "178") (name "Net-(U301-M2)") (class "Default")
      (node (ref "SJ301") (pin "2") (pinfunction "2_2") (pintype "passive"))
      (node (ref "U301") (pin "20") (pinfunction "M2_20") (pintype "bidirectional"))
    )
    (net (code "179") (name "Net-(U301-OC_ADJ)") (class "Default")
      (node (ref "R309") (pin "2") (pinfunction "2_2") (pintype "passive"))
      (node (ref "U301") (pin "3") (pinfunction "OC_ADJ_3") (pintype "bidirectional"))
    )
    (net (code "180") (name "Net-(U301-OUT_B)") (class "Default")
      (node (ref "C313") (pin "2") (pinfunction "2_2") (pintype "passive"))
      (node (ref "L301") (pin "1") (pinfunction "1_1") (pintype "passive"))
      (node (ref "TP312") (pin "TP") (pinfunction "TP_TP") (pintype "input"))
      (node (ref "U301") (pin "35") (pinfunction "OUT_B_35") (pintype "bidirectional"))
    )
    (net (code "181") (name "Net-(U301-OUT_C)") (class "Default")
      (node (ref "C314") (pin "1") (pinfunction "1_1") (pintype "passive"))
      (node (ref "L302") (pin "1") (pinfunction "1_1") (pintype "passive"))
      (node (ref "TP313") (pin "TP") (pinfunction "TP_TP") (pintype "input"))
      (node (ref "U301") (pin "32") (pinfunction "OUT_C_32") (pintype "bidirectional"))
    )
    (net (code "182") (name "Net-(U302-+IN)") (class "Default")
      (node (ref "R300") (pin "2") (pinfunction "2_2") (pintype "passive"))
      (node (ref "RT300") (pin "2") (pinfunction "2_2") (pintype "bidirectional"))
      (node (ref "TP319") (pin "TP") (pinfunction "TP_TP") (pintype "input"))
      (node (ref "U302") (pin "3") (pinfunction "+IN_3") (pintype "input"))
    )
    (net (code "183") (name "Net-(U302--IN)") (class "Default")
      (node (ref "R301") (pin "1") (pinfunction "1_1") (pintype "passive"))
      (node (ref "R302") (pin "1") (pinfunction "1_1") (pintype "passive"))
      (node (ref "U302") (pin "4") (pinfunction "-IN_4") (pintype "input"))
    )
    (net (code "184") (name "Net-(U400-RA5)") (class "Default")
      (node (ref "U400") (pin "2") (pinfunction "RA5_2") (pintype "bidirectional"))
      (node (ref "XDS400") (pin "10") (pinfunction "AUDIO_L_10") (pintype "bidirectional"))
    )
    (net (code "185") (name "Net-(U400-RB0)") (class "Default")
      (node (ref "J400") (pin "4") (pinfunction "4_4") (pintype "passive"))
      (node (ref "U400") (pin "25") (pinfunction "RB0_25") (pintype "bidirectional"))
    )
    (net (code "186") (name "Net-(U400-RB1)") (class "Default")
      (node (ref "J400") (pin "5") (pinfunction "5_5") (pintype "passive"))
      (node (ref "U400") (pin "24") (pinfunction "RB1_24") (pintype "bidirectional"))
    )
    (net (code "187") (name "Net-(U400-RB6)") (class "Default")
      (node (ref "C404") (pin "1") (pinfunction "1_1") (pintype "passive"))
      (node (ref "TP408") (pin "TP") (pinfunction "TP_TP") (pintype "input"))
      (node (ref "U400") (pin "26") (pinfunction "RB6_26") (pintype "bidirectional"))
      (node (ref "U404") (pin "6") (pinfunction "-IN_6") (pintype "input"))
      (node (ref "U404") (pin "7") (pinfunction "OUT_7") (pintype "output"))
    )
    (net (code "188") (name "Net-(U400-RB7)") (class "Default")
      (node (ref "C403") (pin "1") (pinfunction "1_1") (pintype "passive"))
      (node (ref "TP409") (pin "TP") (pinfunction "TP_TP") (pintype "input"))
      (node (ref "U400") (pin "27") (pinfunction "RB7_27") (pintype "bidirectional"))
      (node (ref "U404") (pin "1") (pinfunction "OUT_1") (pintype "output"))
      (node (ref "U404") (pin "2") (pinfunction "-IN_2") (pintype "input"))
    )
    (net (code "189") (name "Net-(U400-RC1)") (class "Default")
      (node (ref "U400") (pin "6") (pinfunction "RC1_6") (pintype "bidirectional"))
      (node (ref "XDS400") (pin "11") (pinfunction "GPIO0/IO2_11") (pintype "bidirectional"))
    )
    (net (code "190") (name "Net-(U400-RC2)") (class "Default")
      (node (ref "U400") (pin "7") (pinfunction "RC2_7") (pintype "bidirectional"))
      (node (ref "XDS400") (pin "7") (pinfunction "~{CS}_7") (pintype "bidirectional"))
    )
    (net (code "191") (name "Net-(U400-RC3)") (class "Default")
      (node (ref "U400") (pin "8") (pinfunction "RC3_8") (pintype "bidirectional"))
      (node (ref "XDS400") (pin "9") (pinfunction "~{PD}_9") (pintype "bidirectional"))
    )
    (net (code "192") (name "Net-(U400-RC4)") (class "Default")
      (node (ref "U400") (pin "9") (pinfunction "RC4_9") (pintype "bidirectional"))
      (node (ref "XDS400") (pin "8") (pinfunction "~{INT}_8") (pintype "bidirectional"))
    )
    (net (code "193") (name "Net-(U400-RC12)") (class "Default")
      (node (ref "C405") (pin "2") (pinfunction "2_2") (pintype "passive"))
      (node (ref "U400") (pin "49") (pinfunction "RC12_49") (pintype "bidirectional"))
      (node (ref "Y400") (pin "2") (pinfunction "2_2") (pintype "passive"))
    )
    (net (code "194") (name "Net-(U400-RC15)") (class "Default")
      (node (ref "R406") (pin "2") (pinfunction "2_2") (pintype "passive"))
      (node (ref "U400") (pin "50") (pinfunction "RC15_50") (pintype "bidirectional"))
    )
    (net (code "195") (name "Net-(U400-RD4)") (class "Default")
      (node (ref "U400") (pin "81") (pinfunction "RD4_81") (pintype "bidirectional"))
      (node (ref "U403") (pin "5") (pinfunction "B1_5") (pintype "bidirectional"))
    )
    (net (code "196") (name "Net-(U400-RD5)") (class "Default")
      (node (ref "U400") (pin "82") (pinfunction "RD5_82") (pintype "bidirectional"))
      (node (ref "U403") (pin "2") (pinfunction "B1_2") (pintype "bidirectional"))
    )
    (net (code "197") (name "Net-(U400-RE1)") (class "Default")
      (node (ref "SW400") (pin "1") (pinfunction "1_1") (pintype "passive"))
      (node (ref "U400") (pin "94") (pinfunction "RE1_94") (pintype "bidirectional"))
    )
    (net (code "198") (name "Net-(U400-RE2)") (class "Default")
      (node (ref "SW404") (pin "1") (pinfunction "1_1") (pintype "passive"))
      (node (ref "U400") (pin "98") (pinfunction "RE2_98") (pintype "bidirectional"))
    )
    (net (code "199") (name "Net-(U400-RE3)") (class "Default")
      (node (ref "SW405") (pin "1") (pinfunction "1_1") (pintype "passive"))
      (node (ref "U400") (pin "99") (pinfunction "RE3_99") (pintype "bidirectional"))
    )
    (net (code "200") (name "Net-(U400-RE4)") (class "Default")
      (node (ref "SW406") (pin "1") (pinfunction "1_1") (pintype "passive"))
      (node (ref "U400") (pin "100") (pinfunction "RE4_100") (pintype "bidirectional"))
    )
    (net (code "201") (name "Net-(U400-RE5)") (class "Default")
      (node (ref "U400") (pin "3") (pinfunction "RE5_3") (pintype "bidirectional"))
      (node (ref "XDS400") (pin "14") (pinfunction "GPIO3_14") (pintype "bidirectional"))
    )
    (net (code "202") (name "Net-(U400-RE6)") (class "Default")
      (node (ref "U400") (pin "4") (pinfunction "RE6_4") (pintype "bidirectional"))
      (node (ref "XDS400") (pin "13") (pinfunction "GPIO2_13") (pintype "bidirectional"))
    )
    (net (code "203") (name "Net-(U400-RE7)") (class "Default")
      (node (ref "U400") (pin "5") (pinfunction "RE7_5") (pintype "bidirectional"))
      (node (ref "XDS400") (pin "12") (pinfunction "GPIO1/IO3_12") (pintype "bidirectional"))
    )
    (net (code "204") (name "Net-(U400-RG6)") (class "Default")
      (node (ref "U400") (pin "10") (pinfunction "RG6_10") (pintype "bidirectional"))
      (node (ref "XDS400") (pin "4") (pinfunction "SCK_4") (pintype "bidirectional"))
    )
    (net (code "205") (name "Net-(U400-RG7)") (class "Default")
      (node (ref "U400") (pin "11") (pinfunction "RG7_11") (pintype "bidirectional"))
      (node (ref "XDS400") (pin "5") (pinfunction "MISO/IO1_5") (pintype "bidirectional"))
    )
    (net (code "206") (name "Net-(U400-RG8)") (class "Default")
      (node (ref "U400") (pin "12") (pinfunction "RG8_12") (pintype "bidirectional"))
      (node (ref "XDS400") (pin "6") (pinfunction "MOSI/IO0_6") (pintype "bidirectional"))
    )
    (net (code "207") (name "Net-(U400-RG12)") (class "Default")
      (node (ref "SW402") (pin "1") (pinfunction "1_1") (pintype "passive"))
      (node (ref "U400") (pin "96") (pinfunction "RG12_96") (pintype "bidirectional"))
    )
    (net (code "208") (name "Net-(U400-RG13)") (class "Default")
      (node (ref "SW403") (pin "1") (pinfunction "1_1") (pintype "passive"))
      (node (ref "U400") (pin "97") (pinfunction "RG13_97") (pintype "bidirectional"))
    )
    (net (code "209") (name "Net-(U400-RG14)") (class "Default")
      (node (ref "SW401") (pin "1") (pinfunction "1_1") (pintype "passive"))
      (node (ref "U400") (pin "95") (pinfunction "RG14_95") (pintype "bidirectional"))
    )
    (net (code "210") (name "Net-(U400-~{MCLR})") (class "Default")
      (node (ref "J400") (pin "1") (pinfunction "1_1") (pintype "passive"))
      (node (ref "R401") (pin "2") (pinfunction "2_2") (pintype "passive"))
      (node (ref "TP400") (pin "TP") (pinfunction "TP_TP") (pintype "input"))
      (node (ref "U400") (pin "15") (pinfunction "~{MCLR}_15") (pintype "bidirectional"))
    )
    (net (code "211") (name "Net-(U401-CBUS1)") (class "Default")
      (node (ref "SJ402") (pin "2") (pinfunction "2_2") (pintype "passive"))
      (node (ref "U401") (pin "14") (pinfunction "CBUS1_14") (pintype "bidirectional"))
    )
    (net (code "212") (name "Net-(U401-RXD)") (class "Default")
      (node (ref "U401") (pin "4") (pinfunction "RXD_4") (pintype "input"))
      (node (ref "U403") (pin "6") (pinfunction "B2_6") (pintype "bidirectional"))
    )
    (net (code "213") (name "Net-(U401-TXD)") (class "Default")
      (node (ref "U401") (pin "1") (pinfunction "TXD_1") (pintype "output"))
      (node (ref "U403") (pin "3") (pinfunction "B2_3") (pintype "bidirectional"))
    )
    (net (code "214") (name "Net-(U401-~{CTS})") (class "Default")
      (node (ref "R403") (pin "2") (pinfunction "2_2") (pintype "passive"))
      (node (ref "U401") (pin "6") (pinfunction "~{CTS}_6") (pintype "input"))
    )
    (net (code "215") (name "Net-(U402A-+IN)") (class "Default")
      (node (ref "R404") (pin "1") (pinfunction "1_1") (pintype "passive"))
      (node (ref "R405") (pin "2") (pinfunction "2_2") (pintype "passive"))
      (node (ref "U402") (pin "3") (pinfunction "+IN_3") (pintype "input"))
    )
    (net (code "216") (name "Net-(U402A--IN)") (class "Default")
      (node (ref "R411") (pin "1") (pinfunction "1_1") (pintype "passive"))
      (node (ref "U402") (pin "1") (pinfunction "OUT_1") (pintype "output"))
      (node (ref "U402") (pin "2") (pinfunction "-IN_2") (pintype "input"))
    )
    (net (code "217") (name "Net-(U402B-+IN)") (class "Default")
      (node (ref "R409") (pin "1") (pinfunction "1_1") (pintype "passive"))
      (node (ref "R410") (pin "2") (pinfunction "2_2") (pintype "passive"))
      (node (ref "U402") (pin "5") (pinfunction "+IN_5") (pintype "input"))
    )
    (net (code "218") (name "Net-(U402B--IN)") (class "Default")
      (node (ref "R407") (pin "2") (pinfunction "2_2") (pintype "passive"))
      (node (ref "R408") (pin "1") (pinfunction "1_1") (pintype "passive"))
      (node (ref "U402") (pin "6") (pinfunction "-IN_6") (pintype "input"))
    )
    (net (code "219") (name "Net-(U402B-OUT)") (class "Default")
      (node (ref "R407") (pin "1") (pinfunction "1_1") (pintype "passive"))
      (node (ref "R412") (pin "2") (pinfunction "2_2") (pintype "passive"))
      (node (ref "U402") (pin "7") (pinfunction "OUT_7") (pintype "output"))
    )
    (net (code "220") (name "Net-(U404A-+IN)") (class "Default")
      (node (ref "R412") (pin "1") (pinfunction "1_1") (pintype "passive"))
      (node (ref "U404") (pin "3") (pinfunction "+IN_3") (pintype "input"))
    )
    (net (code "221") (name "Net-(U404B-+IN)") (class "Default")
      (node (ref "R411") (pin "2") (pinfunction "2_2") (pintype "passive"))
      (node (ref "U404") (pin "5") (pinfunction "+IN_5") (pintype "input"))
    )
    (net (code "222") (name "Net-(XBT100-BAL1)") (class "Default")
      (node (ref "R103") (pin "1") (pinfunction "1_1") (pintype "passive"))
      (node (ref "XBT100") (pin "4") (pinfunction "BAL1_4") (pintype "bidirectional"))
    )
    (net (code "223") (name "Net-(XBT100-BAL2)") (class "Default")
      (node (ref "R102") (pin "1") (pinfunction "1_1") (pintype "passive"))
      (node (ref "XBT100") (pin "3") (pinfunction "BAL2_3") (pintype "bidirectional"))
    )
    (net (code "224") (name "Net-(XBT100-BAL3)") (class "Default")
      (node (ref "R101") (pin "1") (pinfunction "1_1") (pintype "passive"))
      (node (ref "XBT100") (pin "7") (pinfunction "BAL3_7") (pintype "bidirectional"))
    )
    (net (code "225") (name "Net-(XLS300-+)") (class "Default")
      (node (ref "F300") (pin "2") (pinfunction "2_2") (pintype "passive"))
      (node (ref "TP315") (pin "TP") (pinfunction "TP_TP") (pintype "input"))
      (node (ref "XLS300") (pin "2") (pinfunction "+_2") (pintype "passive"))
    )
    (net (code "226") (name "Net-(XLS300--)") (class "Default")
      (node (ref "C301") (pin "1") (pinfunction "1_1") (pintype "passive"))
      (node (ref "C305") (pin "2") (pinfunction "2_2") (pintype "passive"))
      (node (ref "C309") (pin "2") (pinfunction "2_2") (pintype "passive"))
      (node (ref "L301") (pin "2") (pinfunction "2_2") (pintype "passive"))
      (node (ref "TP316") (pin "TP") (pinfunction "TP_TP") (pintype "input"))
      (node (ref "XLS300") (pin "1") (pinfunction "-_1") (pintype "passive"))
    )
    (net (code "227") (name "Net-(XLS301-+)") (class "Default")
      (node (ref "F301") (pin "2") (pinfunction "2_2") (pintype "passive"))
      (node (ref "TP317") (pin "TP") (pinfunction "TP_TP") (pintype "input"))
      (node (ref "XLS301") (pin "2") (pinfunction "+_2") (pintype "passive"))
    )
    (net (code "228") (name "Net-(XLS301--)") (class "Default")
      (node (ref "SJ300") (pin "2") (pinfunction "2_2") (pintype "passive"))
      (node (ref "XLS301") (pin "1") (pinfunction "-_1") (pintype "passive"))
      (node (ref "XLS302") (pin "2") (pinfunction "+_2") (pintype "passive"))
    )
    (net (code "229") (name "Net-(XLS302--)") (class "Default")
      (node (ref "C303") (pin "1") (pinfunction "1_1") (pintype "passive"))
      (node (ref "C307") (pin "2") (pinfunction "2_2") (pintype "passive"))
      (node (ref "C311") (pin "2") (pinfunction "2_2") (pintype "passive"))
      (node (ref "L303") (pin "2") (pinfunction "2_2") (pintype "passive"))
      (node (ref "SJ300") (pin "1") (pinfunction "1_1") (pintype "passive"))
      (node (ref "TP318") (pin "TP") (pinfunction "TP_TP") (pintype "input"))
      (node (ref "XLS302") (pin "1") (pinfunction "-_1") (pintype "passive"))
    )
    (net (code "230") (name "VBAT") (class "Default")
      (node (ref "C117") (pin "1") (pinfunction "1_1") (pintype "passive"))
      (node (ref "C130") (pin "+") (pinfunction "+_+") (pintype "passive"))
      (node (ref "C134") (pin "1") (pinfunction "1_1") (pintype "passive"))
      (node (ref "C136") (pin "1") (pinfunction "1_1") (pintype "passive"))
      (node (ref "F100") (pin "2") (pinfunction "2_2") (pintype "passive"))
      (node (ref "Q106") (pin "S") (pinfunction "S_S") (pintype "passive"))
      (node (ref "R113") (pin "2") (pinfunction "2_2") (pintype "passive"))
      (node (ref "R127") (pin "2") (pinfunction "2_2") (pintype "passive"))
      (node (ref "R404") (pin "2") (pinfunction "2_2") (pintype "passive"))
      (node (ref "TP101") (pin "TP") (pinfunction "TP_TP") (pintype "input"))
      (node (ref "U101") (pin "7") (pinfunction "BATT_7") (pintype "bidirectional"))
      (node (ref "U104") (pin "3") (pinfunction "EN_3") (pintype "bidirectional"))
      (node (ref "U104") (pin "6") (pinfunction "ANODE_6") (pintype "bidirectional"))
    )
    (net (code "231") (name "VSUP") (class "Default")
      (node (ref "C132") (pin "1") (pinfunction "1_1") (pintype "passive"))
      (node (ref "C135") (pin "1") (pinfunction "1_1") (pintype "passive"))
      (node (ref "C200") (pin "+") (pinfunction "+_+") (pintype "passive"))
      (node (ref "C204") (pin "1") (pinfunction "1_1") (pintype "passive"))
      (node (ref "C214") (pin "1") (pinfunction "1_1") (pintype "passive"))
      (node (ref "C215") (pin "1") (pinfunction "1_1") (pintype "passive"))
      (node (ref "C216") (pin "1") (pinfunction "1_1") (pintype "passive"))
      (node (ref "C219") (pin "1") (pinfunction "1_1") (pintype "passive"))
      (node (ref "C220") (pin "1") (pinfunction "1_1") (pintype "passive"))
      (node (ref "C225") (pin "1") (pinfunction "1_1") (pintype "passive"))
      (node (ref "C226") (pin "1") (pinfunction "1_1") (pintype "passive"))
      (node (ref "L200") (pin "1") (pinfunction "1_1") (pintype "passive"))
      (node (ref "L201") (pin "1") (pinfunction "P1_1") (pintype "passive"))
      (node (ref "Q105") (pin "D") (pinfunction "D_D") (pintype "passive"))
      (node (ref "Q106") (pin "D") (pinfunction "D_D") (pintype "passive"))
      (node (ref "R200") (pin "2") (pinfunction "2_2") (pintype "passive"))
      (node (ref "R215") (pin "2") (pinfunction "2_2") (pintype "passive"))
      (node (ref "R216") (pin "2") (pinfunction "2_2") (pintype "passive"))
      (node (ref "R217") (pin "2") (pinfunction "2_2") (pintype "passive"))
      (node (ref "TP102") (pin "TP") (pinfunction "TP_TP") (pintype "input"))
      (node (ref "U103") (pin "4") (pinfunction "CATHODE_4") (pintype "bidirectional"))
      (node (ref "U104") (pin "4") (pinfunction "CATHODE_4") (pintype "bidirectional"))
      (node (ref "U200") (pin "1") (pinfunction "VIN_1") (pintype "bidirectional"))
      (node (ref "U201") (pin "8") (pinfunction "VIN_8") (pintype "bidirectional"))
      (node (ref "U202") (pin "8") (pinfunction "VIN_8") (pintype "bidirectional"))
      (node (ref "U203") (pin "3") (pinfunction "VIN_3") (pintype "bidirectional"))
    )
    (net (code "232") (name "unconnected-(A400-AOHPL-Pad8)") (class "Default")
      (node (ref "A400") (pin "8") (pinfunction "AOHPL_8") (pintype "bidirectional"))
    )
    (net (code "233") (name "unconnected-(A400-AOHPM-Pad7)") (class "Default")
      (node (ref "A400") (pin "7") (pinfunction "AOHPM_7") (pintype "bidirectional"))
    )
    (net (code "234") (name "unconnected-(A400-AOHPR-Pad6)") (class "Default")
      (node (ref "A400") (pin "6") (pinfunction "AOHPR_6") (pintype "bidirectional"))
    )
    (net (code "235") (name "unconnected-(A400-DMIC1_L-Pad19)") (class "Default")
      (node (ref "A400") (pin "19") (pinfunction "DMIC1_L_19") (pintype "bidirectional"))
    )
    (net (code "236") (name "unconnected-(A400-DMIC1_R-Pad18)") (class "Default")
      (node (ref "A400") (pin "18") (pinfunction "DMIC1_R_18") (pintype "bidirectional"))
    )
    (net (code "237") (name "unconnected-(A400-DMIC_CLK-Pad17)") (class "Default")
      (node (ref "A400") (pin "17") (pinfunction "DMIC_CLK_17") (pintype "bidirectional"))
    )
    (net (code "238") (name "unconnected-(A400-DR1-Pad1)") (class "Default")
      (node (ref "A400") (pin "1") (pinfunction "DR1_1") (pintype "bidirectional"))
    )
    (net (code "239") (name "unconnected-(A400-LED1-Pad32)") (class "Default")
      (node (ref "A400") (pin "32") (pinfunction "LED1_32") (pintype "bidirectional"))
    )
    (net (code "240") (name "unconnected-(A400-LED2-Pad34)") (class "Default")
      (node (ref "A400") (pin "34") (pinfunction "LED2_34") (pintype "bidirectional"))
    )
    (net (code "241") (name "unconnected-(A400-MCLK1-Pad5)") (class "Default")
      (node (ref "A400") (pin "5") (pinfunction "MCLK1_5") (pintype "bidirectional"))
    )
    (net (code "242") (name "unconnected-(A400-MICBIAS-Pad15)") (class "Default")
      (node (ref "A400") (pin "15") (pinfunction "MICBIAS_15") (pintype "bidirectional"))
    )
    (net (code "243") (name "unconnected-(A400-MICN1-Pad13)") (class "Default")
      (node (ref "A400") (pin "13") (pinfunction "MICN1_13") (pintype "bidirectional"))
    )
    (net (code "244") (name "unconnected-(A400-MICN2-Pad9)") (class "Default")
      (node (ref "A400") (pin "9") (pinfunction "MICN2_9") (pintype "bidirectional"))
    )
    (net (code "245") (name "unconnected-(A400-MICP1-Pad14)") (class "Default")
      (node (ref "A400") (pin "14") (pinfunction "MICP1_14") (pintype "bidirectional"))
    )
    (net (code "246") (name "unconnected-(A400-MICP2-Pad10)") (class "Default")
      (node (ref "A400") (pin "10") (pinfunction "MICP2_10") (pintype "bidirectional"))
    )
    (net (code "247") (name "unconnected-(A400-P0_0{slash}UART_TX_IND-Pad49)") (class "Default")
      (node (ref "A400") (pin "49") (pinfunction "P0_0/UART_TX_IND_49") (pintype "bidirectional"))
    )
    (net (code "248") (name "unconnected-(A400-P0_1-Pad44)") (class "Default")
      (node (ref "A400") (pin "44") (pinfunction "P0_1_44") (pintype "bidirectional"))
    )
    (net (code "249") (name "unconnected-(A400-P0_2-Pad33)") (class "Default")
      (node (ref "A400") (pin "33") (pinfunction "P0_2_33") (pintype "bidirectional"))
    )
    (net (code "250") (name "unconnected-(A400-P0_3-Pad38)") (class "Default")
      (node (ref "A400") (pin "38") (pinfunction "P0_3_38") (pintype "bidirectional"))
    )
    (net (code "251") (name "unconnected-(A400-P0_5-Pad40)") (class "Default")
      (node (ref "A400") (pin "40") (pinfunction "P0_5_40") (pintype "bidirectional"))
    )
    (net (code "252") (name "unconnected-(A400-P0_6-Pad35)") (class "Default")
      (node (ref "A400") (pin "35") (pinfunction "P0_6_35") (pintype "bidirectional"))
    )
    (net (code "253") (name "unconnected-(A400-P0_7-Pad45)") (class "Default")
      (node (ref "A400") (pin "45") (pinfunction "P0_7_45") (pintype "bidirectional"))
    )
    (net (code "254") (name "unconnected-(A400-P1_2{slash}TDI_CPU{slash}SCL-Pad46)") (class "Default")
      (node (ref "A400") (pin "46") (pinfunction "P1_2/TDI_CPU/SCL_46") (pintype "bidirectional"))
    )
    (net (code "255") (name "unconnected-(A400-P1_3{slash}TCK_CPU{slash}SDA-Pad47)") (class "Default")
      (node (ref "A400") (pin "47") (pinfunction "P1_3/TCK_CPU/SDA_47") (pintype "bidirectional"))
    )
    (net (code "256") (name "unconnected-(A400-P1_6{slash}PWM1-Pad41)") (class "Default")
      (node (ref "A400") (pin "41") (pinfunction "P1_6/PWM1_41") (pintype "bidirectional"))
    )
    (net (code "257") (name "unconnected-(A400-P2_3-Pad42)") (class "Default")
      (node (ref "A400") (pin "42") (pinfunction "P2_3_42") (pintype "bidirectional"))
    )
    (net (code "258") (name "unconnected-(A400-P2_6-Pad21)") (class "Default")
      (node (ref "A400") (pin "21") (pinfunction "P2_6_21") (pintype "bidirectional"))
    )
    (net (code "259") (name "unconnected-(A400-P2_7-Pad39)") (class "Default")
      (node (ref "A400") (pin "39") (pinfunction "P2_7_39") (pintype "bidirectional"))
    )
    (net (code "260") (name "unconnected-(A400-P3_2-Pad20)") (class "Default")
      (node (ref "A400") (pin "20") (pinfunction "P3_2_20") (pintype "bidirectional"))
    )
    (net (code "261") (name "unconnected-(A400-P3_7{slash}UART_CTS-Pad48)") (class "Default")
      (node (ref "A400") (pin "48") (pinfunction "P3_7/UART_CTS_48") (pintype "bidirectional"))
    )
    (net (code "262") (name "unconnected-(A400-SK2_KEY_AD-Pad28)") (class "Default")
      (node (ref "A400") (pin "28") (pinfunction "SK2_KEY_AD_28") (pintype "bidirectional"))
    )
    (net (code "263") (name "unconnected-(A400-SKI1_AMB_DET-Pad27)") (class "Default")
      (node (ref "A400") (pin "27") (pinfunction "SKI1_AMB_DET_27") (pintype "bidirectional"))
    )
    (net (code "264") (name "unconnected-(A400-SYS_PWR-Pad24)") (class "Default")
      (node (ref "A400") (pin "24") (pinfunction "SYS_PWR_24") (pintype "bidirectional"))
    )
    (net (code "265") (name "unconnected-(A400-VDD_IO-Pad25)") (class "Default")
      (node (ref "A400") (pin "25") (pinfunction "VDD_IO_25") (pintype "bidirectional"))
    )
    (net (code "266") (name "unconnected-(J405-ID-Pad4)") (class "Default")
      (node (ref "J405") (pin "4") (pinfunction "ID_4") (pintype "passive"))
    )
    (net (code "267") (name "unconnected-(J406-ID-Pad4)") (class "Default")
      (node (ref "J406") (pin "4") (pinfunction "ID_4") (pintype "passive"))
    )
    (net (code "268") (name "unconnected-(RV200-A-Pad1)") (class "Default")
      (node (ref "RV200") (pin "1") (pinfunction "A_1") (pintype "passive"))
    )
    (net (code "269") (name "unconnected-(U100-CBO-Pad21)") (class "Default")
      (node (ref "U100") (pin "21") (pinfunction "CBO_21") (pintype "bidirectional"))
    )
    (net (code "270") (name "unconnected-(U100-LPWR-Pad15)") (class "Default")
      (node (ref "U100") (pin "15") (pinfunction "LPWR_15") (pintype "bidirectional"))
    )
    (net (code "271") (name "unconnected-(U100-OCDP-Pad17)") (class "Default")
      (node (ref "U100") (pin "17") (pinfunction "OCDP_17") (pintype "bidirectional"))
    )
    (net (code "272") (name "unconnected-(U203-EN-Pad5)") (class "Default")
      (node (ref "U203") (pin "5") (pinfunction "EN_5") (pintype "bidirectional"))
    )
    (net (code "273") (name "unconnected-(U300-LRCLKO(LRCLK#2)-Pad31)") (class "Default")
      (node (ref "U300") (pin "31") (pinfunction "LRCLKO(LRCLK#2)_31") (pintype "bidirectional"))
    )
    (net (code "274") (name "unconnected-(U300-PSVC{slash}MCLK-Pad33)") (class "Default")
      (node (ref "U300") (pin "33") (pinfunction "PSVC/MCLK_33") (pintype "bidirectional"))
    )
    (net (code "275") (name "unconnected-(U300-PWM_HPM_L-Pad1)") (class "Default")
      (node (ref "U300") (pin "1") (pinfunction "PWM_HPM_L_1") (pintype "bidirectional"))
    )
    (net (code "276") (name "unconnected-(U300-PWM_HPM_R-Pad3)") (class "Default")
      (node (ref "U300") (pin "3") (pinfunction "PWM_HPM_R_3") (pintype "bidirectional"))
    )
    (net (code "277") (name "unconnected-(U300-PWM_HPP_L-Pad2)") (class "Default")
      (node (ref "U300") (pin "2") (pinfunction "PWM_HPP_L_2") (pintype "bidirectional"))
    )
    (net (code "278") (name "unconnected-(U300-PWM_HPP_R-Pad4)") (class "Default")
      (node (ref "U300") (pin "4") (pinfunction "PWM_HPP_R_4") (pintype "bidirectional"))
    )
    (net (code "279") (name "unconnected-(U300-PWM_M_1-Pad38)") (class "Default")
      (node (ref "U300") (pin "38") (pinfunction "PWM_M_1_38") (pintype "bidirectional"))
    )
    (net (code "280") (name "unconnected-(U300-PWM_M_2-Pad40)") (class "Default")
      (node (ref "U300") (pin "40") (pinfunction "PWM_M_2_40") (pintype "bidirectional"))
    )
    (net (code "281") (name "unconnected-(U300-PWM_M_3-Pad42)") (class "Default")
      (node (ref "U300") (pin "42") (pinfunction "PWM_M_3_42") (pintype "bidirectional"))
    )
    (net (code "282") (name "unconnected-(U300-PWM_M_4-Pad44)") (class "Default")
      (node (ref "U300") (pin "44") (pinfunction "PWM_M_4_44") (pintype "bidirectional"))
    )
    (net (code "283") (name "unconnected-(U300-PWM_M_5-Pad53)") (class "Default")
      (node (ref "U300") (pin "53") (pinfunction "PWM_M_5_53") (pintype "bidirectional"))
    )
    (net (code "284") (name "unconnected-(U300-PWM_M_6-Pad55)") (class "Default")
      (node (ref "U300") (pin "55") (pinfunction "PWM_M_6_55") (pintype "bidirectional"))
    )
    (net (code "285") (name "unconnected-(U300-PWM_P_1-Pad39)") (class "Default")
      (node (ref "U300") (pin "39") (pinfunction "PWM_P_1_39") (pintype "bidirectional"))
    )
    (net (code "286") (name "unconnected-(U300-PWM_P_2-Pad41)") (class "Default")
      (node (ref "U300") (pin "41") (pinfunction "PWM_P_2_41") (pintype "bidirectional"))
    )
    (net (code "287") (name "unconnected-(U300-PWM_P_3-Pad43)") (class "Default")
      (node (ref "U300") (pin "43") (pinfunction "PWM_P_3_43") (pintype "bidirectional"))
    )
    (net (code "288") (name "unconnected-(U300-PWM_P_4-Pad45)") (class "Default")
      (node (ref "U300") (pin "45") (pinfunction "PWM_P_4_45") (pintype "bidirectional"))
    )
    (net (code "289") (name "unconnected-(U300-PWM_P_5-Pad54)") (class "Default")
      (node (ref "U300") (pin "54") (pinfunction "PWM_P_5_54") (pintype "bidirectional"))
    )
    (net (code "290") (name "unconnected-(U300-PWM_P_6-Pad56)") (class "Default")
      (node (ref "U300") (pin "56") (pinfunction "PWM_P_6_56") (pintype "bidirectional"))
    )
    (net (code "291") (name "unconnected-(U300-SCLKO(SCLK#2)-Pad30)") (class "Default")
      (node (ref "U300") (pin "30") (pinfunction "SCLKO(SCLK#2)_30") (pintype "bidirectional"))
    )
    (net (code "292") (name "unconnected-(U300-SDIN2-Pad25)") (class "Default")
      (node (ref "U300") (pin "25") (pinfunction "SDIN2_25") (pintype "bidirectional"))
    )
    (net (code "293") (name "unconnected-(U300-SDIN2_1(SDIN3)-Pad26)") (class "Default")
      (node (ref "U300") (pin "26") (pinfunction "SDIN2_1(SDIN3)_26") (pintype "bidirectional"))
    )
    (net (code "294") (name "unconnected-(U300-SDIN2_2(SDIN4)-Pad27)") (class "Default")
      (node (ref "U300") (pin "27") (pinfunction "SDIN2_2(SDIN4)_27") (pintype "bidirectional"))
    )
    (net (code "295") (name "unconnected-(U300-SDOUT(SDIN5)-Pad29)") (class "Default")
      (node (ref "U300") (pin "29") (pinfunction "SDOUT(SDIN5)_29") (pintype "bidirectional"))
    )
    (net (code "296") (name "unconnected-(U400-D+-Pad55)") (class "Default")
      (node (ref "U400") (pin "55") (pinfunction "D+_55") (pintype "bidirectional"))
    )
    (net (code "297") (name "unconnected-(U400-D--Pad54)") (class "Default")
      (node (ref "U400") (pin "54") (pinfunction "D-_54") (pintype "bidirectional"))
    )
    (net (code "298") (name "unconnected-(U400-RA1-Pad38)") (class "Default")
      (node (ref "U400") (pin "38") (pinfunction "RA1_38") (pintype "bidirectional"))
    )
    (net (code "299") (name "unconnected-(U400-RA6-Pad89)") (class "Default")
      (node (ref "U400") (pin "89") (pinfunction "RA6_89") (pintype "bidirectional"))
    )
    (net (code "300") (name "unconnected-(U400-RA7-Pad90)") (class "Default")
      (node (ref "U400") (pin "90") (pinfunction "RA7_90") (pintype "bidirectional"))
    )
    (net (code "301") (name "unconnected-(U400-RA9-Pad28)") (class "Default")
      (node (ref "U400") (pin "28") (pinfunction "RA9_28") (pintype "bidirectional"))
    )
    (net (code "302") (name "unconnected-(U400-RA10-Pad29)") (class "Default")
      (node (ref "U400") (pin "29") (pinfunction "RA10_29") (pintype "bidirectional"))
    )
    (net (code "303") (name "unconnected-(U400-RB11-Pad35)") (class "Default")
      (node (ref "U400") (pin "35") (pinfunction "RB11_35") (pintype "bidirectional"))
    )
    (net (code "304") (name "unconnected-(U400-RB12-Pad41)") (class "Default")
      (node (ref "U400") (pin "41") (pinfunction "RB12_41") (pintype "bidirectional"))
    )
    (net (code "305") (name "unconnected-(U400-RB13-Pad42)") (class "Default")
      (node (ref "U400") (pin "42") (pinfunction "RB13_42") (pintype "bidirectional"))
    )
    (net (code "306") (name "unconnected-(U400-RB14-Pad43)") (class "Default")
      (node (ref "U400") (pin "43") (pinfunction "RB14_43") (pintype "bidirectional"))
    )
    (net (code "307") (name "unconnected-(U400-RB15-Pad44)") (class "Default")
      (node (ref "U400") (pin "44") (pinfunction "RB15_44") (pintype "bidirectional"))
    )
    (net (code "308") (name "unconnected-(U400-RC13-Pad72)") (class "Default")
      (node (ref "U400") (pin "72") (pinfunction "RC13_72") (pintype "bidirectional"))
    )
    (net (code "309") (name "unconnected-(U400-RD3-Pad78)") (class "Default")
      (node (ref "U400") (pin "78") (pinfunction "RD3_78") (pintype "bidirectional"))
    )
    (net (code "310") (name "unconnected-(U400-RD14-Pad47)") (class "Default")
      (node (ref "U400") (pin "47") (pinfunction "RD14_47") (pintype "bidirectional"))
    )
    (net (code "311") (name "unconnected-(U400-RD15-Pad48)") (class "Default")
      (node (ref "U400") (pin "48") (pinfunction "RD15_48") (pintype "bidirectional"))
    )
    (net (code "312") (name "unconnected-(U400-RE0-Pad91)") (class "Default")
      (node (ref "U400") (pin "91") (pinfunction "RE0_91") (pintype "bidirectional"))
    )
    (net (code "313") (name "unconnected-(U400-RF1-Pad86)") (class "Default")
      (node (ref "U400") (pin "86") (pinfunction "RF1_86") (pintype "bidirectional"))
    )
    (net (code "314") (name "unconnected-(U400-RF2-Pad57)") (class "Default")
      (node (ref "U400") (pin "57") (pinfunction "RF2_57") (pintype "bidirectional"))
    )
    (net (code "315") (name "unconnected-(U400-RF3-Pad56)") (class "Default")
      (node (ref "U400") (pin "56") (pinfunction "RF3_56") (pintype "bidirectional"))
    )
    (net (code "316") (name "unconnected-(U400-RF12-Pad40)") (class "Default")
      (node (ref "U400") (pin "40") (pinfunction "RF12_40") (pintype "bidirectional"))
    )
    (net (code "317") (name "unconnected-(U400-RF13-Pad39)") (class "Default")
      (node (ref "U400") (pin "39") (pinfunction "RF13_39") (pintype "bidirectional"))
    )
    (net (code "318") (name "unconnected-(U400-RG0-Pad88)") (class "Default")
      (node (ref "U400") (pin "88") (pinfunction "RG0_88") (pintype "bidirectional"))
    )
    (net (code "319") (name "unconnected-(U400-RG1-Pad87)") (class "Default")
      (node (ref "U400") (pin "87") (pinfunction "RG1_87") (pintype "bidirectional"))
    )
    (net (code "320") (name "unconnected-(U400-VBUS-Pad51)") (class "Default")
      (node (ref "U400") (pin "51") (pinfunction "VBUS_51") (pintype "bidirectional"))
    )
    (net (code "321") (name "unconnected-(U401-CBUS0-Pad15)") (class "Default")
      (node (ref "U401") (pin "15") (pinfunction "CBUS0_15") (pintype "bidirectional"))
    )
    (net (code "322") (name "unconnected-(U401-CBUS2-Pad7)") (class "Default")
      (node (ref "U401") (pin "7") (pinfunction "CBUS2_7") (pintype "bidirectional"))
    )
    (net (code "323") (name "unconnected-(U401-CBUS3-Pad16)") (class "Default")
      (node (ref "U401") (pin "16") (pinfunction "CBUS3_16") (pintype "bidirectional"))
    )
    (net (code "324") (name "unconnected-(U401-~{RESET}-Pad11)") (class "Default")
      (node (ref "U401") (pin "11") (pinfunction "~{RESET}_11") (pintype "input"))
    )
    (net (code "325") (name "unconnected-(U401-~{RTS}-Pad2)") (class "Default")
      (node (ref "U401") (pin "2") (pinfunction "~{RTS}_2") (pintype "output"))
    )
  )
)
